# pcie-host.net
KiCad netlist of a schematic drawn in EAGLE
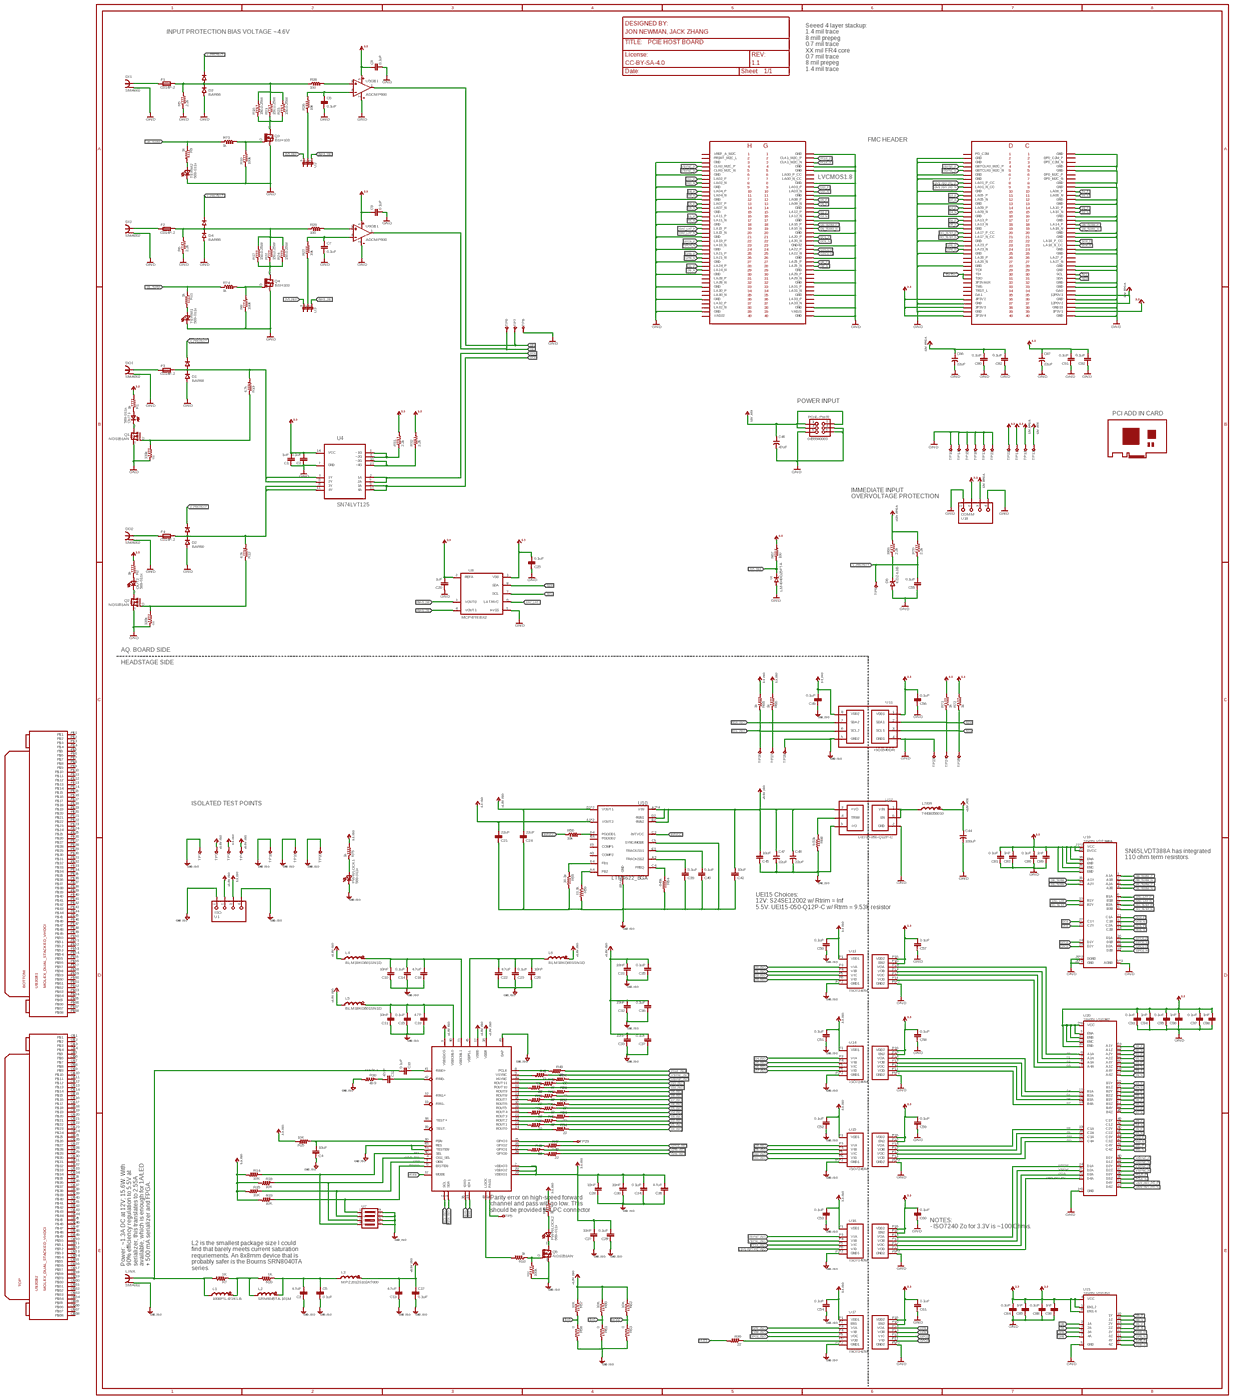
[diagram p0: schematic, sheet 1, overview]
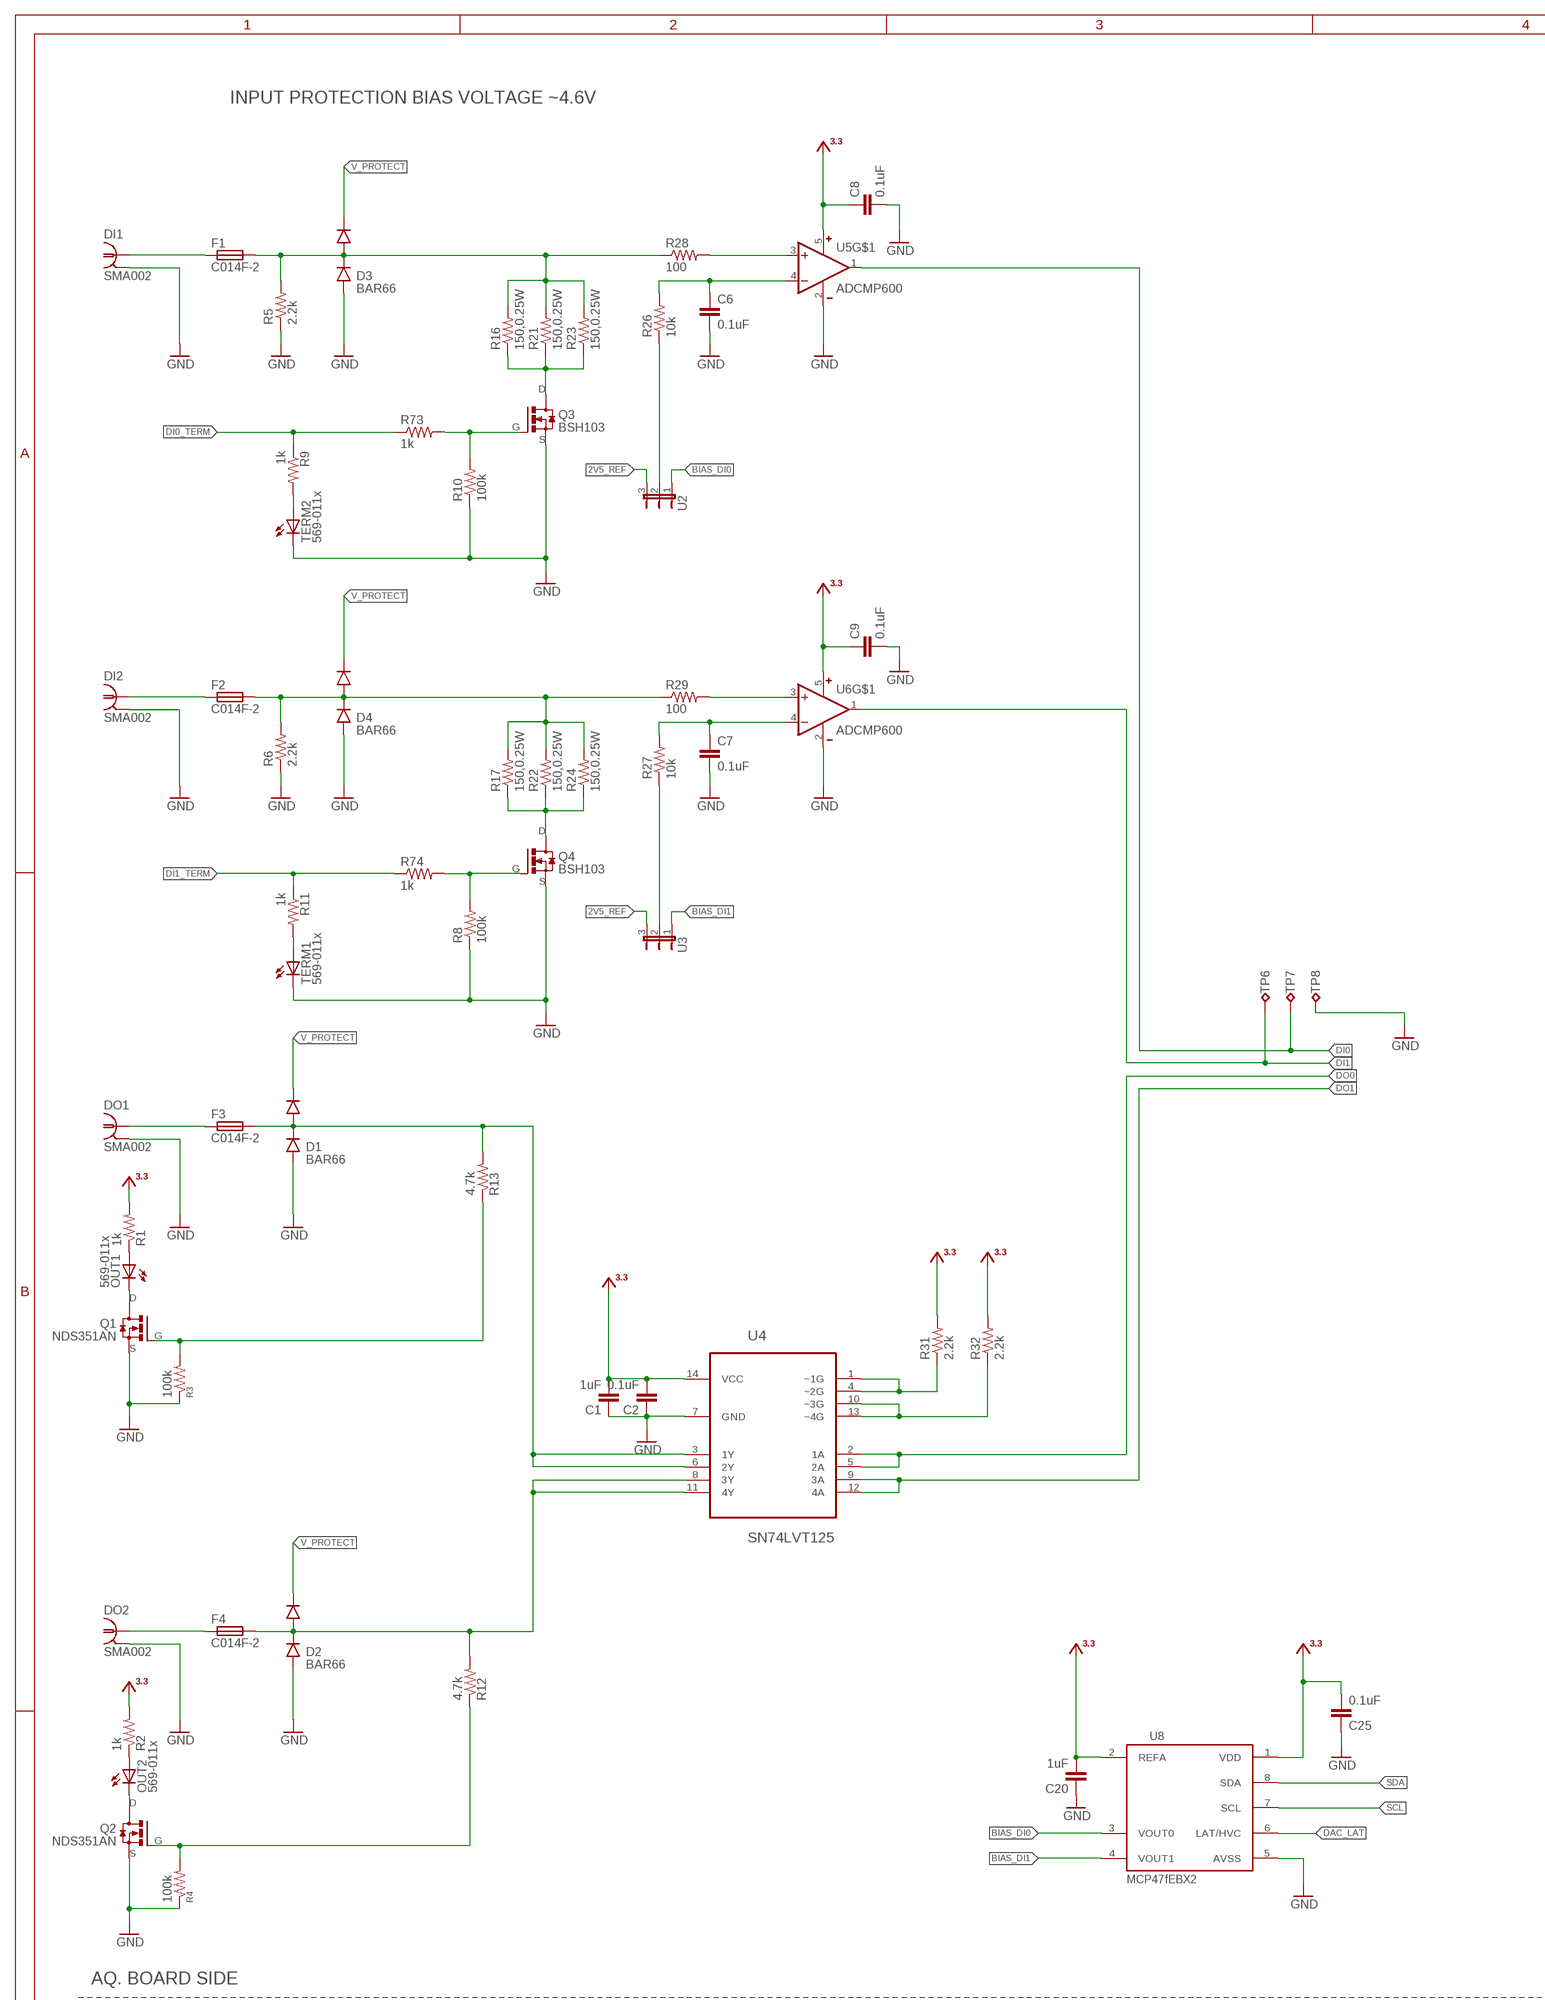
[diagram p1: schematic, sheet 1, part 1 of 4]
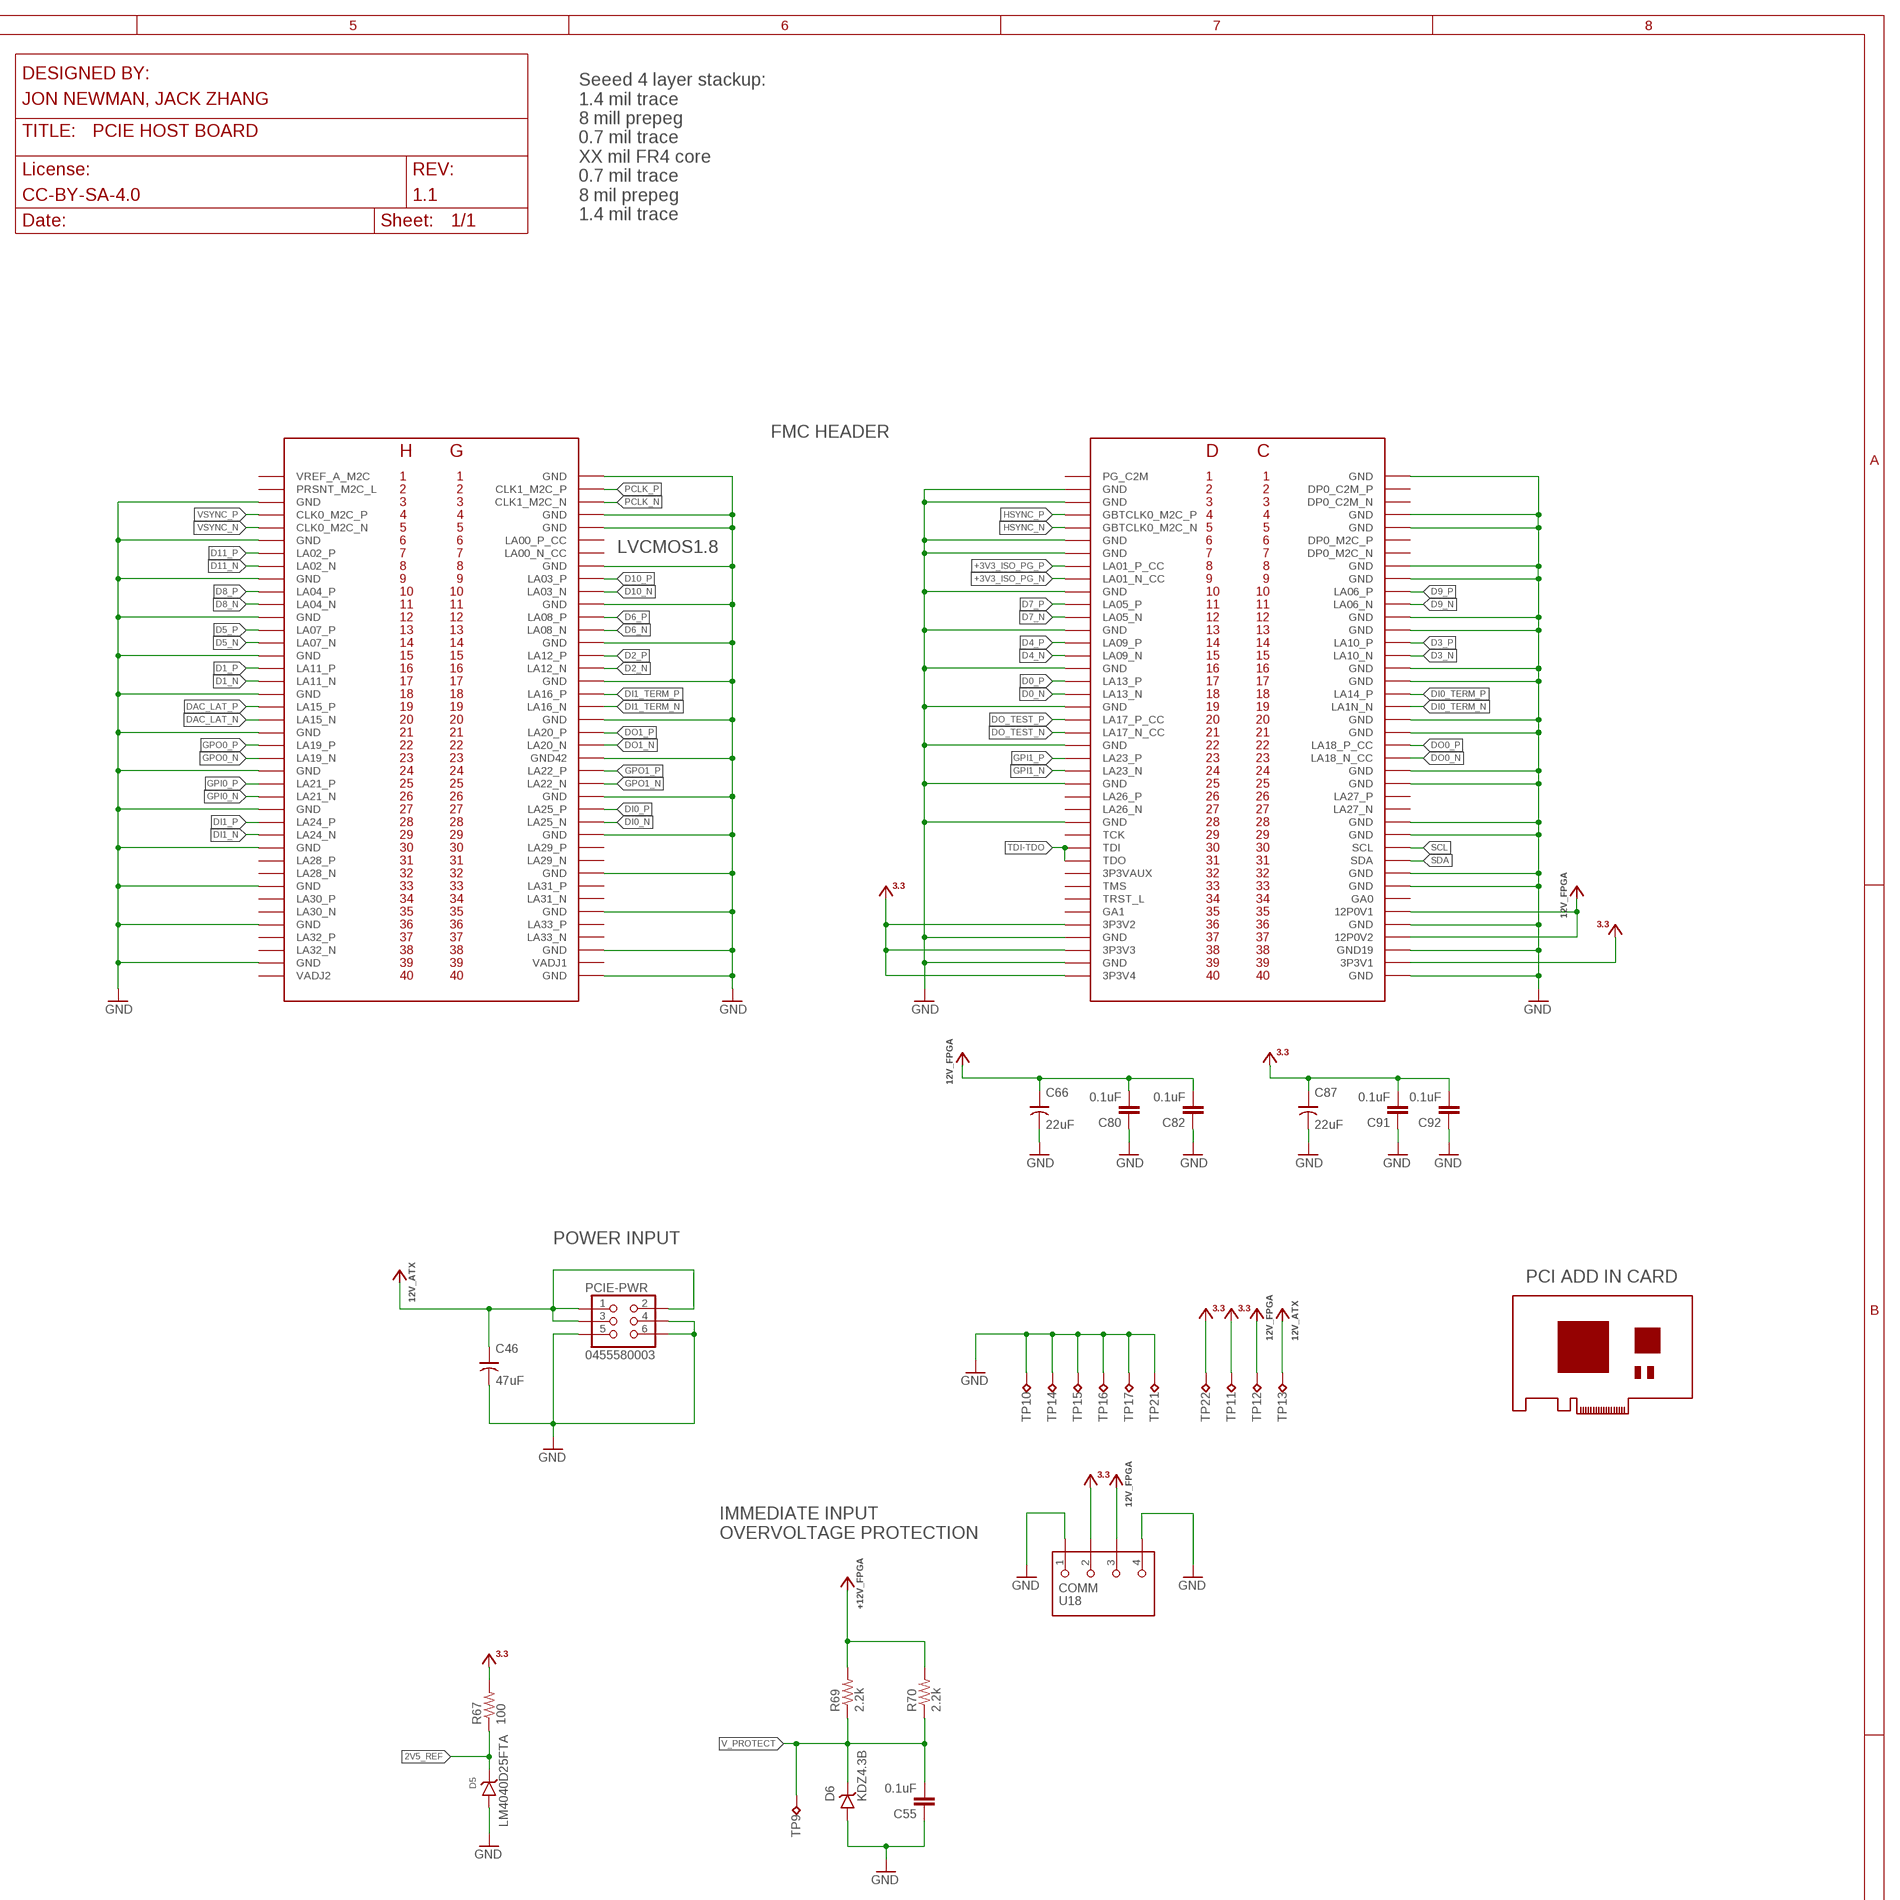
[diagram p2: schematic, sheet 1, part 2 of 4]
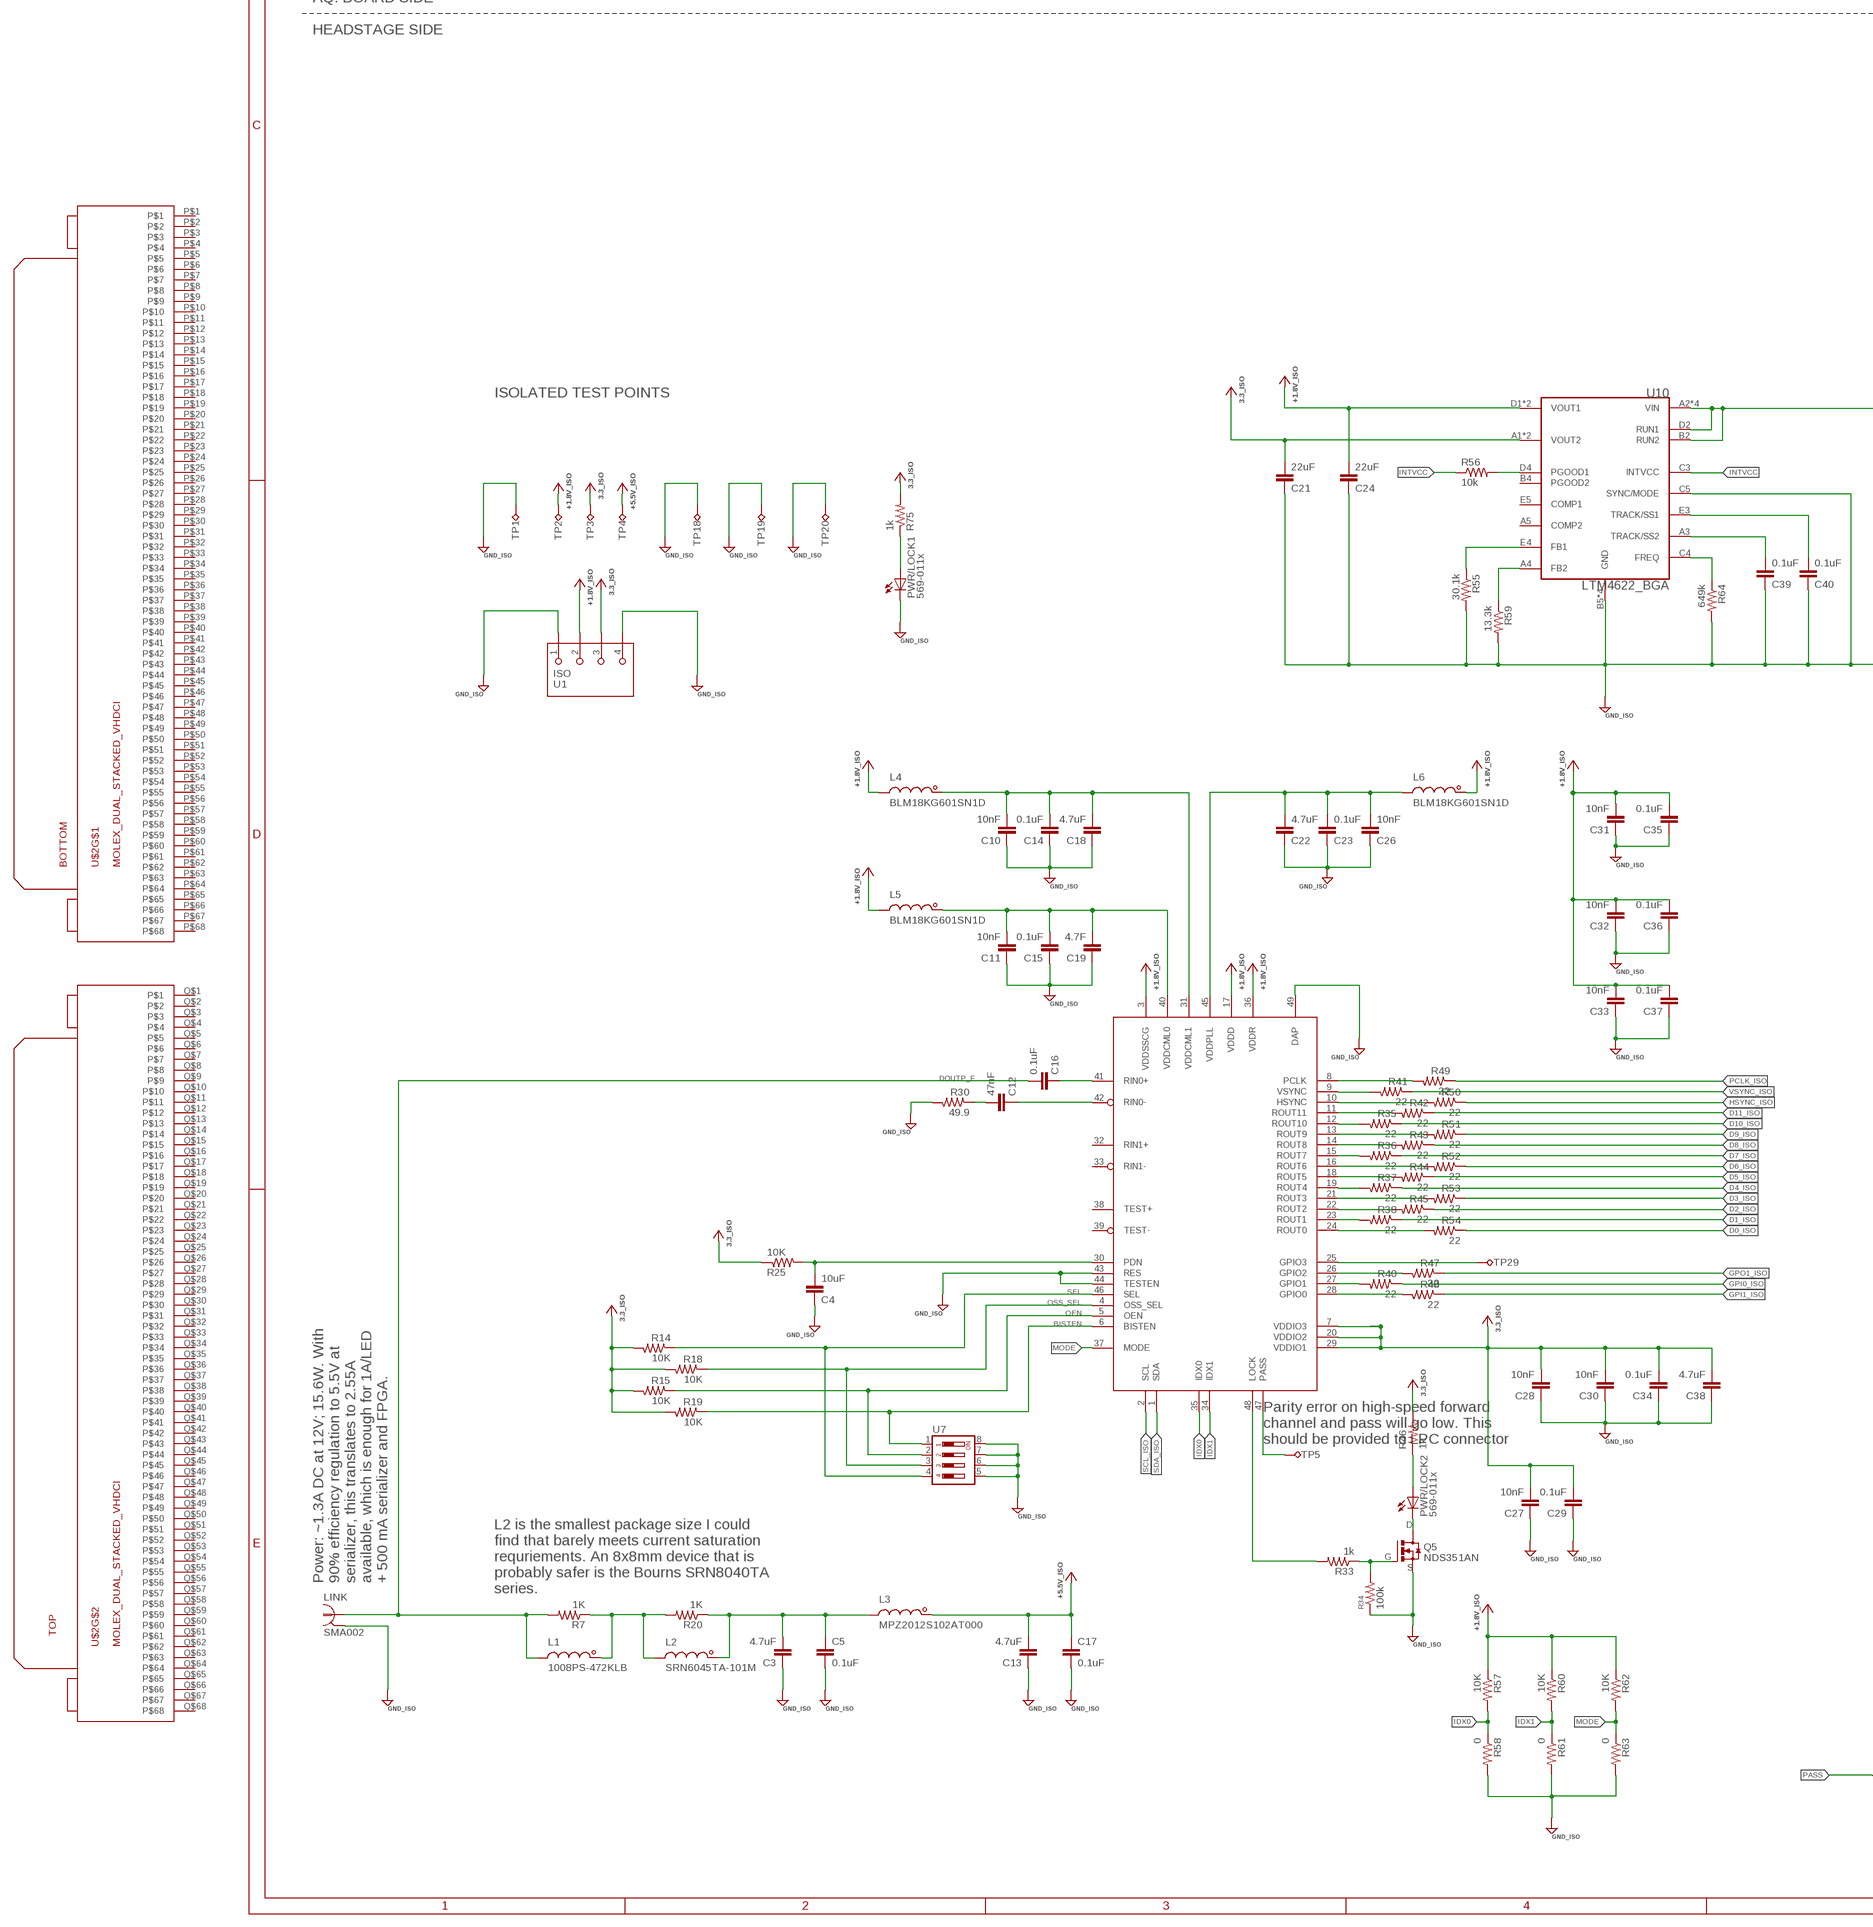
[diagram p3: schematic, sheet 1, part 3 of 4]
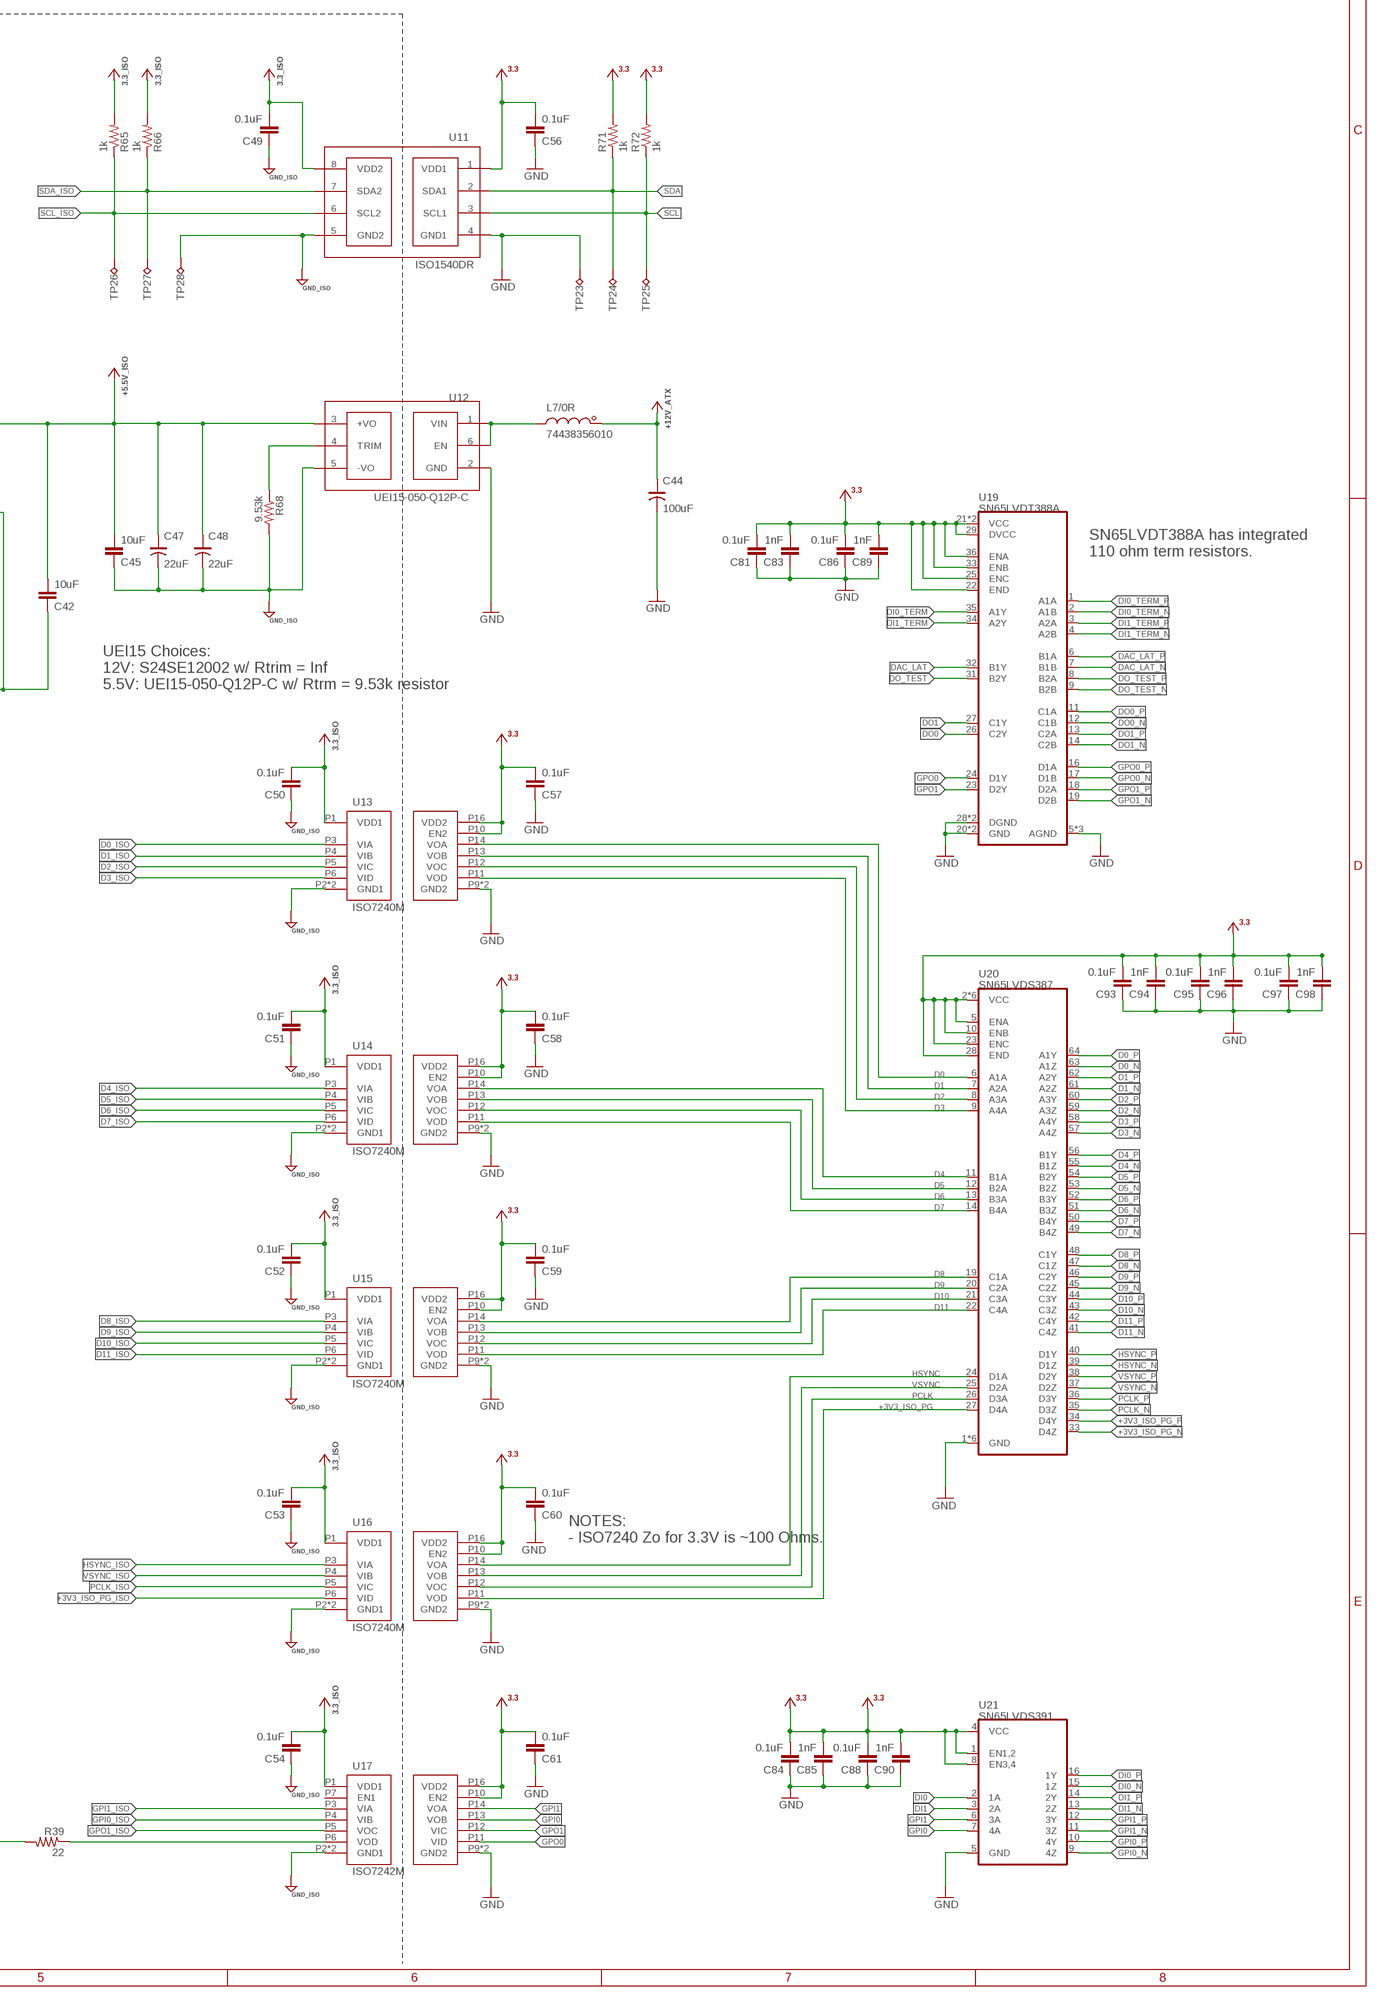
[diagram p4: schematic, sheet 1, part 4 of 4]

(export (version "E")
  (design (tool "Eeschema 10.0.6"))
  (components
    (comp (ref "C1")
      (value "1uF")
      (footprint "eagle-import:0603")
      (libsource (lib "eagle-import") (part "C_0603"))
    )
    (comp (ref "C2")
      (value "0.1uF")
      (footprint "eagle-import:0603")
      (libsource (lib "eagle-import") (part "C_0603"))
    )
    (comp (ref "C3")
      (value "4.7uF")
      (footprint "eagle-import:0805")
      (fields (field (name "PARTNO") "C2012X5R1Cxxxxxxx"))
      (libsource (lib "eagle-import") (part "jonnew_C_0805"))
    )
    (comp (ref "C4")
      (value "10uF")
      (footprint "eagle-import:0603")
      (libsource (lib "eagle-import") (part "jonnew_C_0603"))
    )
    (comp (ref "C5")
      (value "0.1uF")
      (footprint "eagle-import:0603")
      (libsource (lib "eagle-import") (part "jonnew_C_0603"))
    )
    (comp (ref "C6")
      (value "0.1uF")
      (footprint "eagle-import:0603")
      (libsource (lib "eagle-import") (part "jonnew_C_0603"))
    )
    (comp (ref "C7")
      (value "0.1uF")
      (footprint "eagle-import:0603")
      (libsource (lib "eagle-import") (part "jonnew_C_0603"))
    )
    (comp (ref "C8")
      (value "0.1uF")
      (footprint "eagle-import:0603")
      (libsource (lib "eagle-import") (part "jonnew_C_0603"))
    )
    (comp (ref "C9")
      (value "0.1uF")
      (footprint "eagle-import:0603")
      (libsource (lib "eagle-import") (part "jonnew_C_0603"))
    )
    (comp (ref "C10")
      (value "10nF")
      (footprint "eagle-import:0402")
      (libsource (lib "eagle-import") (part "jonnew_C_0402"))
    )
    (comp (ref "C11")
      (value "10nF")
      (footprint "eagle-import:0402")
      (libsource (lib "eagle-import") (part "jonnew_C_0402"))
    )
    (comp (ref "C12")
      (value "47nF")
      (footprint "eagle-import:0402")
      (libsource (lib "eagle-import") (part "jonnew_C_0402"))
    )
    (comp (ref "C13")
      (value "4.7uF")
      (footprint "eagle-import:0805")
      (fields (field (name "PARTNO") "C2012X5R1Cxxxxxxx"))
      (libsource (lib "eagle-import") (part "jonnew_C_0805"))
    )
    (comp (ref "C14")
      (value "0.1uF")
      (footprint "eagle-import:0402")
      (libsource (lib "eagle-import") (part "jonnew_C_0402"))
    )
    (comp (ref "C15")
      (value "0.1uF")
      (footprint "eagle-import:0402")
      (libsource (lib "eagle-import") (part "jonnew_C_0402"))
    )
    (comp (ref "C16")
      (value "0.1uF")
      (footprint "eagle-import:0402")
      (libsource (lib "eagle-import") (part "jonnew_C_0402"))
    )
    (comp (ref "C17")
      (value "0.1uF")
      (footprint "eagle-import:0603")
      (libsource (lib "eagle-import") (part "jonnew_C_0603"))
    )
    (comp (ref "C18")
      (value "4.7uF")
      (footprint "eagle-import:1206")
      (libsource (lib "eagle-import") (part "jonnew_C_1206"))
    )
    (comp (ref "C19")
      (value "4.7F")
      (footprint "eagle-import:1206")
      (libsource (lib "eagle-import") (part "jonnew_C_1206"))
    )
    (comp (ref "C20")
      (value "1uF")
      (footprint "eagle-import:0805")
      (fields (field (name "PARTNO") "C2012X5R1Cxxxxxxx"))
      (libsource (lib "eagle-import") (part "jonnew_C_0805"))
    )
    (comp (ref "C21")
      (value "22uF")
      (footprint "eagle-import:1206")
      (libsource (lib "eagle-import") (part "jonnew_C_1206"))
    )
    (comp (ref "C22")
      (value "4.7uF")
      (footprint "eagle-import:1206")
      (libsource (lib "eagle-import") (part "jonnew_C_1206"))
    )
    (comp (ref "C23")
      (value "0.1uF")
      (footprint "eagle-import:0402")
      (libsource (lib "eagle-import") (part "jonnew_C_0402"))
    )
    (comp (ref "C24")
      (value "22uF")
      (footprint "eagle-import:1206")
      (libsource (lib "eagle-import") (part "jonnew_C_1206"))
    )
    (comp (ref "C25")
      (value "0.1uF")
      (footprint "eagle-import:0603")
      (libsource (lib "eagle-import") (part "C_0603"))
    )
    (comp (ref "C26")
      (value "10nF")
      (footprint "eagle-import:0402")
      (libsource (lib "eagle-import") (part "jonnew_C_0402"))
    )
    (comp (ref "C27")
      (value "10nF")
      (footprint "eagle-import:0402")
      (libsource (lib "eagle-import") (part "jonnew_C_0402"))
    )
    (comp (ref "C28")
      (value "10nF")
      (footprint "eagle-import:0402")
      (libsource (lib "eagle-import") (part "jonnew_C_0402"))
    )
    (comp (ref "C29")
      (value "0.1uF")
      (footprint "eagle-import:0402")
      (libsource (lib "eagle-import") (part "jonnew_C_0402"))
    )
    (comp (ref "C30")
      (value "10nF")
      (footprint "eagle-import:0402")
      (libsource (lib "eagle-import") (part "jonnew_C_0402"))
    )
    (comp (ref "C31")
      (value "10nF")
      (footprint "eagle-import:0402")
      (libsource (lib "eagle-import") (part "jonnew_C_0402"))
    )
    (comp (ref "C32")
      (value "10nF")
      (footprint "eagle-import:0402")
      (libsource (lib "eagle-import") (part "jonnew_C_0402"))
    )
    (comp (ref "C33")
      (value "10nF")
      (footprint "eagle-import:0402")
      (libsource (lib "eagle-import") (part "jonnew_C_0402"))
    )
    (comp (ref "C34")
      (value "0.1uF")
      (footprint "eagle-import:0402")
      (libsource (lib "eagle-import") (part "jonnew_C_0402"))
    )
    (comp (ref "C35")
      (value "0.1uF")
      (footprint "eagle-import:0402")
      (libsource (lib "eagle-import") (part "jonnew_C_0402"))
    )
    (comp (ref "C36")
      (value "0.1uF")
      (footprint "eagle-import:0402")
      (libsource (lib "eagle-import") (part "jonnew_C_0402"))
    )
    (comp (ref "C37")
      (value "0.1uF")
      (footprint "eagle-import:0402")
      (libsource (lib "eagle-import") (part "jonnew_C_0402"))
    )
    (comp (ref "C38")
      (value "4.7uF")
      (footprint "eagle-import:1206")
      (libsource (lib "eagle-import") (part "jonnew_C_1206"))
    )
    (comp (ref "C39")
      (value "0.1uF")
      (footprint "eagle-import:0603")
      (libsource (lib "eagle-import") (part "jonnew_C_0603"))
    )
    (comp (ref "C40")
      (value "0.1uF")
      (footprint "eagle-import:0603")
      (libsource (lib "eagle-import") (part "jonnew_C_0603"))
    )
    (comp (ref "C42")
      (value "10uF")
      (footprint "eagle-import:1206")
      (libsource (lib "eagle-import") (part "jonnew_C_1206"))
    )
    (comp (ref "C44")
      (value "100uF")
      (footprint "eagle-import:153CLV-0807")
      (libsource (lib "eagle-import") (part "C-POL_0807"))
    )
    (comp (ref "C45")
      (value "10uF")
      (footprint "eagle-import:1206")
      (libsource (lib "eagle-import") (part "jonnew_C_1206"))
    )
    (comp (ref "C46")
      (value "47uF")
      (footprint "eagle-import:153CLV-0807")
      (libsource (lib "eagle-import") (part "C-POL_0807"))
    )
    (comp (ref "C47")
      (value "22uF")
      (footprint "eagle-import:1210-POL")
      (libsource (lib "eagle-import") (part "C-POL_1210"))
    )
    (comp (ref "C48")
      (value "22uF")
      (footprint "eagle-import:1210-POL")
      (libsource (lib "eagle-import") (part "C-POL_1210"))
    )
    (comp (ref "C49")
      (value "0.1uF")
      (footprint "eagle-import:0603")
      (libsource (lib "eagle-import") (part "jonnew_C_0603"))
    )
    (comp (ref "C50")
      (value "0.1uF")
      (footprint "eagle-import:0603")
      (libsource (lib "eagle-import") (part "jonnew_C_0603"))
    )
    (comp (ref "C51")
      (value "0.1uF")
      (footprint "eagle-import:0603")
      (libsource (lib "eagle-import") (part "jonnew_C_0603"))
    )
    (comp (ref "C52")
      (value "0.1uF")
      (footprint "eagle-import:0603")
      (libsource (lib "eagle-import") (part "jonnew_C_0603"))
    )
    (comp (ref "C53")
      (value "0.1uF")
      (footprint "eagle-import:0603")
      (libsource (lib "eagle-import") (part "jonnew_C_0603"))
    )
    (comp (ref "C54")
      (value "0.1uF")
      (footprint "eagle-import:0603")
      (libsource (lib "eagle-import") (part "jonnew_C_0603"))
    )
    (comp (ref "C55")
      (value "0.1uF")
      (footprint "eagle-import:0603")
      (libsource (lib "eagle-import") (part "jonnew_C_0603"))
    )
    (comp (ref "C56")
      (value "0.1uF")
      (footprint "eagle-import:0603")
      (libsource (lib "eagle-import") (part "jonnew_C_0603"))
    )
    (comp (ref "C57")
      (value "0.1uF")
      (footprint "eagle-import:0603")
      (libsource (lib "eagle-import") (part "jonnew_C_0603"))
    )
    (comp (ref "C58")
      (value "0.1uF")
      (footprint "eagle-import:0603")
      (libsource (lib "eagle-import") (part "jonnew_C_0603"))
    )
    (comp (ref "C59")
      (value "0.1uF")
      (footprint "eagle-import:0603")
      (libsource (lib "eagle-import") (part "jonnew_C_0603"))
    )
    (comp (ref "C60")
      (value "0.1uF")
      (footprint "eagle-import:0603")
      (libsource (lib "eagle-import") (part "jonnew_C_0603"))
    )
    (comp (ref "C61")
      (value "0.1uF")
      (footprint "eagle-import:0603")
      (libsource (lib "eagle-import") (part "jonnew_C_0603"))
    )
    (comp (ref "C66")
      (value "22uF")
      (footprint "eagle-import:1210-POL")
      (libsource (lib "eagle-import") (part "C-POL_1210"))
    )
    (comp (ref "C80")
      (value "0.1uF")
      (footprint "eagle-import:0603")
      (libsource (lib "eagle-import") (part "jonnew_C_0603"))
    )
    (comp (ref "C81")
      (value "0.1uF")
      (footprint "eagle-import:0603")
      (libsource (lib "eagle-import") (part "jonnew_C_0603"))
    )
    (comp (ref "C82")
      (value "0.1uF")
      (footprint "eagle-import:0603")
      (libsource (lib "eagle-import") (part "jonnew_C_0603"))
    )
    (comp (ref "C83")
      (value "1nF")
      (footprint "eagle-import:0402")
      (libsource (lib "eagle-import") (part "jonnew_C_0402"))
    )
    (comp (ref "C84")
      (value "0.1uF")
      (footprint "eagle-import:0603")
      (libsource (lib "eagle-import") (part "jonnew_C_0603"))
    )
    (comp (ref "C85")
      (value "1nF")
      (footprint "eagle-import:0402")
      (libsource (lib "eagle-import") (part "jonnew_C_0402"))
    )
    (comp (ref "C86")
      (value "0.1uF")
      (footprint "eagle-import:0603")
      (libsource (lib "eagle-import") (part "jonnew_C_0603"))
    )
    (comp (ref "C87")
      (value "22uF")
      (footprint "eagle-import:1210-POL")
      (libsource (lib "eagle-import") (part "C-POL_1210"))
    )
    (comp (ref "C88")
      (value "0.1uF")
      (footprint "eagle-import:0603")
      (libsource (lib "eagle-import") (part "jonnew_C_0603"))
    )
    (comp (ref "C89")
      (value "1nF")
      (footprint "eagle-import:0402")
      (libsource (lib "eagle-import") (part "jonnew_C_0402"))
    )
    (comp (ref "C90")
      (value "1nF")
      (footprint "eagle-import:0402")
      (libsource (lib "eagle-import") (part "jonnew_C_0402"))
    )
    (comp (ref "C91")
      (value "0.1uF")
      (footprint "eagle-import:0603")
      (libsource (lib "eagle-import") (part "jonnew_C_0603"))
    )
    (comp (ref "C92")
      (value "0.1uF")
      (footprint "eagle-import:0603")
      (libsource (lib "eagle-import") (part "jonnew_C_0603"))
    )
    (comp (ref "C93")
      (value "0.1uF")
      (footprint "eagle-import:0603")
      (libsource (lib "eagle-import") (part "jonnew_C_0603"))
    )
    (comp (ref "C94")
      (value "1nF")
      (footprint "eagle-import:0402")
      (libsource (lib "eagle-import") (part "jonnew_C_0402"))
    )
    (comp (ref "C95")
      (value "0.1uF")
      (footprint "eagle-import:0603")
      (libsource (lib "eagle-import") (part "jonnew_C_0603"))
    )
    (comp (ref "C96")
      (value "1nF")
      (footprint "eagle-import:0402")
      (libsource (lib "eagle-import") (part "jonnew_C_0402"))
    )
    (comp (ref "C97")
      (value "0.1uF")
      (footprint "eagle-import:0603")
      (libsource (lib "eagle-import") (part "jonnew_C_0603"))
    )
    (comp (ref "C98")
      (value "1nF")
      (footprint "eagle-import:0402")
      (libsource (lib "eagle-import") (part "jonnew_C_0402"))
    )
    (comp (ref "D1")
      (value "BAR66")
      (footprint "eagle-import:SOT23")
      (libsource (lib "eagle-import") (part "DIODE2_SOT23"))
    )
    (comp (ref "D2")
      (value "BAR66")
      (footprint "eagle-import:SOT23")
      (libsource (lib "eagle-import") (part "DIODE2_SOT23"))
    )
    (comp (ref "D3")
      (value "BAR66")
      (footprint "eagle-import:SOT23")
      (libsource (lib "eagle-import") (part "DIODE2_SOT23"))
    )
    (comp (ref "D4")
      (value "BAR66")
      (footprint "eagle-import:SOT23")
      (libsource (lib "eagle-import") (part "DIODE2_SOT23"))
    )
    (comp (ref "D5")
      (value "LM4040D25FTA")
      (footprint "eagle-import:SOT23")
      (libsource (lib "eagle-import") (part "Z-DIODE_SOT23"))
    )
    (comp (ref "D6")
      (value "KDZ4.3B")
      (footprint "eagle-import:SOD123")
      (libsource (lib "eagle-import") (part "Z-DIODE_SOD123"))
    )
    (comp (ref "DI1")
      (value "SMA002")
      (footprint "eagle-import:SMA_JACK_CONREVSMA002-G")
      (libsource (lib "eagle-import") (part "COAX_CONREVSMA002-G"))
    )
    (comp (ref "DI2")
      (value "SMA002")
      (footprint "eagle-import:SMA_JACK_CONREVSMA002-G")
      (libsource (lib "eagle-import") (part "COAX_CONREVSMA002-G"))
    )
    (comp (ref "DO1")
      (value "SMA002")
      (footprint "eagle-import:SMA_JACK_CONREVSMA002-G")
      (libsource (lib "eagle-import") (part "COAX_CONREVSMA002-G"))
    )
    (comp (ref "DO2")
      (value "SMA002")
      (footprint "eagle-import:SMA_JACK_CONREVSMA002-G")
      (libsource (lib "eagle-import") (part "COAX_CONREVSMA002-G"))
    )
    (comp (ref "F1")
      (value "C014F-2")
      (footprint "eagle-import:1812")
      (libsource (lib "eagle-import") (part "FUSE_1812"))
    )
    (comp (ref "F2")
      (value "C014F-2")
      (footprint "eagle-import:1812")
      (libsource (lib "eagle-import") (part "FUSE_1812"))
    )
    (comp (ref "F3")
      (value "C014F-2")
      (footprint "eagle-import:1812")
      (libsource (lib "eagle-import") (part "FUSE_1812"))
    )
    (comp (ref "F4")
      (value "C014F-2")
      (footprint "eagle-import:1812")
      (libsource (lib "eagle-import") (part "FUSE_1812"))
    )
    (comp (ref "FMC_LPC")
      (value "FMC_LPC_160_PIN")
      (footprint "eagle-import:FMC_LPC_MALE_WITH_SP601_BSILK")
      (libsource (lib "eagle-import") (part "FMC_LPC_160_PIN"))
    )
    (comp (ref "L1")
      (value "1008PS-472KLB")
      (footprint "eagle-import:1008PS")
      (libsource (lib "eagle-import") (part "L_1008PS"))
    )
    (comp (ref "L2")
      (value "SRN6045TA-101M")
      (footprint "eagle-import:SRN6045TA")
      (libsource (lib "eagle-import") (part "L_SRN6045TA"))
    )
    (comp (ref "L3")
      (value "MPZ2012S102AT000")
      (footprint "eagle-import:0805")
      (libsource (lib "eagle-import") (part "L_0805"))
    )
    (comp (ref "L4")
      (value "BLM18KG601SN1D")
      (footprint "eagle-import:0603")
      (libsource (lib "eagle-import") (part "L_0603"))
    )
    (comp (ref "L5")
      (value "BLM18KG601SN1D")
      (footprint "eagle-import:0603")
      (libsource (lib "eagle-import") (part "L_0603"))
    )
    (comp (ref "L6")
      (value "BLM18KG601SN1D")
      (footprint "eagle-import:0603")
      (libsource (lib "eagle-import") (part "L_0603"))
    )
    (comp (ref "L7/0R")
      (value "74438356010")
      (footprint "eagle-import:4020")
      (libsource (lib "eagle-import") (part "L_4020"))
    )
    (comp (ref "LINK")
      (value "SMA002")
      (footprint "eagle-import:SMA_JACK_CONREVSMA002-G")
      (libsource (lib "eagle-import") (part "COAX_CONREVSMA002-G"))
    )
    (comp (ref "OUT")
      (value "569-011x")
      (footprint "eagle-import:569-011X-X00_LED_ARRAY")
      (libsource (lib "eagle-import") (part "LED_2X_VERTICAL"))
    )
    (comp (ref "PCIE-PWR")
      (value "0455580003")
      (footprint "eagle-import:PCIE-POWER-6PIN")
      (libsource (lib "eagle-import") (part "PINHD-2X3_PCIE-PWR"))
    )
    (comp (ref "PWR/LOCK")
      (value "569-011x")
      (footprint "eagle-import:569-011X-X00_LED_ARRAY")
      (libsource (lib "eagle-import") (part "LED_2X_VERTICAL"))
    )
    (comp (ref "Q1")
      (value "NDS351AN")
      (footprint "eagle-import:SOT23-GSD")
      (libsource (lib "eagle-import") (part "N-MOSFET_SOT23-GSD"))
    )
    (comp (ref "Q2")
      (value "NDS351AN")
      (footprint "eagle-import:SOT23-GSD")
      (libsource (lib "eagle-import") (part "N-MOSFET_SOT23-GSD"))
    )
    (comp (ref "Q3")
      (value "BSH103")
      (footprint "eagle-import:SOT23-GSD")
      (libsource (lib "eagle-import") (part "N-MOSFET_SOT23-GSD"))
    )
    (comp (ref "Q4")
      (value "BSH103")
      (footprint "eagle-import:SOT23-GSD")
      (libsource (lib "eagle-import") (part "N-MOSFET_SOT23-GSD"))
    )
    (comp (ref "Q5")
      (value "NDS351AN")
      (footprint "eagle-import:SOT23-GSD")
      (libsource (lib "eagle-import") (part "N-MOSFET_SOT23-GSD"))
    )
    (comp (ref "R1")
      (value "1k")
      (footprint "eagle-import:0603")
      (fields (field (name "MPN") "ERJ-3EKFxxxxV"))
      (libsource (lib "eagle-import") (part "cyclops_R_0603"))
    )
    (comp (ref "R2")
      (value "1k")
      (footprint "eagle-import:0603")
      (fields (field (name "MPN") "ERJ-3EKFxxxxV"))
      (libsource (lib "eagle-import") (part "cyclops_R_0603"))
    )
    (comp (ref "R3")
      (value "100k")
      (footprint "eagle-import:0603")
      (fields (field (name "MPN") "ERJ-3EKFxxxxV"))
      (libsource (lib "eagle-import") (part "cyclops_R_0603"))
    )
    (comp (ref "R4")
      (value "100k")
      (footprint "eagle-import:0603")
      (fields (field (name "MPN") "ERJ-3EKFxxxxV"))
      (libsource (lib "eagle-import") (part "cyclops_R_0603"))
    )
    (comp (ref "R5")
      (value "2.2k")
      (footprint "eagle-import:0603")
      (fields (field (name "MPN") "ERJ-3EKFxxxxV"))
      (libsource (lib "eagle-import") (part "jonnew_R_0603"))
    )
    (comp (ref "R6")
      (value "2.2k")
      (footprint "eagle-import:0603")
      (fields (field (name "MPN") "ERJ-3EKFxxxxV"))
      (libsource (lib "eagle-import") (part "jonnew_R_0603"))
    )
    (comp (ref "R7")
      (value "1K")
      (footprint "eagle-import:0603")
      (fields (field (name "MPN") "ERJ-3EKFxxxxV"))
      (libsource (lib "eagle-import") (part "jonnew_R_0603"))
    )
    (comp (ref "R8")
      (value "100k")
      (footprint "eagle-import:0603")
      (fields (field (name "MPN") "ERJ-3EKFxxxxV"))
      (libsource (lib "eagle-import") (part "jonnew_R_0603"))
    )
    (comp (ref "R9")
      (value "1k")
      (footprint "eagle-import:0603")
      (fields (field (name "MPN") "ERJ-3EKFxxxxV"))
      (libsource (lib "eagle-import") (part "jonnew_R_0603"))
    )
    (comp (ref "R10")
      (value "100k")
      (footprint "eagle-import:0603")
      (fields (field (name "MPN") "ERJ-3EKFxxxxV"))
      (libsource (lib "eagle-import") (part "jonnew_R_0603"))
    )
    (comp (ref "R11")
      (value "1k")
      (footprint "eagle-import:0603")
      (libsource (lib "eagle-import") (part "R_0603"))
    )
    (comp (ref "R12")
      (value "4.7k")
      (footprint "eagle-import:0603")
      (fields (field (name "MPN") "ERJ-3EKFxxxxV"))
      (libsource (lib "eagle-import") (part "cyclops_R_0603"))
    )
    (comp (ref "R13")
      (value "4.7k")
      (footprint "eagle-import:0603")
      (fields (field (name "MPN") "ERJ-3EKFxxxxV"))
      (libsource (lib "eagle-import") (part "cyclops_R_0603"))
    )
    (comp (ref "R14")
      (value "10K")
      (footprint "eagle-import:0402")
      (libsource (lib "eagle-import") (part "jonnew_R_0402"))
    )
    (comp (ref "R15")
      (value "10K")
      (footprint "eagle-import:0402")
      (libsource (lib "eagle-import") (part "jonnew_R_0402"))
    )
    (comp (ref "R16")
      (value "150,0.25W")
      (footprint "eagle-import:1206")
      (libsource (lib "eagle-import") (part "jonnew_R_1206"))
    )
    (comp (ref "R17")
      (value "150,0.25W")
      (footprint "eagle-import:1206")
      (libsource (lib "eagle-import") (part "jonnew_R_1206"))
    )
    (comp (ref "R18")
      (value "10K")
      (footprint "eagle-import:0402")
      (libsource (lib "eagle-import") (part "jonnew_R_0402"))
    )
    (comp (ref "R19")
      (value "10K")
      (footprint "eagle-import:0402")
      (libsource (lib "eagle-import") (part "jonnew_R_0402"))
    )
    (comp (ref "R20")
      (value "1K")
      (footprint "eagle-import:0603")
      (fields (field (name "MPN") "ERJ-3EKFxxxxV"))
      (libsource (lib "eagle-import") (part "jonnew_R_0603"))
    )
    (comp (ref "R21")
      (value "150,0.25W")
      (footprint "eagle-import:1206")
      (libsource (lib "eagle-import") (part "jonnew_R_1206"))
    )
    (comp (ref "R22")
      (value "150,0.25W")
      (footprint "eagle-import:1206")
      (libsource (lib "eagle-import") (part "jonnew_R_1206"))
    )
    (comp (ref "R23")
      (value "150,0.25W")
      (footprint "eagle-import:1206")
      (libsource (lib "eagle-import") (part "jonnew_R_1206"))
    )
    (comp (ref "R24")
      (value "150,0.25W")
      (footprint "eagle-import:1206")
      (libsource (lib "eagle-import") (part "jonnew_R_1206"))
    )
    (comp (ref "R25")
      (value "10K")
      (footprint "eagle-import:0402")
      (libsource (lib "eagle-import") (part "jonnew_R_0402"))
    )
    (comp (ref "R26")
      (value "10k")
      (footprint "eagle-import:0603")
      (fields (field (name "MPN") "ERJ-3EKFxxxxV"))
      (libsource (lib "eagle-import") (part "jonnew_R_0603"))
    )
    (comp (ref "R27")
      (value "10k")
      (footprint "eagle-import:0603")
      (fields (field (name "MPN") "ERJ-3EKFxxxxV"))
      (libsource (lib "eagle-import") (part "jonnew_R_0603"))
    )
    (comp (ref "R28")
      (value "100")
      (footprint "eagle-import:0603")
      (fields (field (name "MPN") "ERJ-3EKFxxxxV"))
      (libsource (lib "eagle-import") (part "jonnew_R_0603"))
    )
    (comp (ref "R29")
      (value "100")
      (footprint "eagle-import:0603")
      (fields (field (name "MPN") "ERJ-3EKFxxxxV"))
      (libsource (lib "eagle-import") (part "jonnew_R_0603"))
    )
    (comp (ref "R30")
      (value "49.9")
      (footprint "eagle-import:0402")
      (libsource (lib "eagle-import") (part "jonnew_R_0402"))
    )
    (comp (ref "R31")
      (value "2.2k")
      (footprint "eagle-import:0603")
      (fields (field (name "MPN") "ERJ-3EKFxxxxV"))
      (libsource (lib "eagle-import") (part "jonnew_R_0603"))
    )
    (comp (ref "R32")
      (value "2.2k")
      (footprint "eagle-import:0603")
      (fields (field (name "MPN") "ERJ-3EKFxxxxV"))
      (libsource (lib "eagle-import") (part "jonnew_R_0603"))
    )
    (comp (ref "R33")
      (value "1k")
      (footprint "eagle-import:0603")
      (fields (field (name "MPN") "ERJ-3EKFxxxxV"))
      (libsource (lib "eagle-import") (part "cyclops_R_0603"))
    )
    (comp (ref "R34")
      (value "100k")
      (footprint "eagle-import:0603")
      (fields (field (name "MPN") "ERJ-3EKFxxxxV"))
      (libsource (lib "eagle-import") (part "cyclops_R_0603"))
    )
    (comp (ref "R35")
      (value "22")
      (footprint "eagle-import:0402")
      (libsource (lib "eagle-import") (part "jonnew_R_0402"))
    )
    (comp (ref "R36")
      (value "22")
      (footprint "eagle-import:0402")
      (libsource (lib "eagle-import") (part "jonnew_R_0402"))
    )
    (comp (ref "R37")
      (value "22")
      (footprint "eagle-import:0402")
      (libsource (lib "eagle-import") (part "jonnew_R_0402"))
    )
    (comp (ref "R38")
      (value "22")
      (footprint "eagle-import:0402")
      (libsource (lib "eagle-import") (part "jonnew_R_0402"))
    )
    (comp (ref "R39")
      (value "22")
      (footprint "eagle-import:0402")
      (libsource (lib "eagle-import") (part "jonnew_R_0402"))
    )
    (comp (ref "R40")
      (value "22")
      (footprint "eagle-import:0402")
      (libsource (lib "eagle-import") (part "jonnew_R_0402"))
    )
    (comp (ref "R41")
      (value "22")
      (footprint "eagle-import:0402")
      (libsource (lib "eagle-import") (part "jonnew_R_0402"))
    )
    (comp (ref "R42")
      (value "22")
      (footprint "eagle-import:0402")
      (libsource (lib "eagle-import") (part "jonnew_R_0402"))
    )
    (comp (ref "R43")
      (value "22")
      (footprint "eagle-import:0402")
      (libsource (lib "eagle-import") (part "jonnew_R_0402"))
    )
    (comp (ref "R44")
      (value "22")
      (footprint "eagle-import:0402")
      (libsource (lib "eagle-import") (part "jonnew_R_0402"))
    )
    (comp (ref "R45")
      (value "22")
      (footprint "eagle-import:0402")
      (libsource (lib "eagle-import") (part "jonnew_R_0402"))
    )
    (comp (ref "R46")
      (value "1k")
      (footprint "eagle-import:0603")
      (fields (field (name "MPN") "ERJ-3EKFxxxxV"))
      (libsource (lib "eagle-import") (part "cyclops_R_0603"))
    )
    (comp (ref "R47")
      (value "22")
      (footprint "eagle-import:0402")
      (libsource (lib "eagle-import") (part "jonnew_R_0402"))
    )
    (comp (ref "R48")
      (value "22")
      (footprint "eagle-import:0402")
      (libsource (lib "eagle-import") (part "jonnew_R_0402"))
    )
    (comp (ref "R49")
      (value "22")
      (footprint "eagle-import:0402")
      (libsource (lib "eagle-import") (part "jonnew_R_0402"))
    )
    (comp (ref "R50")
      (value "22")
      (footprint "eagle-import:0402")
      (libsource (lib "eagle-import") (part "jonnew_R_0402"))
    )
    (comp (ref "R51")
      (value "22")
      (footprint "eagle-import:0402")
      (libsource (lib "eagle-import") (part "jonnew_R_0402"))
    )
    (comp (ref "R52")
      (value "22")
      (footprint "eagle-import:0402")
      (libsource (lib "eagle-import") (part "jonnew_R_0402"))
    )
    (comp (ref "R53")
      (value "22")
      (footprint "eagle-import:0402")
      (libsource (lib "eagle-import") (part "jonnew_R_0402"))
    )
    (comp (ref "R54")
      (value "22")
      (footprint "eagle-import:0402")
      (libsource (lib "eagle-import") (part "jonnew_R_0402"))
    )
    (comp (ref "R55")
      (value "30.1k")
      (footprint "eagle-import:0603")
      (fields (field (name "MPN") "ERJ-3EKFxxxxV"))
      (libsource (lib "eagle-import") (part "jonnew_R_0603"))
    )
    (comp (ref "R56")
      (value "10k")
      (footprint "eagle-import:0603")
      (fields (field (name "MPN") "ERJ-3EKFxxxxV"))
      (libsource (lib "eagle-import") (part "jonnew_R_0603"))
    )
    (comp (ref "R57")
      (value "10K")
      (footprint "eagle-import:0402")
      (libsource (lib "eagle-import") (part "jonnew_R_0402"))
    )
    (comp (ref "R58")
      (value "0")
      (footprint "eagle-import:0402")
      (libsource (lib "eagle-import") (part "jonnew_R_0402"))
    )
    (comp (ref "R59")
      (value "13.3k")
      (footprint "eagle-import:0603")
      (fields (field (name "MPN") "ERJ-3EKFxxxxV"))
      (libsource (lib "eagle-import") (part "jonnew_R_0603"))
    )
    (comp (ref "R60")
      (value "10K")
      (footprint "eagle-import:0402")
      (libsource (lib "eagle-import") (part "jonnew_R_0402"))
    )
    (comp (ref "R61")
      (value "0")
      (footprint "eagle-import:0402")
      (libsource (lib "eagle-import") (part "jonnew_R_0402"))
    )
    (comp (ref "R62")
      (value "10K")
      (footprint "eagle-import:0402")
      (libsource (lib "eagle-import") (part "jonnew_R_0402"))
    )
    (comp (ref "R63")
      (value "0")
      (footprint "eagle-import:0402")
      (libsource (lib "eagle-import") (part "jonnew_R_0402"))
    )
    (comp (ref "R64")
      (value "649k")
      (footprint "eagle-import:0603")
      (fields (field (name "MPN") "ERJ-3EKFxxxxV"))
      (libsource (lib "eagle-import") (part "jonnew_R_0603"))
    )
    (comp (ref "R65")
      (value "1k")
      (footprint "eagle-import:0603")
      (fields (field (name "MPN") "ERJ-3EKFxxxxV"))
      (libsource (lib "eagle-import") (part "jonnew_R_0603"))
    )
    (comp (ref "R66")
      (value "1k")
      (footprint "eagle-import:0603")
      (fields (field (name "MPN") "ERJ-3EKFxxxxV"))
      (libsource (lib "eagle-import") (part "jonnew_R_0603"))
    )
    (comp (ref "R67")
      (value "100")
      (footprint "eagle-import:0603")
      (fields (field (name "MPN") "ERJ-3EKFxxxxV"))
      (libsource (lib "eagle-import") (part "jonnew_R_0603"))
    )
    (comp (ref "R68")
      (value "9.53k")
      (footprint "eagle-import:0603")
      (fields (field (name "MPN") "ERJ-3EKFxxxxV"))
      (libsource (lib "eagle-import") (part "jonnew_R_0603"))
    )
    (comp (ref "R69")
      (value "2.2k")
      (footprint "eagle-import:0603")
      (fields (field (name "MPN") "ERJ-3EKFxxxxV"))
      (libsource (lib "eagle-import") (part "jonnew_R_0603"))
    )
    (comp (ref "R70")
      (value "2.2k")
      (footprint "eagle-import:0603")
      (fields (field (name "MPN") "ERJ-3EKFxxxxV"))
      (libsource (lib "eagle-import") (part "jonnew_R_0603"))
    )
    (comp (ref "R71")
      (value "1k")
      (footprint "eagle-import:0603")
      (fields (field (name "MPN") "ERJ-3EKFxxxxV"))
      (libsource (lib "eagle-import") (part "jonnew_R_0603"))
    )
    (comp (ref "R72")
      (value "1k")
      (footprint "eagle-import:0603")
      (fields (field (name "MPN") "ERJ-3EKFxxxxV"))
      (libsource (lib "eagle-import") (part "jonnew_R_0603"))
    )
    (comp (ref "R73")
      (value "1k")
      (footprint "eagle-import:0603")
      (fields (field (name "MPN") "ERJ-3EKFxxxxV"))
      (libsource (lib "eagle-import") (part "jonnew_R_0603"))
    )
    (comp (ref "R74")
      (value "1k")
      (footprint "eagle-import:0603")
      (fields (field (name "MPN") "ERJ-3EKFxxxxV"))
      (libsource (lib "eagle-import") (part "jonnew_R_0603"))
    )
    (comp (ref "R75")
      (value "1k")
      (footprint "eagle-import:0603")
      (fields (field (name "MPN") "ERJ-3EKFxxxxV"))
      (libsource (lib "eagle-import") (part "cyclops_R_0603"))
    )
    (comp (ref "TERM")
      (value "569-011x")
      (footprint "eagle-import:569-011X-X00_LED_ARRAY")
      (libsource (lib "eagle-import") (part "LED_2X_VERTICAL"))
    )
    (comp (ref "TP1")
      (value "GND(ISO)")
      (footprint "eagle-import:TESTPOINT_1MM")
      (libsource (lib "eagle-import") (part "TP_1MM"))
    )
    (comp (ref "TP2")
      (value "+1.8V(ISO)")
      (footprint "eagle-import:TESTPOINT_1MM")
      (libsource (lib "eagle-import") (part "TP_1MM"))
    )
    (comp (ref "TP3")
      (value "+3.3V(ISO)")
      (footprint "eagle-import:TESTPOINT_2MM")
      (libsource (lib "eagle-import") (part "TP_2MM"))
    )
    (comp (ref "TP4")
      (value "+5.5V(ISO)")
      (footprint "eagle-import:TESTPOINT_2MM")
      (libsource (lib "eagle-import") (part "TP_2MM"))
    )
    (comp (ref "TP5")
      (value "PASS")
      (footprint "eagle-import:TP06R")
      (libsource (lib "eagle-import") (part "TPTP06R"))
    )
    (comp (ref "TP6")
      (value "DI1")
      (footprint "eagle-import:TP09SQ")
      (libsource (lib "eagle-import") (part "TPTP09SQ"))
    )
    (comp (ref "TP7")
      (value "DI0")
      (footprint "eagle-import:TP09SQ")
      (libsource (lib "eagle-import") (part "TPTP09SQ"))
    )
    (comp (ref "TP8")
      (value "GND")
      (footprint "eagle-import:TESTPOINT_0.035IN")
      (libsource (lib "eagle-import") (part "TP_0.035IN"))
    )
    (comp (ref "TP9")
      (value "VPROTECT(+4.3V)")
      (footprint "eagle-import:TESTPOINT_0.035IN")
      (libsource (lib "eagle-import") (part "TP_0.035IN"))
    )
    (comp (ref "TP10")
      (value "GND")
      (footprint "eagle-import:TESTPOINT_2MM")
      (libsource (lib "eagle-import") (part "TP_2MM"))
    )
    (comp (ref "TP11")
      (value "+3.3V")
      (footprint "eagle-import:TESTPOINT_2MM")
      (libsource (lib "eagle-import") (part "TP_2MM"))
    )
    (comp (ref "TP12")
      (value "+12V(FPGA)")
      (footprint "eagle-import:TESTPOINT_2MM")
      (libsource (lib "eagle-import") (part "TP_2MM"))
    )
    (comp (ref "TP13")
      (value "+12V(ATX)")
      (footprint "eagle-import:TESTPOINT_2MM")
      (libsource (lib "eagle-import") (part "TP_2MM"))
    )
    (comp (ref "TP14")
      (value "GND")
      (footprint "eagle-import:TESTPOINT_2MM")
      (libsource (lib "eagle-import") (part "TP_2MM"))
    )
    (comp (ref "TP15")
      (value "GND")
      (footprint "eagle-import:TESTPOINT_2MM")
      (libsource (lib "eagle-import") (part "TP_2MM"))
    )
    (comp (ref "TP16")
      (value "GND")
      (footprint "eagle-import:TESTPOINT_2MM")
      (libsource (lib "eagle-import") (part "TP_2MM"))
    )
    (comp (ref "TP17")
      (value "GND")
      (footprint "eagle-import:TESTPOINT_2MM")
      (libsource (lib "eagle-import") (part "TP_2MM"))
    )
    (comp (ref "TP18")
      (value "GND(ISO)")
      (footprint "eagle-import:TESTPOINT_1MM")
      (libsource (lib "eagle-import") (part "TP_1MM"))
    )
    (comp (ref "TP19")
      (value "GND(ISO)")
      (footprint "eagle-import:TESTPOINT_1MM")
      (libsource (lib "eagle-import") (part "TP_1MM"))
    )
    (comp (ref "TP20")
      (value "GND(ISO)")
      (footprint "eagle-import:TESTPOINT_1MM")
      (libsource (lib "eagle-import") (part "TP_1MM"))
    )
    (comp (ref "TP21")
      (value "GND")
      (footprint "eagle-import:TESTPOINT_2MM")
      (libsource (lib "eagle-import") (part "TP_2MM"))
    )
    (comp (ref "TP22")
      (value "+3.3V")
      (footprint "eagle-import:TESTPOINT_2MM")
      (libsource (lib "eagle-import") (part "TP_2MM"))
    )
    (comp (ref "TP23")
      (value "GND")
      (footprint "eagle-import:TESTPOINT_1MM")
      (libsource (lib "eagle-import") (part "TP_1MM"))
    )
    (comp (ref "TP24")
      (value "SDA")
      (footprint "eagle-import:TESTPOINT_1MM")
      (libsource (lib "eagle-import") (part "TP_1MM"))
    )
    (comp (ref "TP25")
      (value "SCL")
      (footprint "eagle-import:TESTPOINT_1MM")
      (libsource (lib "eagle-import") (part "TP_1MM"))
    )
    (comp (ref "TP26")
      (value "SCL(ISO)")
      (footprint "eagle-import:TESTPOINT_1MM")
      (libsource (lib "eagle-import") (part "TP_1MM"))
    )
    (comp (ref "TP27")
      (value "SDA(ISO)")
      (footprint "eagle-import:TESTPOINT_1MM")
      (libsource (lib "eagle-import") (part "TP_1MM"))
    )
    (comp (ref "TP28")
      (value "GND(ISO)")
      (footprint "eagle-import:TESTPOINT_1MM")
      (libsource (lib "eagle-import") (part "TP_1MM"))
    )
    (comp (ref "TP29")
      (value "GPIO3")
      (footprint "eagle-import:TP06R")
      (libsource (lib "eagle-import") (part "TPTP06R"))
    )
    (comp (ref "U$2")
      (value "MOLEX_DUAL_STACKED_VHDCI")
      (footprint "eagle-import:MOLEX_743370911_SD_DUAL_STACKED_VHDCI")
      (libsource (lib "eagle-import") (part "MOLEX_DUAL_STACKED_VHDCI"))
    )
    (comp (ref "U1")
      (value "ISO")
      (footprint "eagle-import:SCREW4")
      (libsource (lib "eagle-import") (part "SCREW4"))
    )
    (comp (ref "U2")
      (value "JP3E")
      (footprint "eagle-import:JP3")
      (libsource (lib "eagle-import") (part "JP3E"))
    )
    (comp (ref "U3")
      (value "JP3E")
      (footprint "eagle-import:JP3")
      (libsource (lib "eagle-import") (part "JP3E"))
    )
    (comp (ref "U4")
      (value "SN74LVT125")
      (footprint "eagle-import:SO14")
      (libsource (lib "eagle-import") (part "QUAD-LINE-DRIVER_SOIC"))
    )
    (comp (ref "U5")
      (value "ADCMP600")
      (footprint "eagle-import:SOT-23-5")
      (libsource (lib "eagle-import") (part "COMPARITOR_ADCMP600"))
    )
    (comp (ref "U6")
      (value "ADCMP600")
      (footprint "eagle-import:SOT-23-5")
      (libsource (lib "eagle-import") (part "COMPARITOR_ADCMP600"))
    )
    (comp (ref "U7")
      (value "DIPSW-004_SMD-0.05IN")
      (footprint "eagle-import:DIP04-SMD")
      (libsource (lib "eagle-import") (part "DIPSW-004_SMD-0.05IN"))
    )
    (comp (ref "U8")
      (value "MCP47FEBX2")
      (footprint "eagle-import:TSSOP-8")
      (libsource (lib "eagle-import") (part "MCP47FEBX2"))
    )
    (comp (ref "U9")
      (value "DS90UB914A-Q1")
      (footprint "eagle-import:WQFN48")
      (libsource (lib "eagle-import") (part "DS90UB914A-Q1"))
    )
    (comp (ref "U10")
      (value "LTM4622_BGA")
      (footprint "eagle-import:BGA_5X5_625X625")
      (libsource (lib "eagle-import") (part "LTM4622_BGA"))
    )
    (comp (ref "U11")
      (value "ISO1540DR")
      (footprint "eagle-import:SOIC127P500X400-8N")
      (libsource (lib "eagle-import") (part "DIGISO-I2C_SOIC"))
    )
    (comp (ref "U12")
      (value "UEI15-050-Q12P-C")
      (footprint "eagle-import:UEI15")
      (libsource (lib "eagle-import") (part "DC-DC-CONVERTER-ADJ_UEI15"))
    )
    (comp (ref "U13")
      (value "ISO7240M")
      (footprint "eagle-import:SOIC_WIDE_16")
      (libsource (lib "eagle-import") (part "DIGISO-4-0"))
    )
    (comp (ref "U14")
      (value "ISO7240M")
      (footprint "eagle-import:SOIC_WIDE_16")
      (libsource (lib "eagle-import") (part "DIGISO-4-0"))
    )
    (comp (ref "U15")
      (value "ISO7240M")
      (footprint "eagle-import:SOIC_WIDE_16")
      (libsource (lib "eagle-import") (part "DIGISO-4-0"))
    )
    (comp (ref "U16")
      (value "ISO7240M")
      (footprint "eagle-import:SOIC_WIDE_16")
      (libsource (lib "eagle-import") (part "DIGISO-4-0"))
    )
    (comp (ref "U17")
      (value "ISO7242M")
      (footprint "eagle-import:SOIC_WIDE_16")
      (libsource (lib "eagle-import") (part "DIGISO-2-2"))
    )
    (comp (ref "U18")
      (value "COMM")
      (footprint "eagle-import:SCREW4")
      (libsource (lib "eagle-import") (part "SCREW4"))
    )
    (comp (ref "U19")
      (value "SN65LVDT388A")
      (footprint "eagle-import:TSSOP-38")
      (libsource (lib "eagle-import") (part "SN65LVDS388A"))
    )
    (comp (ref "U20")
      (value "SN65LVDS387")
      (footprint "eagle-import:TSSOP-64")
      (libsource (lib "eagle-import") (part "SN65LVDS387_TSSOP"))
    )
    (comp (ref "U21")
      (value "SN65LVDS391")
      (footprint "eagle-import:TSSOP-16")
      (libsource (lib "eagle-import") (part "SN65LVDS391"))
    )
    (comp (ref "X1")
      (value "PCI-MECH_STD-H_HALF-W_FMC-STRAIN")
      (footprint "eagle-import:PCI-ADDIN_STD-H_HALF-L_FMC-STRAIN")
      (libsource (lib "eagle-import") (part "PCI-MECH_STD-H_HALF-W_FMC-STRAIN"))
    )
  )
  (nets
    (net (code "1") (name "+3V3") (class "Default")
      (node (ref "C1") (pin "2") (pinfunction "2_2") (pintype "passive"))
      (node (ref "C2") (pin "2") (pinfunction "2_2") (pintype "passive"))
      (node (ref "C20") (pin "2") (pinfunction "2_2") (pintype "passive"))
      (node (ref "C25") (pin "2") (pinfunction "2_2") (pintype "passive"))
      (node (ref "C56") (pin "2") (pinfunction "2_2") (pintype "passive"))
      (node (ref "C57") (pin "2") (pinfunction "2_2") (pintype "passive"))
      (node (ref "C58") (pin "2") (pinfunction "2_2") (pintype "passive"))
      (node (ref "C59") (pin "2") (pinfunction "2_2") (pintype "passive"))
      (node (ref "C60") (pin "2") (pinfunction "2_2") (pintype "passive"))
      (node (ref "C61") (pin "2") (pinfunction "2_2") (pintype "passive"))
      (node (ref "C8") (pin "1") (pinfunction "1_1") (pintype "passive"))
      (node (ref "C81") (pin "2") (pinfunction "2_2") (pintype "passive"))
      (node (ref "C83") (pin "2") (pinfunction "2_2") (pintype "passive"))
      (node (ref "C84") (pin "2") (pinfunction "2_2") (pintype "passive"))
      (node (ref "C85") (pin "2") (pinfunction "2_2") (pintype "passive"))
      (node (ref "C86") (pin "2") (pinfunction "2_2") (pintype "passive"))
      (node (ref "C87") (pin "+") (pinfunction "+_+") (pintype "passive"))
      (node (ref "C88") (pin "2") (pinfunction "2_2") (pintype "passive"))
      (node (ref "C89") (pin "2") (pinfunction "2_2") (pintype "passive"))
      (node (ref "C9") (pin "1") (pinfunction "1_1") (pintype "passive"))
      (node (ref "C90") (pin "2") (pinfunction "2_2") (pintype "passive"))
      (node (ref "C91") (pin "2") (pinfunction "2_2") (pintype "passive"))
      (node (ref "C92") (pin "2") (pinfunction "2_2") (pintype "passive"))
      (node (ref "C93") (pin "2") (pinfunction "2_2") (pintype "passive"))
      (node (ref "C94") (pin "2") (pinfunction "2_2") (pintype "passive"))
      (node (ref "C95") (pin "2") (pinfunction "2_2") (pintype "passive"))
      (node (ref "C96") (pin "2") (pinfunction "2_2") (pintype "passive"))
      (node (ref "C97") (pin "2") (pinfunction "2_2") (pintype "passive"))
      (node (ref "C98") (pin "2") (pinfunction "2_2") (pintype "passive"))
      (node (ref "FMC_LPC") (pin "P$116") (pinfunction "3P3V2_P$116") (pintype "bidirectional"))
      (node (ref "FMC_LPC") (pin "P$118") (pinfunction "3P3V3_P$118") (pintype "bidirectional"))
      (node (ref "FMC_LPC") (pin "P$120") (pinfunction "3P3V4_P$120") (pintype "bidirectional"))
      (node (ref "FMC_LPC") (pin "P$159") (pinfunction "3P3V1_P$159") (pintype "bidirectional"))
      (node (ref "R1") (pin "2") (pinfunction "2_2") (pintype "passive"))
      (node (ref "R2") (pin "2") (pinfunction "2_2") (pintype "passive"))
      (node (ref "R31") (pin "2") (pinfunction "2_2") (pintype "passive"))
      (node (ref "R32") (pin "2") (pinfunction "2_2") (pintype "passive"))
      (node (ref "R67") (pin "2") (pinfunction "2_2") (pintype "passive"))
      (node (ref "R71") (pin "2") (pinfunction "2_2") (pintype "passive"))
      (node (ref "R72") (pin "2") (pinfunction "2_2") (pintype "passive"))
      (node (ref "TP11") (pin "1") (pinfunction "TP_1") (pintype "bidirectional"))
      (node (ref "TP22") (pin "1") (pinfunction "TP_1") (pintype "bidirectional"))
      (node (ref "U11") (pin "1") (pinfunction "VDD1_1") (pintype "power_in"))
      (node (ref "U13") (pin "P10") (pinfunction "EN2_P10") (pintype "bidirectional"))
      (node (ref "U13") (pin "P16") (pinfunction "VDD2_P16") (pintype "power_in"))
      (node (ref "U14") (pin "P10") (pinfunction "EN2_P10") (pintype "bidirectional"))
      (node (ref "U14") (pin "P16") (pinfunction "VDD2_P16") (pintype "power_in"))
      (node (ref "U15") (pin "P10") (pinfunction "EN2_P10") (pintype "bidirectional"))
      (node (ref "U15") (pin "P16") (pinfunction "VDD2_P16") (pintype "power_in"))
      (node (ref "U16") (pin "P10") (pinfunction "EN2_P10") (pintype "bidirectional"))
      (node (ref "U16") (pin "P16") (pinfunction "VDD2_P16") (pintype "power_in"))
      (node (ref "U17") (pin "P10") (pinfunction "EN2_P10") (pintype "bidirectional"))
      (node (ref "U17") (pin "P16") (pinfunction "VDD2_P16") (pintype "power_in"))
      (node (ref "U18") (pin "2") (pinfunction "2_2") (pintype "bidirectional"))
      (node (ref "U19") (pin "21") (pinfunction "VCC_21") (pintype "power_in"))
      (node (ref "U19") (pin "22") (pinfunction "END_22") (pintype "input"))
      (node (ref "U19") (pin "25") (pinfunction "ENC_25") (pintype "input"))
      (node (ref "U19") (pin "29") (pinfunction "DVCC_29") (pintype "power_in"))
      (node (ref "U19") (pin "33") (pinfunction "ENB_33") (pintype "input"))
      (node (ref "U19") (pin "36") (pinfunction "ENA_36") (pintype "input"))
      (node (ref "U19") (pin "37") (pinfunction "VCC_37") (pintype "power_in"))
      (node (ref "U20") (pin "10") (pinfunction "ENB_10") (pintype "input"))
      (node (ref "U20") (pin "16") (pinfunction "VCC_16") (pintype "power_in"))
      (node (ref "U20") (pin "17") (pinfunction "VCC_17") (pintype "power_in"))
      (node (ref "U20") (pin "2") (pinfunction "VCC_2") (pintype "power_in"))
      (node (ref "U20") (pin "23") (pinfunction "ENC_23") (pintype "input"))
      (node (ref "U20") (pin "28") (pinfunction "END_28") (pintype "input"))
      (node (ref "U20") (pin "3") (pinfunction "VCC_3") (pintype "power_in"))
      (node (ref "U20") (pin "30") (pinfunction "VCC_30") (pintype "power_in"))
      (node (ref "U20") (pin "31") (pinfunction "VCC_31") (pintype "power_in"))
      (node (ref "U20") (pin "5") (pinfunction "ENA_5") (pintype "input"))
      (node (ref "U21") (pin "1") (pinfunction "EN1,2_1") (pintype "input"))
      (node (ref "U21") (pin "4") (pinfunction "VCC_4") (pintype "power_in"))
      (node (ref "U21") (pin "8") (pinfunction "EN3,4_8") (pintype "input"))
      (node (ref "U4") (pin "14") (pinfunction "VCC_14") (pintype "passive"))
      (node (ref "U5") (pin "5") (pinfunction "V+_5") (pintype "power_in"))
      (node (ref "U6") (pin "5") (pinfunction "V+_5") (pintype "power_in"))
      (node (ref "U8") (pin "1") (pinfunction "VDD_1") (pintype "power_in"))
      (node (ref "U8") (pin "2") (pinfunction "REFA_2") (pintype "input"))
    )
    (net (code "2") (name "+3V3_ISO") (class "Default")
      (node (ref "C21") (pin "2") (pinfunction "2_2") (pintype "passive"))
      (node (ref "C27") (pin "2") (pinfunction "2_2") (pintype "passive"))
      (node (ref "C28") (pin "2") (pinfunction "2_2") (pintype "passive"))
      (node (ref "C29") (pin "2") (pinfunction "2_2") (pintype "passive"))
      (node (ref "C30") (pin "2") (pinfunction "2_2") (pintype "passive"))
      (node (ref "C34") (pin "2") (pinfunction "2_2") (pintype "passive"))
      (node (ref "C38") (pin "2") (pinfunction "2_2") (pintype "passive"))
      (node (ref "C49") (pin "2") (pinfunction "2_2") (pintype "passive"))
      (node (ref "C50") (pin "2") (pinfunction "2_2") (pintype "passive"))
      (node (ref "C51") (pin "2") (pinfunction "2_2") (pintype "passive"))
      (node (ref "C52") (pin "2") (pinfunction "2_2") (pintype "passive"))
      (node (ref "C53") (pin "2") (pinfunction "2_2") (pintype "passive"))
      (node (ref "C54") (pin "2") (pinfunction "2_2") (pintype "passive"))
      (node (ref "R14") (pin "2") (pinfunction "2_2") (pintype "passive"))
      (node (ref "R15") (pin "2") (pinfunction "2_2") (pintype "passive"))
      (node (ref "R18") (pin "2") (pinfunction "2_2") (pintype "passive"))
      (node (ref "R19") (pin "2") (pinfunction "2_2") (pintype "passive"))
      (node (ref "R25") (pin "1") (pinfunction "1_1") (pintype "passive"))
      (node (ref "R46") (pin "2") (pinfunction "2_2") (pintype "passive"))
      (node (ref "R65") (pin "2") (pinfunction "2_2") (pintype "passive"))
      (node (ref "R66") (pin "2") (pinfunction "2_2") (pintype "passive"))
      (node (ref "R75") (pin "2") (pinfunction "2_2") (pintype "passive"))
      (node (ref "TP3") (pin "1") (pinfunction "TP_1") (pintype "bidirectional"))
      (node (ref "U1") (pin "3") (pinfunction "3_3") (pintype "bidirectional"))
      (node (ref "U10") (pin "A1") (pinfunction "VOUT2_A1") (pintype "power_in"))
      (node (ref "U10") (pin "B1") (pinfunction "VOUT2_B1") (pintype "power_in"))
      (node (ref "U11") (pin "8") (pinfunction "VDD2_8") (pintype "power_in"))
      (node (ref "U13") (pin "P1") (pinfunction "VDD1_P1") (pintype "power_in"))
      (node (ref "U14") (pin "P1") (pinfunction "VDD1_P1") (pintype "power_in"))
      (node (ref "U15") (pin "P1") (pinfunction "VDD1_P1") (pintype "power_in"))
      (node (ref "U16") (pin "P1") (pinfunction "VDD1_P1") (pintype "power_in"))
      (node (ref "U17") (pin "P1") (pinfunction "VDD1_P1") (pintype "power_in"))
      (node (ref "U9") (pin "20") (pinfunction "VDDIO2_20") (pintype "bidirectional"))
      (node (ref "U9") (pin "29") (pinfunction "VDDIO1_29") (pintype "bidirectional"))
      (node (ref "U9") (pin "7") (pinfunction "VDDIO3_7") (pintype "bidirectional"))
    )
    (net (code "3") (name "+3V3_ISO_PG_ISO") (class "Default")
      (node (ref "R56") (pin "2") (pinfunction "2_2") (pintype "passive"))
      (node (ref "U10") (pin "D4") (pinfunction "PGOOD1_D4") (pintype "open_collector"))
      (node (ref "U16") (pin "P6") (pinfunction "VID_P6") (pintype "input"))
    )
    (net (code "4") (name "+3V3_ISO_PG_N") (class "Default")
      (node (ref "FMC_LPC") (pin "P$89") (pinfunction "LA01_N_CC_P$89") (pintype "bidirectional"))
      (node (ref "U20") (pin "33") (pinfunction "D4Z_33") (pintype "output"))
    )
    (net (code "5") (name "+3V3_ISO_PG_P") (class "Default")
      (node (ref "FMC_LPC") (pin "P$88") (pinfunction "LA01_P_CC_P$88") (pintype "bidirectional"))
      (node (ref "U20") (pin "34") (pinfunction "D4Y_34") (pintype "output"))
    )
    (net (code "6") (name "/+1V8_ISO") (class "Default")
      (node (ref "C24") (pin "2") (pinfunction "2_2") (pintype "passive"))
      (node (ref "C31") (pin "2") (pinfunction "2_2") (pintype "passive"))
      (node (ref "C32") (pin "2") (pinfunction "2_2") (pintype "passive"))
      (node (ref "C33") (pin "2") (pinfunction "2_2") (pintype "passive"))
      (node (ref "C35") (pin "2") (pinfunction "2_2") (pintype "passive"))
      (node (ref "C36") (pin "2") (pinfunction "2_2") (pintype "passive"))
      (node (ref "C37") (pin "2") (pinfunction "2_2") (pintype "passive"))
      (node (ref "L4") (pin "2") (pinfunction "2_2") (pintype "passive"))
      (node (ref "L5") (pin "2") (pinfunction "2_2") (pintype "passive"))
      (node (ref "L6") (pin "1") (pinfunction "1_1") (pintype "passive"))
      (node (ref "R57") (pin "1") (pinfunction "1_1") (pintype "passive"))
      (node (ref "R60") (pin "1") (pinfunction "1_1") (pintype "passive"))
      (node (ref "R62") (pin "1") (pinfunction "1_1") (pintype "passive"))
      (node (ref "TP2") (pin "1") (pinfunction "TP_1") (pintype "bidirectional"))
      (node (ref "U1") (pin "2") (pinfunction "2_2") (pintype "bidirectional"))
      (node (ref "U10") (pin "D1") (pinfunction "VOUT1_D1") (pintype "power_in"))
      (node (ref "U10") (pin "E1") (pinfunction "VOUT1_E1") (pintype "power_in"))
      (node (ref "U9") (pin "17") (pinfunction "VDDD_17") (pintype "power_in"))
      (node (ref "U9") (pin "3") (pinfunction "VDDSSCG_3") (pintype "power_in"))
      (node (ref "U9") (pin "36") (pinfunction "VDDR_36") (pintype "power_in"))
    )
    (net (code "7") (name "/+3V3_ISO_PG") (class "Default")
      (node (ref "U16") (pin "P11") (pinfunction "VOD_P11") (pintype "output"))
      (node (ref "U20") (pin "27") (pinfunction "D4A_27") (pintype "input"))
    )
    (net (code "8") (name "/+5.5V_ISO") (class "Default")
      (node (ref "C13") (pin "2") (pinfunction "2_2") (pintype "passive"))
      (node (ref "C17") (pin "1") (pinfunction "1_1") (pintype "passive"))
      (node (ref "C42") (pin "2") (pinfunction "2_2") (pintype "passive"))
      (node (ref "C45") (pin "2") (pinfunction "2_2") (pintype "passive"))
      (node (ref "C47") (pin "+") (pinfunction "+_+") (pintype "passive"))
      (node (ref "C48") (pin "+") (pinfunction "+_+") (pintype "passive"))
      (node (ref "L3") (pin "1") (pinfunction "1_1") (pintype "passive"))
      (node (ref "TP4") (pin "1") (pinfunction "TP_1") (pintype "bidirectional"))
      (node (ref "U10") (pin "A2") (pinfunction "VIN_A2") (pintype "power_in"))
      (node (ref "U10") (pin "B2") (pinfunction "RUN2_B2") (pintype "input"))
      (node (ref "U10") (pin "B3") (pinfunction "VIN_B3") (pintype "power_in"))
      (node (ref "U10") (pin "D2") (pinfunction "RUN1_D2") (pintype "input"))
      (node (ref "U10") (pin "D3") (pinfunction "VIN_D3") (pintype "power_in"))
      (node (ref "U10") (pin "E2") (pinfunction "VIN_E2") (pintype "power_in"))
      (node (ref "U12") (pin "3") (pinfunction "+VO_3") (pintype "power_in"))
    )
    (net (code "9") (name "/+12V_ATX") (class "Default")
      (node (ref "C44") (pin "+") (pinfunction "+_+") (pintype "passive"))
      (node (ref "C46") (pin "+") (pinfunction "+_+") (pintype "passive"))
      (node (ref "L7/0R") (pin "1") (pinfunction "1_1") (pintype "passive"))
      (node (ref "PCIE-PWR") (pin "1") (pinfunction "1_1") (pintype "passive"))
      (node (ref "PCIE-PWR") (pin "2") (pinfunction "2_2") (pintype "passive"))
      (node (ref "PCIE-PWR") (pin "3") (pinfunction "3_3") (pintype "passive"))
      (node (ref "TP13") (pin "1") (pinfunction "TP_1") (pintype "bidirectional"))
    )
    (net (code "10") (name "/+12V_FPGA") (class "Default")
      (node (ref "C66") (pin "+") (pinfunction "+_+") (pintype "passive"))
      (node (ref "C80") (pin "2") (pinfunction "2_2") (pintype "passive"))
      (node (ref "C82") (pin "2") (pinfunction "2_2") (pintype "passive"))
      (node (ref "FMC_LPC") (pin "P$155") (pinfunction "12P0V1_P$155") (pintype "bidirectional"))
      (node (ref "FMC_LPC") (pin "P$157") (pinfunction "12P0V2_P$157") (pintype "bidirectional"))
      (node (ref "R69") (pin "2") (pinfunction "2_2") (pintype "passive"))
      (node (ref "R70") (pin "2") (pinfunction "2_2") (pintype "passive"))
      (node (ref "TP12") (pin "1") (pinfunction "TP_1") (pintype "bidirectional"))
      (node (ref "U18") (pin "3") (pinfunction "3_3") (pintype "bidirectional"))
    )
    (net (code "11") (name "/BISTEN") (class "Default")
      (node (ref "R19") (pin "1") (pinfunction "1_1") (pintype "passive"))
      (node (ref "U7") (pin "1") (pinfunction "1_1") (pintype "passive"))
      (node (ref "U9") (pin "6") (pinfunction "BISTEN_6") (pintype "input"))
    )
    (net (code "12") (name "/D0") (class "Default")
      (node (ref "U13") (pin "P14") (pinfunction "VOA_P14") (pintype "output"))
      (node (ref "U20") (pin "6") (pinfunction "A1A_6") (pintype "input"))
    )
    (net (code "13") (name "/D1") (class "Default")
      (node (ref "U13") (pin "P13") (pinfunction "VOB_P13") (pintype "output"))
      (node (ref "U20") (pin "7") (pinfunction "A2A_7") (pintype "input"))
    )
    (net (code "14") (name "/D2") (class "Default")
      (node (ref "U13") (pin "P12") (pinfunction "VOC_P12") (pintype "output"))
      (node (ref "U20") (pin "8") (pinfunction "A3A_8") (pintype "input"))
    )
    (net (code "15") (name "/D3") (class "Default")
      (node (ref "U13") (pin "P11") (pinfunction "VOD_P11") (pintype "output"))
      (node (ref "U20") (pin "9") (pinfunction "A4A_9") (pintype "input"))
    )
    (net (code "16") (name "/D4") (class "Default")
      (node (ref "U14") (pin "P14") (pinfunction "VOA_P14") (pintype "output"))
      (node (ref "U20") (pin "11") (pinfunction "B1A_11") (pintype "input"))
    )
    (net (code "17") (name "/D5") (class "Default")
      (node (ref "U14") (pin "P13") (pinfunction "VOB_P13") (pintype "output"))
      (node (ref "U20") (pin "12") (pinfunction "B2A_12") (pintype "input"))
    )
    (net (code "18") (name "/D6") (class "Default")
      (node (ref "U14") (pin "P12") (pinfunction "VOC_P12") (pintype "output"))
      (node (ref "U20") (pin "13") (pinfunction "B3A_13") (pintype "input"))
    )
    (net (code "19") (name "/D7") (class "Default")
      (node (ref "U14") (pin "P11") (pinfunction "VOD_P11") (pintype "output"))
      (node (ref "U20") (pin "14") (pinfunction "B4A_14") (pintype "input"))
    )
    (net (code "20") (name "/D8") (class "Default")
      (node (ref "U15") (pin "P14") (pinfunction "VOA_P14") (pintype "output"))
      (node (ref "U20") (pin "19") (pinfunction "C1A_19") (pintype "input"))
    )
    (net (code "21") (name "/D9") (class "Default")
      (node (ref "U15") (pin "P13") (pinfunction "VOB_P13") (pintype "output"))
      (node (ref "U20") (pin "20") (pinfunction "C2A_20") (pintype "input"))
    )
    (net (code "22") (name "/D10") (class "Default")
      (node (ref "U15") (pin "P12") (pinfunction "VOC_P12") (pintype "output"))
      (node (ref "U20") (pin "21") (pinfunction "C3A_21") (pintype "input"))
    )
    (net (code "23") (name "/D11") (class "Default")
      (node (ref "U15") (pin "P11") (pinfunction "VOD_P11") (pintype "output"))
      (node (ref "U20") (pin "22") (pinfunction "C4A_22") (pintype "input"))
    )
    (net (code "24") (name "/DOUTP_F") (class "Default")
      (node (ref "C16") (pin "2") (pinfunction "2_2") (pintype "passive"))
      (node (ref "L1") (pin "2") (pinfunction "2_2") (pintype "passive"))
      (node (ref "LINK") (pin "CLK") (pinfunction "1_CLK") (pintype "passive"))
      (node (ref "R7") (pin "2") (pinfunction "2_2") (pintype "passive"))
    )
    (net (code "25") (name "/HSYNC") (class "Default")
      (node (ref "U16") (pin "P14") (pinfunction "VOA_P14") (pintype "output"))
      (node (ref "U20") (pin "24") (pinfunction "D1A_24") (pintype "input"))
    )
    (net (code "26") (name "/OEN") (class "Default")
      (node (ref "R15") (pin "1") (pinfunction "1_1") (pintype "passive"))
      (node (ref "U7") (pin "2") (pinfunction "2_2") (pintype "passive"))
      (node (ref "U9") (pin "5") (pinfunction "OEN_5") (pintype "input"))
    )
    (net (code "27") (name "/OSS_SEL") (class "Default")
      (node (ref "R18") (pin "1") (pinfunction "1_1") (pintype "passive"))
      (node (ref "U7") (pin "3") (pinfunction "3_3") (pintype "passive"))
      (node (ref "U9") (pin "4") (pinfunction "OSS_SEL_4") (pintype "input"))
    )
    (net (code "28") (name "/PCLK") (class "Default")
      (node (ref "U16") (pin "P12") (pinfunction "VOC_P12") (pintype "output"))
      (node (ref "U20") (pin "26") (pinfunction "D3A_26") (pintype "input"))
    )
    (net (code "29") (name "/SEL") (class "Default")
      (node (ref "R14") (pin "1") (pinfunction "1_1") (pintype "passive"))
      (node (ref "U7") (pin "4") (pinfunction "4_4") (pintype "passive"))
      (node (ref "U9") (pin "46") (pinfunction "SEL_46") (pintype "input"))
    )
    (net (code "30") (name "/VSYNC") (class "Default")
      (node (ref "U16") (pin "P13") (pinfunction "VOB_P13") (pintype "output"))
      (node (ref "U20") (pin "25") (pinfunction "D2A_25") (pintype "input"))
    )
    (net (code "31") (name "2V5_REF") (class "Default")
      (node (ref "D5") (pin "1") (pinfunction "C_1") (pintype "passive"))
      (node (ref "R67") (pin "1") (pinfunction "1_1") (pintype "passive"))
      (node (ref "U2") (pin "3") (pinfunction "3_3") (pintype "passive"))
      (node (ref "U3") (pin "3") (pinfunction "3_3") (pintype "passive"))
    )
    (net (code "32") (name "BIAS_DI0") (class "Default")
      (node (ref "U2") (pin "1") (pinfunction "1_1") (pintype "passive"))
      (node (ref "U8") (pin "3") (pinfunction "VOUT0_3") (pintype "output"))
    )
    (net (code "33") (name "BIAS_DI1") (class "Default")
      (node (ref "U3") (pin "1") (pinfunction "1_1") (pintype "passive"))
      (node (ref "U8") (pin "4") (pinfunction "VOUT1_4") (pintype "output"))
    )
    (net (code "34") (name "D0_ISO") (class "Default")
      (node (ref "R54") (pin "1") (pinfunction "1_1") (pintype "passive"))
      (node (ref "U13") (pin "P3") (pinfunction "VIA_P3") (pintype "input"))
    )
    (net (code "35") (name "D0_N") (class "Default")
      (node (ref "FMC_LPC") (pin "P$98") (pinfunction "LA13_N_P$98") (pintype "bidirectional"))
      (node (ref "U20") (pin "63") (pinfunction "A1Z_63") (pintype "output"))
    )
    (net (code "36") (name "D0_P") (class "Default")
      (node (ref "FMC_LPC") (pin "P$97") (pinfunction "LA13_P_P$97") (pintype "bidirectional"))
      (node (ref "U20") (pin "64") (pinfunction "A1Y_64") (pintype "output"))
    )
    (net (code "37") (name "D1_ISO") (class "Default")
      (node (ref "R38") (pin "1") (pinfunction "1_1") (pintype "passive"))
      (node (ref "U13") (pin "P4") (pinfunction "VIB_P4") (pintype "input"))
    )
    (net (code "38") (name "D1_N") (class "Default")
      (node (ref "FMC_LPC") (pin "P$17") (pinfunction "LA11_N_P$17") (pintype "bidirectional"))
      (node (ref "U20") (pin "61") (pinfunction "A2Z_61") (pintype "output"))
    )
    (net (code "39") (name "D1_P") (class "Default")
      (node (ref "FMC_LPC") (pin "P$16") (pinfunction "LA11_P_P$16") (pintype "bidirectional"))
      (node (ref "U20") (pin "62") (pinfunction "A2Y_62") (pintype "output"))
    )
    (net (code "40") (name "D2_ISO") (class "Default")
      (node (ref "R45") (pin "1") (pinfunction "1_1") (pintype "passive"))
      (node (ref "U13") (pin "P5") (pinfunction "VIC_P5") (pintype "input"))
    )
    (net (code "41") (name "D2_N") (class "Default")
      (node (ref "FMC_LPC") (pin "P$56") (pinfunction "LA12_N_P$56") (pintype "bidirectional"))
      (node (ref "U20") (pin "59") (pinfunction "A3Z_59") (pintype "output"))
    )
    (net (code "42") (name "D2_P") (class "Default")
      (node (ref "FMC_LPC") (pin "P$55") (pinfunction "LA12_P_P$55") (pintype "bidirectional"))
      (node (ref "U20") (pin "60") (pinfunction "A3Y_60") (pintype "output"))
    )
    (net (code "43") (name "D3_ISO") (class "Default")
      (node (ref "R53") (pin "1") (pinfunction "1_1") (pintype "passive"))
      (node (ref "U13") (pin "P6") (pinfunction "VID_P6") (pintype "input"))
    )
    (net (code "44") (name "D3_N") (class "Default")
      (node (ref "FMC_LPC") (pin "P$135") (pinfunction "LA10_N_P$135") (pintype "bidirectional"))
      (node (ref "U20") (pin "57") (pinfunction "A4Z_57") (pintype "output"))
    )
    (net (code "45") (name "D3_P") (class "Default")
      (node (ref "FMC_LPC") (pin "P$134") (pinfunction "LA10_P_P$134") (pintype "bidirectional"))
      (node (ref "U20") (pin "58") (pinfunction "A4Y_58") (pintype "output"))
    )
    (net (code "46") (name "D4_ISO") (class "Default")
      (node (ref "R37") (pin "1") (pinfunction "1_1") (pintype "passive"))
      (node (ref "U14") (pin "P3") (pinfunction "VIA_P3") (pintype "input"))
    )
    (net (code "47") (name "D4_N") (class "Default")
      (node (ref "FMC_LPC") (pin "P$95") (pinfunction "LA09_N_P$95") (pintype "bidirectional"))
      (node (ref "U20") (pin "55") (pinfunction "B1Z_55") (pintype "output"))
    )
    (net (code "48") (name "D4_P") (class "Default")
      (node (ref "FMC_LPC") (pin "P$94") (pinfunction "LA09_P_P$94") (pintype "bidirectional"))
      (node (ref "U20") (pin "56") (pinfunction "B1Y_56") (pintype "output"))
    )
    (net (code "49") (name "D5_ISO") (class "Default")
      (node (ref "R44") (pin "1") (pinfunction "1_1") (pintype "passive"))
      (node (ref "U14") (pin "P4") (pinfunction "VIB_P4") (pintype "input"))
    )
    (net (code "50") (name "D5_N") (class "Default")
      (node (ref "FMC_LPC") (pin "P$14") (pinfunction "LA07_N_P$14") (pintype "bidirectional"))
      (node (ref "U20") (pin "53") (pinfunction "B2Z_53") (pintype "output"))
    )
    (net (code "51") (name "D5_P") (class "Default")
      (node (ref "FMC_LPC") (pin "P$13") (pinfunction "LA07_P_P$13") (pintype "bidirectional"))
      (node (ref "U20") (pin "54") (pinfunction "B2Y_54") (pintype "output"))
    )
    (net (code "52") (name "D6_ISO") (class "Default")
      (node (ref "R52") (pin "1") (pinfunction "1_1") (pintype "passive"))
      (node (ref "U14") (pin "P5") (pinfunction "VIC_P5") (pintype "input"))
    )
    (net (code "53") (name "D6_N") (class "Default")
      (node (ref "FMC_LPC") (pin "P$53") (pinfunction "LA08_N_P$53") (pintype "bidirectional"))
      (node (ref "U20") (pin "51") (pinfunction "B3Z_51") (pintype "output"))
    )
    (net (code "54") (name "D6_P") (class "Default")
      (node (ref "FMC_LPC") (pin "P$52") (pinfunction "LA08_P_P$52") (pintype "bidirectional"))
      (node (ref "U20") (pin "52") (pinfunction "B3Y_52") (pintype "output"))
    )
    (net (code "55") (name "D7_ISO") (class "Default")
      (node (ref "R36") (pin "1") (pinfunction "1_1") (pintype "passive"))
      (node (ref "U14") (pin "P6") (pinfunction "VID_P6") (pintype "input"))
    )
    (net (code "56") (name "D7_N") (class "Default")
      (node (ref "FMC_LPC") (pin "P$92") (pinfunction "LA05_N_P$92") (pintype "bidirectional"))
      (node (ref "U20") (pin "49") (pinfunction "B4Z_49") (pintype "output"))
    )
    (net (code "57") (name "D7_P") (class "Default")
      (node (ref "FMC_LPC") (pin "P$91") (pinfunction "LA05_P_P$91") (pintype "bidirectional"))
      (node (ref "U20") (pin "50") (pinfunction "B4Y_50") (pintype "output"))
    )
    (net (code "58") (name "D8_ISO") (class "Default")
      (node (ref "R43") (pin "1") (pinfunction "1_1") (pintype "passive"))
      (node (ref "U15") (pin "P3") (pinfunction "VIA_P3") (pintype "input"))
    )
    (net (code "59") (name "D8_N") (class "Default")
      (node (ref "FMC_LPC") (pin "P$11") (pinfunction "LA04_N_P$11") (pintype "bidirectional"))
      (node (ref "U20") (pin "47") (pinfunction "C1Z_47") (pintype "output"))
    )
    (net (code "60") (name "D8_P") (class "Default")
      (node (ref "FMC_LPC") (pin "P$10") (pinfunction "LA04_P_P$10") (pintype "bidirectional"))
      (node (ref "U20") (pin "48") (pinfunction "C1Y_48") (pintype "output"))
    )
    (net (code "61") (name "D9_ISO") (class "Default")
      (node (ref "R51") (pin "1") (pinfunction "1_1") (pintype "passive"))
      (node (ref "U15") (pin "P4") (pinfunction "VIB_P4") (pintype "input"))
    )
    (net (code "62") (name "D9_N") (class "Default")
      (node (ref "FMC_LPC") (pin "P$131") (pinfunction "LA06_N_P$131") (pintype "bidirectional"))
      (node (ref "U20") (pin "45") (pinfunction "C2Z_45") (pintype "output"))
    )
    (net (code "63") (name "D9_P") (class "Default")
      (node (ref "FMC_LPC") (pin "P$130") (pinfunction "LA06_P_P$130") (pintype "bidirectional"))
      (node (ref "U20") (pin "46") (pinfunction "C2Y_46") (pintype "output"))
    )
    (net (code "64") (name "D10_ISO") (class "Default")
      (node (ref "R35") (pin "1") (pinfunction "1_1") (pintype "passive"))
      (node (ref "U15") (pin "P5") (pinfunction "VIC_P5") (pintype "input"))
    )
    (net (code "65") (name "D10_N") (class "Default")
      (node (ref "FMC_LPC") (pin "P$50") (pinfunction "LA03_N_P$50") (pintype "bidirectional"))
      (node (ref "U20") (pin "43") (pinfunction "C3Z_43") (pintype "output"))
    )
    (net (code "66") (name "D10_P") (class "Default")
      (node (ref "FMC_LPC") (pin "P$49") (pinfunction "LA03_P_P$49") (pintype "bidirectional"))
      (node (ref "U20") (pin "44") (pinfunction "C3Y_44") (pintype "output"))
    )
    (net (code "67") (name "D11_ISO") (class "Default")
      (node (ref "R42") (pin "1") (pinfunction "1_1") (pintype "passive"))
      (node (ref "U15") (pin "P6") (pinfunction "VID_P6") (pintype "input"))
    )
    (net (code "68") (name "D11_N") (class "Default")
      (node (ref "FMC_LPC") (pin "P$8") (pinfunction "LA02_N_P$8") (pintype "bidirectional"))
      (node (ref "U20") (pin "41") (pinfunction "C4Z_41") (pintype "output"))
    )
    (net (code "69") (name "D11_P") (class "Default")
      (node (ref "FMC_LPC") (pin "P$7") (pinfunction "LA02_P_P$7") (pintype "bidirectional"))
      (node (ref "U20") (pin "42") (pinfunction "C4Y_42") (pintype "output"))
    )
    (net (code "70") (name "DAC_LAT") (class "Default")
      (node (ref "U19") (pin "32") (pinfunction "B1Y_32") (pintype "output"))
      (node (ref "U8") (pin "6") (pinfunction "LAT/HVC_6") (pintype "input"))
    )
    (net (code "71") (name "DAC_LAT_N") (class "Default")
      (node (ref "FMC_LPC") (pin "P$20") (pinfunction "LA15_N_P$20") (pintype "bidirectional"))
      (node (ref "U19") (pin "7") (pinfunction "B1B_7") (pintype "input"))
    )
    (net (code "72") (name "DAC_LAT_P") (class "Default")
      (node (ref "FMC_LPC") (pin "P$19") (pinfunction "LA15_P_P$19") (pintype "bidirectional"))
      (node (ref "U19") (pin "6") (pinfunction "B1A_6") (pintype "input"))
    )
    (net (code "73") (name "DI0") (class "Default")
      (node (ref "TP7") (pin "TP") (pinfunction "TP_TP") (pintype "bidirectional"))
      (node (ref "U21") (pin "2") (pinfunction "1A_2") (pintype "input"))
      (node (ref "U5") (pin "1") (pinfunction "OUT_1") (pintype "output"))
    )
    (net (code "74") (name "DI0_N") (class "Default")
      (node (ref "FMC_LPC") (pin "P$68") (pinfunction "LA25_N_P$68") (pintype "bidirectional"))
      (node (ref "U21") (pin "15") (pinfunction "1Z_15") (pintype "output"))
    )
    (net (code "75") (name "DI0_P") (class "Default")
      (node (ref "FMC_LPC") (pin "P$67") (pinfunction "LA25_P_P$67") (pintype "bidirectional"))
      (node (ref "U21") (pin "16") (pinfunction "1Y_16") (pintype "output"))
    )
    (net (code "76") (name "DI0_TERM") (class "Default")
      (node (ref "R73") (pin "1") (pinfunction "1_1") (pintype "passive"))
      (node (ref "R9") (pin "1") (pinfunction "1_1") (pintype "passive"))
      (node (ref "U19") (pin "35") (pinfunction "A1Y_35") (pintype "output"))
    )
    (net (code "77") (name "DI0_TERM_N") (class "Default")
      (node (ref "FMC_LPC") (pin "P$139") (pinfunction "LA1N_N_P$139") (pintype "bidirectional"))
      (node (ref "U19") (pin "2") (pinfunction "A1B_2") (pintype "input"))
    )
    (net (code "78") (name "DI0_TERM_P") (class "Default")
      (node (ref "FMC_LPC") (pin "P$138") (pinfunction "LA14_P_P$138") (pintype "bidirectional"))
      (node (ref "U19") (pin "1") (pinfunction "A1A_1") (pintype "input"))
    )
    (net (code "79") (name "DI1") (class "Default")
      (node (ref "TP6") (pin "TP") (pinfunction "TP_TP") (pintype "bidirectional"))
      (node (ref "U21") (pin "3") (pinfunction "2A_3") (pintype "input"))
      (node (ref "U6") (pin "1") (pinfunction "OUT_1") (pintype "output"))
    )
    (net (code "80") (name "DI1_N") (class "Default")
      (node (ref "FMC_LPC") (pin "P$29") (pinfunction "LA24_N_P$29") (pintype "bidirectional"))
      (node (ref "U21") (pin "13") (pinfunction "2Z_13") (pintype "output"))
    )
    (net (code "81") (name "DI1_P") (class "Default")
      (node (ref "FMC_LPC") (pin "P$28") (pinfunction "LA24_P_P$28") (pintype "bidirectional"))
      (node (ref "U21") (pin "14") (pinfunction "2Y_14") (pintype "output"))
    )
    (net (code "82") (name "DI1_TERM") (class "Default")
      (node (ref "R11") (pin "1") (pinfunction "1_1") (pintype "passive"))
      (node (ref "R74") (pin "1") (pinfunction "1_1") (pintype "passive"))
      (node (ref "U19") (pin "34") (pinfunction "A2Y_34") (pintype "output"))
    )
    (net (code "83") (name "DI1_TERM_N") (class "Default")
      (node (ref "FMC_LPC") (pin "P$59") (pinfunction "LA16_N_P$59") (pintype "bidirectional"))
      (node (ref "U19") (pin "4") (pinfunction "A2B_4") (pintype "input"))
    )
    (net (code "84") (name "DI1_TERM_P") (class "Default")
      (node (ref "FMC_LPC") (pin "P$58") (pinfunction "LA16_P_P$58") (pintype "bidirectional"))
      (node (ref "U19") (pin "3") (pinfunction "A2A_3") (pintype "input"))
    )
    (net (code "85") (name "DO0") (class "Default")
      (node (ref "U19") (pin "26") (pinfunction "C2Y_26") (pintype "output"))
      (node (ref "U4") (pin "2") (pinfunction "1A_2") (pintype "input"))
      (node (ref "U4") (pin "5") (pinfunction "2A_5") (pintype "input"))
    )
    (net (code "86") (name "DO0_N") (class "Default")
      (node (ref "FMC_LPC") (pin "P$143") (pinfunction "LA18_N_CC_P$143") (pintype "bidirectional"))
      (node (ref "U19") (pin "12") (pinfunction "C1B_12") (pintype "input"))
    )
    (net (code "87") (name "DO0_P") (class "Default")
      (node (ref "FMC_LPC") (pin "P$142") (pinfunction "LA18_P_CC_P$142") (pintype "bidirectional"))
      (node (ref "U19") (pin "11") (pinfunction "C1A_11") (pintype "input"))
    )
    (net (code "88") (name "DO1") (class "Default")
      (node (ref "U19") (pin "27") (pinfunction "C1Y_27") (pintype "output"))
      (node (ref "U4") (pin "12") (pinfunction "4A_12") (pintype "input"))
      (node (ref "U4") (pin "9") (pinfunction "3A_9") (pintype "input"))
    )
    (net (code "89") (name "DO1_N") (class "Default")
      (node (ref "FMC_LPC") (pin "P$62") (pinfunction "LA20_N_P$62") (pintype "bidirectional"))
      (node (ref "U19") (pin "14") (pinfunction "C2B_14") (pintype "input"))
    )
    (net (code "90") (name "DO1_P") (class "Default")
      (node (ref "FMC_LPC") (pin "P$61") (pinfunction "LA20_P_P$61") (pintype "bidirectional"))
      (node (ref "U19") (pin "13") (pinfunction "C2A_13") (pintype "input"))
    )
    (net (code "91") (name "DO_TEST") (class "Default")
      (node (ref "U19") (pin "31") (pinfunction "B2Y_31") (pintype "output"))
    )
    (net (code "92") (name "DO_TEST_N") (class "Default")
      (node (ref "FMC_LPC") (pin "P$101") (pinfunction "LA17_N_CC_P$101") (pintype "bidirectional"))
      (node (ref "U19") (pin "9") (pinfunction "B2B_9") (pintype "input"))
    )
    (net (code "93") (name "DO_TEST_P") (class "Default")
      (node (ref "FMC_LPC") (pin "P$100") (pinfunction "LA17_P_CC_P$100") (pintype "bidirectional"))
      (node (ref "U19") (pin "8") (pinfunction "B2A_8") (pintype "input"))
    )
    (net (code "94") (name "GND") (class "Default")
      (node (ref "C1") (pin "1") (pinfunction "1_1") (pintype "passive"))
      (node (ref "C2") (pin "1") (pinfunction "1_1") (pintype "passive"))
      (node (ref "C20") (pin "1") (pinfunction "1_1") (pintype "passive"))
      (node (ref "C25") (pin "1") (pinfunction "1_1") (pintype "passive"))
      (node (ref "C44") (pin "-") (pinfunction "-_-") (pintype "passive"))
      (node (ref "C46") (pin "-") (pinfunction "-_-") (pintype "passive"))
      (node (ref "C55") (pin "1") (pinfunction "1_1") (pintype "passive"))
      (node (ref "C56") (pin "1") (pinfunction "1_1") (pintype "passive"))
      (node (ref "C57") (pin "1") (pinfunction "1_1") (pintype "passive"))
      (node (ref "C58") (pin "1") (pinfunction "1_1") (pintype "passive"))
      (node (ref "C59") (pin "1") (pinfunction "1_1") (pintype "passive"))
      (node (ref "C6") (pin "2") (pinfunction "2_2") (pintype "passive"))
      (node (ref "C60") (pin "1") (pinfunction "1_1") (pintype "passive"))
      (node (ref "C61") (pin "1") (pinfunction "1_1") (pintype "passive"))
      (node (ref "C66") (pin "-") (pinfunction "-_-") (pintype "passive"))
      (node (ref "C7") (pin "2") (pinfunction "2_2") (pintype "passive"))
      (node (ref "C8") (pin "2") (pinfunction "2_2") (pintype "passive"))
      (node (ref "C80") (pin "1") (pinfunction "1_1") (pintype "passive"))
      (node (ref "C81") (pin "1") (pinfunction "1_1") (pintype "passive"))
      (node (ref "C82") (pin "1") (pinfunction "1_1") (pintype "passive"))
      (node (ref "C83") (pin "1") (pinfunction "1_1") (pintype "passive"))
      (node (ref "C84") (pin "1") (pinfunction "1_1") (pintype "passive"))
      (node (ref "C85") (pin "1") (pinfunction "1_1") (pintype "passive"))
      (node (ref "C86") (pin "1") (pinfunction "1_1") (pintype "passive"))
      (node (ref "C87") (pin "-") (pinfunction "-_-") (pintype "passive"))
      (node (ref "C88") (pin "1") (pinfunction "1_1") (pintype "passive"))
      (node (ref "C89") (pin "1") (pinfunction "1_1") (pintype "passive"))
      (node (ref "C9") (pin "2") (pinfunction "2_2") (pintype "passive"))
      (node (ref "C90") (pin "1") (pinfunction "1_1") (pintype "passive"))
      (node (ref "C91") (pin "1") (pinfunction "1_1") (pintype "passive"))
      (node (ref "C92") (pin "1") (pinfunction "1_1") (pintype "passive"))
      (node (ref "C93") (pin "1") (pinfunction "1_1") (pintype "passive"))
      (node (ref "C94") (pin "1") (pinfunction "1_1") (pintype "passive"))
      (node (ref "C95") (pin "1") (pinfunction "1_1") (pintype "passive"))
      (node (ref "C96") (pin "1") (pinfunction "1_1") (pintype "passive"))
      (node (ref "C97") (pin "1") (pinfunction "1_1") (pintype "passive"))
      (node (ref "C98") (pin "1") (pinfunction "1_1") (pintype "passive"))
      (node (ref "D1") (pin "1") (pinfunction "A_1") (pintype "passive"))
      (node (ref "D2") (pin "1") (pinfunction "A_1") (pintype "passive"))
      (node (ref "D3") (pin "1") (pinfunction "A_1") (pintype "passive"))
      (node (ref "D4") (pin "1") (pinfunction "A_1") (pintype "passive"))
      (node (ref "D5") (pin "2") (pinfunction "A_2") (pintype "passive"))
      (node (ref "D6") (pin "A") (pinfunction "A_A") (pintype "passive"))
      (node (ref "DI1") (pin "GND$1") (pinfunction "2_GND$1") (pintype "passive"))
      (node (ref "DI1") (pin "GND$2") (pinfunction "2_GND$2") (pintype "passive"))
      (node (ref "DI1") (pin "GND$3") (pinfunction "2_GND$3") (pintype "passive"))
      (node (ref "DI1") (pin "GND$4") (pinfunction "2_GND$4") (pintype "passive"))
      (node (ref "DI2") (pin "GND$1") (pinfunction "2_GND$1") (pintype "passive"))
      (node (ref "DI2") (pin "GND$2") (pinfunction "2_GND$2") (pintype "passive"))
      (node (ref "DI2") (pin "GND$3") (pinfunction "2_GND$3") (pintype "passive"))
      (node (ref "DI2") (pin "GND$4") (pinfunction "2_GND$4") (pintype "passive"))
      (node (ref "DO1") (pin "GND$1") (pinfunction "2_GND$1") (pintype "passive"))
      (node (ref "DO1") (pin "GND$2") (pinfunction "2_GND$2") (pintype "passive"))
      (node (ref "DO1") (pin "GND$3") (pinfunction "2_GND$3") (pintype "passive"))
      (node (ref "DO1") (pin "GND$4") (pinfunction "2_GND$4") (pintype "passive"))
      (node (ref "DO2") (pin "GND$1") (pinfunction "2_GND$1") (pintype "passive"))
      (node (ref "DO2") (pin "GND$2") (pinfunction "2_GND$2") (pintype "passive"))
      (node (ref "DO2") (pin "GND$3") (pinfunction "2_GND$3") (pintype "passive"))
      (node (ref "DO2") (pin "GND$4") (pinfunction "2_GND$4") (pintype "passive"))
      (node (ref "FMC_LPC") (pin "P$102") (pinfunction "GND_P$102") (pintype "power_in"))
      (node (ref "FMC_LPC") (pin "P$105") (pinfunction "GND_P$105") (pintype "power_in"))
      (node (ref "FMC_LPC") (pin "P$108") (pinfunction "GND_P$108") (pintype "power_in"))
      (node (ref "FMC_LPC") (pin "P$117") (pinfunction "GND_P$117") (pintype "power_in"))
      (node (ref "FMC_LPC") (pin "P$119") (pinfunction "GND_P$119") (pintype "power_in"))
      (node (ref "FMC_LPC") (pin "P$12") (pinfunction "GND_P$12") (pintype "power_in"))
      (node (ref "FMC_LPC") (pin "P$121") (pinfunction "GND_P$121") (pintype "power_in"))
      (node (ref "FMC_LPC") (pin "P$124") (pinfunction "GND_P$124") (pintype "power_in"))
      (node (ref "FMC_LPC") (pin "P$125") (pinfunction "GND_P$125") (pintype "power_in"))
      (node (ref "FMC_LPC") (pin "P$128") (pinfunction "GND_P$128") (pintype "power_in"))
      (node (ref "FMC_LPC") (pin "P$129") (pinfunction "GND_P$129") (pintype "power_in"))
      (node (ref "FMC_LPC") (pin "P$132") (pinfunction "GND_P$132") (pintype "power_in"))
      (node (ref "FMC_LPC") (pin "P$133") (pinfunction "GND_P$133") (pintype "power_in"))
      (node (ref "FMC_LPC") (pin "P$136") (pinfunction "GND_P$136") (pintype "power_in"))
      (node (ref "FMC_LPC") (pin "P$137") (pinfunction "GND_P$137") (pintype "power_in"))
      (node (ref "FMC_LPC") (pin "P$140") (pinfunction "GND_P$140") (pintype "power_in"))
      (node (ref "FMC_LPC") (pin "P$141") (pinfunction "GND_P$141") (pintype "power_in"))
      (node (ref "FMC_LPC") (pin "P$144") (pinfunction "GND_P$144") (pintype "power_in"))
      (node (ref "FMC_LPC") (pin "P$145") (pinfunction "GND_P$145") (pintype "power_in"))
      (node (ref "FMC_LPC") (pin "P$148") (pinfunction "GND_P$148") (pintype "power_in"))
      (node (ref "FMC_LPC") (pin "P$149") (pinfunction "GND_P$149") (pintype "power_in"))
      (node (ref "FMC_LPC") (pin "P$15") (pinfunction "GND_P$15") (pintype "power_in"))
      (node (ref "FMC_LPC") (pin "P$152") (pinfunction "GND_P$152") (pintype "power_in"))
      (node (ref "FMC_LPC") (pin "P$153") (pinfunction "GND_P$153") (pintype "power_in"))
      (node (ref "FMC_LPC") (pin "P$156") (pinfunction "GND_P$156") (pintype "power_in"))
      (node (ref "FMC_LPC") (pin "P$158") (pinfunction "GND19_P$158") (pintype "bidirectional"))
      (node (ref "FMC_LPC") (pin "P$160") (pinfunction "GND_P$160") (pintype "power_in"))
      (node (ref "FMC_LPC") (pin "P$18") (pinfunction "GND_P$18") (pintype "power_in"))
      (node (ref "FMC_LPC") (pin "P$21") (pinfunction "GND_P$21") (pintype "power_in"))
      (node (ref "FMC_LPC") (pin "P$24") (pinfunction "GND_P$24") (pintype "power_in"))
      (node (ref "FMC_LPC") (pin "P$27") (pinfunction "GND_P$27") (pintype "power_in"))
      (node (ref "FMC_LPC") (pin "P$3") (pinfunction "GND_P$3") (pintype "power_in"))
      (node (ref "FMC_LPC") (pin "P$30") (pinfunction "GND_P$30") (pintype "power_in"))
      (node (ref "FMC_LPC") (pin "P$33") (pinfunction "GND_P$33") (pintype "power_in"))
      (node (ref "FMC_LPC") (pin "P$36") (pinfunction "GND_P$36") (pintype "power_in"))
      (node (ref "FMC_LPC") (pin "P$39") (pinfunction "GND_P$39") (pintype "power_in"))
      (node (ref "FMC_LPC") (pin "P$41") (pinfunction "GND_P$41") (pintype "power_in"))
      (node (ref "FMC_LPC") (pin "P$44") (pinfunction "GND_P$44") (pintype "power_in"))
      (node (ref "FMC_LPC") (pin "P$45") (pinfunction "GND_P$45") (pintype "power_in"))
      (node (ref "FMC_LPC") (pin "P$48") (pinfunction "GND_P$48") (pintype "power_in"))
      (node (ref "FMC_LPC") (pin "P$51") (pinfunction "GND_P$51") (pintype "power_in"))
      (node (ref "FMC_LPC") (pin "P$54") (pinfunction "GND_P$54") (pintype "power_in"))
      (node (ref "FMC_LPC") (pin "P$57") (pinfunction "GND_P$57") (pintype "power_in"))
      (node (ref "FMC_LPC") (pin "P$6") (pinfunction "GND_P$6") (pintype "power_in"))
      (node (ref "FMC_LPC") (pin "P$60") (pinfunction "GND_P$60") (pintype "power_in"))
      (node (ref "FMC_LPC") (pin "P$63") (pinfunction "GND42_P$63") (pintype "bidirectional"))
      (node (ref "FMC_LPC") (pin "P$66") (pinfunction "GND_P$66") (pintype "power_in"))
      (node (ref "FMC_LPC") (pin "P$69") (pinfunction "GND_P$69") (pintype "power_in"))
      (node (ref "FMC_LPC") (pin "P$72") (pinfunction "GND_P$72") (pintype "power_in"))
      (node (ref "FMC_LPC") (pin "P$75") (pinfunction "GND_P$75") (pintype "power_in"))
      (node (ref "FMC_LPC") (pin "P$78") (pinfunction "GND_P$78") (pintype "power_in"))
      (node (ref "FMC_LPC") (pin "P$80") (pinfunction "GND_P$80") (pintype "power_in"))
      (node (ref "FMC_LPC") (pin "P$82") (pinfunction "GND_P$82") (pintype "power_in"))
      (node (ref "FMC_LPC") (pin "P$83") (pinfunction "GND_P$83") (pintype "power_in"))
      (node (ref "FMC_LPC") (pin "P$86") (pinfunction "GND_P$86") (pintype "power_in"))
      (node (ref "FMC_LPC") (pin "P$87") (pinfunction "GND_P$87") (pintype "power_in"))
      (node (ref "FMC_LPC") (pin "P$9") (pinfunction "GND_P$9") (pintype "power_in"))
      (node (ref "FMC_LPC") (pin "P$90") (pinfunction "GND_P$90") (pintype "power_in"))
      (node (ref "FMC_LPC") (pin "P$93") (pinfunction "GND_P$93") (pintype "power_in"))
      (node (ref "FMC_LPC") (pin "P$96") (pinfunction "GND_P$96") (pintype "power_in"))
      (node (ref "FMC_LPC") (pin "P$99") (pinfunction "GND_P$99") (pintype "power_in"))
      (node (ref "PCIE-PWR") (pin "4") (pinfunction "4_4") (pintype "passive"))
      (node (ref "PCIE-PWR") (pin "5") (pinfunction "5_5") (pintype "passive"))
      (node (ref "PCIE-PWR") (pin "6") (pinfunction "6_6") (pintype "passive"))
      (node (ref "Q1") (pin "S") (pinfunction "S_S") (pintype "bidirectional"))
      (node (ref "Q2") (pin "S") (pinfunction "S_S") (pintype "bidirectional"))
      (node (ref "Q3") (pin "S") (pinfunction "S_S") (pintype "bidirectional"))
      (node (ref "Q4") (pin "S") (pinfunction "S_S") (pintype "bidirectional"))
      (node (ref "R10") (pin "1") (pinfunction "1_1") (pintype "passive"))
      (node (ref "R3") (pin "1") (pinfunction "1_1") (pintype "passive"))
      (node (ref "R4") (pin "1") (pinfunction "1_1") (pintype "passive"))
      (node (ref "R5") (pin "1") (pinfunction "1_1") (pintype "passive"))
      (node (ref "R6") (pin "1") (pinfunction "1_1") (pintype "passive"))
      (node (ref "R8") (pin "1") (pinfunction "1_1") (pintype "passive"))
      (node (ref "TERM") (pin "C1") (pinfunction "C_C1") (pintype "passive"))
      (node (ref "TERM") (pin "C2") (pinfunction "C_C2") (pintype "passive"))
      (node (ref "TP10") (pin "1") (pinfunction "TP_1") (pintype "bidirectional"))
      (node (ref "TP14") (pin "1") (pinfunction "TP_1") (pintype "bidirectional"))
      (node (ref "TP15") (pin "1") (pinfunction "TP_1") (pintype "bidirectional"))
      (node (ref "TP16") (pin "1") (pinfunction "TP_1") (pintype "bidirectional"))
      (node (ref "TP17") (pin "1") (pinfunction "TP_1") (pintype "bidirectional"))
      (node (ref "TP21") (pin "1") (pinfunction "TP_1") (pintype "bidirectional"))
      (node (ref "TP23") (pin "1") (pinfunction "TP_1") (pintype "bidirectional"))
      (node (ref "TP8") (pin "1") (pinfunction "TP_1") (pintype "bidirectional"))
      (node (ref "U11") (pin "4") (pinfunction "GND1_4") (pintype "power_in"))
      (node (ref "U12") (pin "2") (pinfunction "GND_2") (pintype "power_in"))
      (node (ref "U13") (pin "P15") (pinfunction "GND2_P15") (pintype "power_in"))
      (node (ref "U13") (pin "P9") (pinfunction "GND2_P9") (pintype "power_in"))
      (node (ref "U14") (pin "P15") (pinfunction "GND2_P15") (pintype "power_in"))
      (node (ref "U14") (pin "P9") (pinfunction "GND2_P9") (pintype "power_in"))
      (node (ref "U15") (pin "P15") (pinfunction "GND2_P15") (pintype "power_in"))
      (node (ref "U15") (pin "P9") (pinfunction "GND2_P9") (pintype "power_in"))
      (node (ref "U16") (pin "P15") (pinfunction "GND2_P15") (pintype "power_in"))
      (node (ref "U16") (pin "P9") (pinfunction "GND2_P9") (pintype "power_in"))
      (node (ref "U17") (pin "P15") (pinfunction "GND2_P15") (pintype "power_in"))
      (node (ref "U17") (pin "P9") (pinfunction "GND2_P9") (pintype "power_in"))
      (node (ref "U18") (pin "1") (pinfunction "1_1") (pintype "bidirectional"))
      (node (ref "U18") (pin "4") (pinfunction "4_4") (pintype "bidirectional"))
      (node (ref "U19") (pin "10") (pinfunction "AGND_10") (pintype "power_in"))
      (node (ref "U19") (pin "15") (pinfunction "AGND_15") (pintype "power_in"))
      (node (ref "U19") (pin "20") (pinfunction "GND_20") (pintype "power_in"))
      (node (ref "U19") (pin "28") (pinfunction "DGND_28") (pintype "power_in"))
      (node (ref "U19") (pin "30") (pinfunction "DGND_30") (pintype "power_in"))
      (node (ref "U19") (pin "38") (pinfunction "GND_38") (pintype "power_in"))
      (node (ref "U19") (pin "5") (pinfunction "AGND_5") (pintype "power_in"))
      (node (ref "U20") (pin "1") (pinfunction "GND_1") (pintype "power_in"))
      (node (ref "U20") (pin "15") (pinfunction "GND_15") (pintype "power_in"))
      (node (ref "U20") (pin "18") (pinfunction "GND_18") (pintype "power_in"))
      (node (ref "U20") (pin "29") (pinfunction "GND_29") (pintype "power_in"))
      (node (ref "U20") (pin "32") (pinfunction "GND_32") (pintype "power_in"))
      (node (ref "U20") (pin "4") (pinfunction "GND_4") (pintype "power_in"))
      (node (ref "U21") (pin "5") (pinfunction "GND_5") (pintype "power_in"))
      (node (ref "U4") (pin "7") (pinfunction "GND_7") (pintype "passive"))
      (node (ref "U5") (pin "2") (pinfunction "V-_2") (pintype "power_in"))
      (node (ref "U6") (pin "2") (pinfunction "V-_2") (pintype "power_in"))
      (node (ref "U8") (pin "5") (pinfunction "AVSS_5") (pintype "power_in"))
    )
    (net (code "95") (name "GND_ISO") (class "Default")
      (node (ref "C10") (pin "1") (pinfunction "1_1") (pintype "passive"))
      (node (ref "C11") (pin "1") (pinfunction "1_1") (pintype "passive"))
      (node (ref "C13") (pin "1") (pinfunction "1_1") (pintype "passive"))
      (node (ref "C14") (pin "1") (pinfunction "1_1") (pintype "passive"))
      (node (ref "C15") (pin "1") (pinfunction "1_1") (pintype "passive"))
      (node (ref "C17") (pin "2") (pinfunction "2_2") (pintype "passive"))
      (node (ref "C18") (pin "1") (pinfunction "1_1") (pintype "passive"))
      (node (ref "C19") (pin "1") (pinfunction "1_1") (pintype "passive"))
      (node (ref "C21") (pin "1") (pinfunction "1_1") (pintype "passive"))
      (node (ref "C22") (pin "1") (pinfunction "1_1") (pintype "passive"))
      (node (ref "C23") (pin "1") (pinfunction "1_1") (pintype "passive"))
      (node (ref "C24") (pin "1") (pinfunction "1_1") (pintype "passive"))
      (node (ref "C26") (pin "1") (pinfunction "1_1") (pintype "passive"))
      (node (ref "C27") (pin "1") (pinfunction "1_1") (pintype "passive"))
      (node (ref "C28") (pin "1") (pinfunction "1_1") (pintype "passive"))
      (node (ref "C29") (pin "1") (pinfunction "1_1") (pintype "passive"))
      (node (ref "C3") (pin "1") (pinfunction "1_1") (pintype "passive"))
      (node (ref "C30") (pin "1") (pinfunction "1_1") (pintype "passive"))
      (node (ref "C31") (pin "1") (pinfunction "1_1") (pintype "passive"))
      (node (ref "C32") (pin "1") (pinfunction "1_1") (pintype "passive"))
      (node (ref "C33") (pin "1") (pinfunction "1_1") (pintype "passive"))
      (node (ref "C34") (pin "1") (pinfunction "1_1") (pintype "passive"))
      (node (ref "C35") (pin "1") (pinfunction "1_1") (pintype "passive"))
      (node (ref "C36") (pin "1") (pinfunction "1_1") (pintype "passive"))
      (node (ref "C37") (pin "1") (pinfunction "1_1") (pintype "passive"))
      (node (ref "C38") (pin "1") (pinfunction "1_1") (pintype "passive"))
      (node (ref "C39") (pin "1") (pinfunction "1_1") (pintype "passive"))
      (node (ref "C4") (pin "1") (pinfunction "1_1") (pintype "passive"))
      (node (ref "C40") (pin "1") (pinfunction "1_1") (pintype "passive"))
      (node (ref "C42") (pin "1") (pinfunction "1_1") (pintype "passive"))
      (node (ref "C45") (pin "1") (pinfunction "1_1") (pintype "passive"))
      (node (ref "C47") (pin "-") (pinfunction "-_-") (pintype "passive"))
      (node (ref "C48") (pin "-") (pinfunction "-_-") (pintype "passive"))
      (node (ref "C49") (pin "1") (pinfunction "1_1") (pintype "passive"))
      (node (ref "C5") (pin "2") (pinfunction "2_2") (pintype "passive"))
      (node (ref "C50") (pin "1") (pinfunction "1_1") (pintype "passive"))
      (node (ref "C51") (pin "1") (pinfunction "1_1") (pintype "passive"))
      (node (ref "C52") (pin "1") (pinfunction "1_1") (pintype "passive"))
      (node (ref "C53") (pin "1") (pinfunction "1_1") (pintype "passive"))
      (node (ref "C54") (pin "1") (pinfunction "1_1") (pintype "passive"))
      (node (ref "LINK") (pin "GND$1") (pinfunction "2_GND$1") (pintype "passive"))
      (node (ref "LINK") (pin "GND$2") (pinfunction "2_GND$2") (pintype "passive"))
      (node (ref "LINK") (pin "GND$3") (pinfunction "2_GND$3") (pintype "passive"))
      (node (ref "LINK") (pin "GND$4") (pinfunction "2_GND$4") (pintype "passive"))
      (node (ref "PWR/LOCK") (pin "C1") (pinfunction "C_C1") (pintype "passive"))
      (node (ref "Q5") (pin "S") (pinfunction "S_S") (pintype "bidirectional"))
      (node (ref "R30") (pin "2") (pinfunction "2_2") (pintype "passive"))
      (node (ref "R34") (pin "1") (pinfunction "1_1") (pintype "passive"))
      (node (ref "R55") (pin "2") (pinfunction "2_2") (pintype "passive"))
      (node (ref "R58") (pin "2") (pinfunction "2_2") (pintype "passive"))
      (node (ref "R59") (pin "2") (pinfunction "2_2") (pintype "passive"))
      (node (ref "R61") (pin "2") (pinfunction "2_2") (pintype "passive"))
      (node (ref "R63") (pin "2") (pinfunction "2_2") (pintype "passive"))
      (node (ref "R64") (pin "2") (pinfunction "2_2") (pintype "passive"))
      (node (ref "R68") (pin "2") (pinfunction "2_2") (pintype "passive"))
      (node (ref "TP1") (pin "1") (pinfunction "TP_1") (pintype "bidirectional"))
      (node (ref "TP18") (pin "1") (pinfunction "TP_1") (pintype "bidirectional"))
      (node (ref "TP19") (pin "1") (pinfunction "TP_1") (pintype "bidirectional"))
      (node (ref "TP20") (pin "1") (pinfunction "TP_1") (pintype "bidirectional"))
      (node (ref "TP28") (pin "1") (pinfunction "TP_1") (pintype "bidirectional"))
      (node (ref "U1") (pin "1") (pinfunction "1_1") (pintype "bidirectional"))
      (node (ref "U1") (pin "4") (pinfunction "4_4") (pintype "bidirectional"))
      (node (ref "U10") (pin "B5") (pinfunction "GND_B5") (pintype "power_in"))
      (node (ref "U10") (pin "C1") (pinfunction "GND_C1") (pintype "power_in"))
      (node (ref "U10") (pin "C2") (pinfunction "GND_C2") (pintype "power_in"))
      (node (ref "U10") (pin "C5") (pinfunction "SYNC/MODE_C5") (pintype "input"))
      (node (ref "U10") (pin "D5") (pinfunction "GND_D5") (pintype "power_in"))
      (node (ref "U11") (pin "5") (pinfunction "GND2_5") (pintype "power_in"))
      (node (ref "U12") (pin "5") (pinfunction "-VO_5") (pintype "power_in"))
      (node (ref "U13") (pin "P2") (pinfunction "GND1_P2") (pintype "power_in"))
      (node (ref "U13") (pin "P8") (pinfunction "GND1_P8") (pintype "power_in"))
      (node (ref "U14") (pin "P2") (pinfunction "GND1_P2") (pintype "power_in"))
      (node (ref "U14") (pin "P8") (pinfunction "GND1_P8") (pintype "power_in"))
      (node (ref "U15") (pin "P2") (pinfunction "GND1_P2") (pintype "power_in"))
      (node (ref "U15") (pin "P8") (pinfunction "GND1_P8") (pintype "power_in"))
      (node (ref "U16") (pin "P2") (pinfunction "GND1_P2") (pintype "power_in"))
      (node (ref "U16") (pin "P8") (pinfunction "GND1_P8") (pintype "power_in"))
      (node (ref "U17") (pin "P2") (pinfunction "GND1_P2") (pintype "power_in"))
      (node (ref "U17") (pin "P8") (pinfunction "GND1_P8") (pintype "power_in"))
      (node (ref "U7") (pin "5") (pinfunction "5_5") (pintype "passive"))
      (node (ref "U7") (pin "6") (pinfunction "6_6") (pintype "passive"))
      (node (ref "U7") (pin "7") (pinfunction "7_7") (pintype "passive"))
      (node (ref "U7") (pin "8") (pinfunction "8_8") (pintype "passive"))
      (node (ref "U9") (pin "43") (pinfunction "RES_43") (pintype "input"))
      (node (ref "U9") (pin "44") (pinfunction "TESTEN_44") (pintype "input"))
      (node (ref "U9") (pin "49") (pinfunction "DAP_49") (pintype "input"))
    )
    (net (code "96") (name "GPI0") (class "Default")
      (node (ref "U17") (pin "P13") (pinfunction "VOB_P13") (pintype "output"))
      (node (ref "U21") (pin "7") (pinfunction "4A_7") (pintype "input"))
    )
    (net (code "97") (name "GPI0_ISO") (class "Default")
      (node (ref "R40") (pin "1") (pinfunction "1_1") (pintype "passive"))
      (node (ref "U17") (pin "P4") (pinfunction "VIB_P4") (pintype "input"))
    )
    (net (code "98") (name "GPI0_N") (class "Default")
      (node (ref "FMC_LPC") (pin "P$26") (pinfunction "LA21_N_P$26") (pintype "bidirectional"))
      (node (ref "U21") (pin "9") (pinfunction "4Z_9") (pintype "output"))
    )
    (net (code "99") (name "GPI0_P") (class "Default")
      (node (ref "FMC_LPC") (pin "P$25") (pinfunction "LA21_P_P$25") (pintype "bidirectional"))
      (node (ref "U21") (pin "10") (pinfunction "4Y_10") (pintype "output"))
    )
    (net (code "100") (name "GPI1") (class "Default")
      (node (ref "U17") (pin "P14") (pinfunction "VOA_P14") (pintype "output"))
      (node (ref "U21") (pin "6") (pinfunction "3A_6") (pintype "input"))
    )
    (net (code "101") (name "GPI1_ISO") (class "Default")
      (node (ref "R48") (pin "1") (pinfunction "1_1") (pintype "passive"))
      (node (ref "U17") (pin "P3") (pinfunction "VIA_P3") (pintype "input"))
    )
    (net (code "102") (name "GPI1_N") (class "Default")
      (node (ref "FMC_LPC") (pin "P$104") (pinfunction "LA23_N_P$104") (pintype "bidirectional"))
      (node (ref "U21") (pin "11") (pinfunction "3Z_11") (pintype "output"))
    )
    (net (code "103") (name "GPI1_P") (class "Default")
      (node (ref "FMC_LPC") (pin "P$103") (pinfunction "LA23_P_P$103") (pintype "bidirectional"))
      (node (ref "U21") (pin "12") (pinfunction "3Y_12") (pintype "output"))
    )
    (net (code "104") (name "GPO0") (class "Default")
      (node (ref "U17") (pin "P11") (pinfunction "VID_P11") (pintype "input"))
      (node (ref "U19") (pin "24") (pinfunction "D1Y_24") (pintype "output"))
    )
    (net (code "105") (name "GPO0_N") (class "Default")
      (node (ref "FMC_LPC") (pin "P$23") (pinfunction "LA19_N_P$23") (pintype "bidirectional"))
      (node (ref "U19") (pin "17") (pinfunction "D1B_17") (pintype "input"))
    )
    (net (code "106") (name "GPO0_P") (class "Default")
      (node (ref "FMC_LPC") (pin "P$22") (pinfunction "LA19_P_P$22") (pintype "bidirectional"))
      (node (ref "U19") (pin "16") (pinfunction "D1A_16") (pintype "input"))
    )
    (net (code "107") (name "GPO1") (class "Default")
      (node (ref "U17") (pin "P12") (pinfunction "VIC_P12") (pintype "input"))
      (node (ref "U19") (pin "23") (pinfunction "D2Y_23") (pintype "output"))
    )
    (net (code "108") (name "GPO1_ISO") (class "Default")
      (node (ref "R47") (pin "1") (pinfunction "1_1") (pintype "passive"))
      (node (ref "U17") (pin "P5") (pinfunction "VOC_P5") (pintype "output"))
    )
    (net (code "109") (name "GPO1_N") (class "Default")
      (node (ref "FMC_LPC") (pin "P$65") (pinfunction "LA22_N_P$65") (pintype "bidirectional"))
      (node (ref "U19") (pin "19") (pinfunction "D2B_19") (pintype "input"))
    )
    (net (code "110") (name "GPO1_P") (class "Default")
      (node (ref "FMC_LPC") (pin "P$64") (pinfunction "LA22_P_P$64") (pintype "bidirectional"))
      (node (ref "U19") (pin "18") (pinfunction "D2A_18") (pintype "input"))
    )
    (net (code "111") (name "HSYNC_ISO") (class "Default")
      (node (ref "R50") (pin "1") (pinfunction "1_1") (pintype "passive"))
      (node (ref "U16") (pin "P3") (pinfunction "VIA_P3") (pintype "input"))
    )
    (net (code "112") (name "HSYNC_N") (class "Default")
      (node (ref "FMC_LPC") (pin "P$85") (pinfunction "GBTCLK0_M2C_N_P$85") (pintype "bidirectional"))
      (node (ref "U20") (pin "39") (pinfunction "D1Z_39") (pintype "output"))
    )
    (net (code "113") (name "HSYNC_P") (class "Default")
      (node (ref "FMC_LPC") (pin "P$84") (pinfunction "GBTCLK0_M2C_P_P$84") (pintype "bidirectional"))
      (node (ref "U20") (pin "40") (pinfunction "D1Y_40") (pintype "output"))
    )
    (net (code "114") (name "IDX0") (class "Default")
      (node (ref "R57") (pin "2") (pinfunction "2_2") (pintype "passive"))
      (node (ref "R58") (pin "1") (pinfunction "1_1") (pintype "passive"))
      (node (ref "U9") (pin "35") (pinfunction "IDX0_35") (pintype "input"))
    )
    (net (code "115") (name "IDX1") (class "Default")
      (node (ref "R60") (pin "2") (pinfunction "2_2") (pintype "passive"))
      (node (ref "R61") (pin "1") (pinfunction "1_1") (pintype "passive"))
      (node (ref "U9") (pin "34") (pinfunction "IDX1_34") (pintype "input"))
    )
    (net (code "116") (name "INTVCC") (class "Default")
      (node (ref "R56") (pin "1") (pinfunction "1_1") (pintype "passive"))
      (node (ref "U10") (pin "C3") (pinfunction "INTVCC_C3") (pintype "power_in"))
    )
    (net (code "117") (name "MODE") (class "Default")
      (node (ref "R62") (pin "2") (pinfunction "2_2") (pintype "passive"))
      (node (ref "R63") (pin "1") (pinfunction "1_1") (pintype "passive"))
      (node (ref "U9") (pin "37") (pinfunction "MODE_37") (pintype "input"))
    )
    (net (code "118") (name "Net-(C3-Pad2)") (class "Default")
      (node (ref "C3") (pin "2") (pinfunction "2_2") (pintype "passive"))
      (node (ref "C5") (pin "1") (pinfunction "1_1") (pintype "passive"))
      (node (ref "L2") (pin "1") (pinfunction "1_1") (pintype "passive"))
      (node (ref "L3") (pin "2") (pinfunction "2_2") (pintype "passive"))
      (node (ref "R20") (pin "1") (pinfunction "1_1") (pintype "passive"))
    )
    (net (code "119") (name "Net-(C12-Pad2)") (class "Default")
      (node (ref "C12") (pin "2") (pinfunction "2_2") (pintype "passive"))
      (node (ref "R30") (pin "1") (pinfunction "1_1") (pintype "passive"))
    )
    (net (code "120") (name "Net-(D1-COMM)") (class "Default")
      (node (ref "D1") (pin "3") (pinfunction "COMM_3") (pintype "passive"))
      (node (ref "F3") (pin "2") (pinfunction "2_2") (pintype "passive"))
      (node (ref "R13") (pin "2") (pinfunction "2_2") (pintype "passive"))
      (node (ref "U4") (pin "3") (pinfunction "1Y_3") (pintype "input"))
      (node (ref "U4") (pin "6") (pinfunction "2Y_6") (pintype "input"))
    )
    (net (code "121") (name "Net-(D2-COMM)") (class "Default")
      (node (ref "D2") (pin "3") (pinfunction "COMM_3") (pintype "passive"))
      (node (ref "F4") (pin "2") (pinfunction "2_2") (pintype "passive"))
      (node (ref "R12") (pin "2") (pinfunction "2_2") (pintype "passive"))
      (node (ref "U4") (pin "11") (pinfunction "4Y_11") (pintype "passive"))
      (node (ref "U4") (pin "8") (pinfunction "3Y_8") (pintype "input"))
    )
    (net (code "122") (name "Net-(D3-COMM)") (class "Default")
      (node (ref "D3") (pin "3") (pinfunction "COMM_3") (pintype "passive"))
      (node (ref "F1") (pin "2") (pinfunction "2_2") (pintype "passive"))
      (node (ref "R16") (pin "2") (pinfunction "2_2") (pintype "passive"))
      (node (ref "R21") (pin "2") (pinfunction "2_2") (pintype "passive"))
      (node (ref "R23") (pin "2") (pinfunction "2_2") (pintype "passive"))
      (node (ref "R28") (pin "1") (pinfunction "1_1") (pintype "passive"))
      (node (ref "R5") (pin "2") (pinfunction "2_2") (pintype "passive"))
    )
    (net (code "123") (name "Net-(D4-COMM)") (class "Default")
      (node (ref "D4") (pin "3") (pinfunction "COMM_3") (pintype "passive"))
      (node (ref "F2") (pin "2") (pinfunction "2_2") (pintype "passive"))
      (node (ref "R17") (pin "2") (pinfunction "2_2") (pintype "passive"))
      (node (ref "R22") (pin "2") (pinfunction "2_2") (pintype "passive"))
      (node (ref "R24") (pin "2") (pinfunction "2_2") (pintype "passive"))
      (node (ref "R29") (pin "1") (pinfunction "1_1") (pintype "passive"))
      (node (ref "R6") (pin "2") (pinfunction "2_2") (pintype "passive"))
    )
    (net (code "124") (name "Net-(DI1-1)") (class "Default")
      (node (ref "DI1") (pin "CLK") (pinfunction "1_CLK") (pintype "passive"))
      (node (ref "F1") (pin "1") (pinfunction "1_1") (pintype "passive"))
    )
    (net (code "125") (name "Net-(DI2-1)") (class "Default")
      (node (ref "DI2") (pin "CLK") (pinfunction "1_CLK") (pintype "passive"))
      (node (ref "F2") (pin "1") (pinfunction "1_1") (pintype "passive"))
    )
    (net (code "126") (name "Net-(DO1-1)") (class "Default")
      (node (ref "DO1") (pin "CLK") (pinfunction "1_CLK") (pintype "passive"))
      (node (ref "F3") (pin "1") (pinfunction "1_1") (pintype "passive"))
    )
    (net (code "127") (name "Net-(DO2-1)") (class "Default")
      (node (ref "DO2") (pin "CLK") (pinfunction "1_CLK") (pintype "passive"))
      (node (ref "F4") (pin "1") (pinfunction "1_1") (pintype "passive"))
    )
    (net (code "128") (name "Net-(L1-Pad1)") (class "Default")
      (node (ref "L1") (pin "1") (pinfunction "1_1") (pintype "passive"))
      (node (ref "L2") (pin "2") (pinfunction "2_2") (pintype "passive"))
      (node (ref "R20") (pin "2") (pinfunction "2_2") (pintype "passive"))
      (node (ref "R7") (pin "1") (pinfunction "1_1") (pintype "passive"))
    )
    (net (code "129") (name "Net-(OUTA-A)") (class "Default")
      (node (ref "OUT") (pin "A1") (pinfunction "A_A1") (pintype "passive"))
      (node (ref "R1") (pin "1") (pinfunction "1_1") (pintype "passive"))
    )
    (net (code "130") (name "Net-(OUTA-C)") (class "Default")
      (node (ref "OUT") (pin "C1") (pinfunction "C_C1") (pintype "passive"))
      (node (ref "Q1") (pin "D") (pinfunction "D_D") (pintype "bidirectional"))
    )
    (net (code "131") (name "Net-(OUTB-A)") (class "Default")
      (node (ref "OUT") (pin "A2") (pinfunction "A_A2") (pintype "passive"))
      (node (ref "R2") (pin "1") (pinfunction "1_1") (pintype "passive"))
    )
    (net (code "132") (name "Net-(OUTB-C)") (class "Default")
      (node (ref "OUT") (pin "C2") (pinfunction "C_C2") (pintype "passive"))
      (node (ref "Q2") (pin "D") (pinfunction "D_D") (pintype "bidirectional"))
    )
    (net (code "133") (name "Net-(PWR/LOCKA-A)") (class "Default")
      (node (ref "PWR/LOCK") (pin "A1") (pinfunction "A_A1") (pintype "passive"))
      (node (ref "R75") (pin "1") (pinfunction "1_1") (pintype "passive"))
    )
    (net (code "134") (name "Net-(PWR/LOCKB-A)") (class "Default")
      (node (ref "PWR/LOCK") (pin "A2") (pinfunction "A_A2") (pintype "passive"))
      (node (ref "R46") (pin "1") (pinfunction "1_1") (pintype "passive"))
    )
    (net (code "135") (name "Net-(PWR/LOCKB-C)") (class "Default")
      (node (ref "PWR/LOCK") (pin "C2") (pinfunction "C_C2") (pintype "passive"))
      (node (ref "Q5") (pin "D") (pinfunction "D_D") (pintype "bidirectional"))
    )
    (net (code "136") (name "Net-(Q1-PadG)") (class "Default")
      (node (ref "Q1") (pin "G") (pinfunction "G_G") (pintype "bidirectional"))
      (node (ref "R13") (pin "1") (pinfunction "1_1") (pintype "passive"))
      (node (ref "R3") (pin "2") (pinfunction "2_2") (pintype "passive"))
    )
    (net (code "137") (name "Net-(Q2-PadG)") (class "Default")
      (node (ref "Q2") (pin "G") (pinfunction "G_G") (pintype "bidirectional"))
      (node (ref "R12") (pin "1") (pinfunction "1_1") (pintype "passive"))
      (node (ref "R4") (pin "2") (pinfunction "2_2") (pintype "passive"))
    )
    (net (code "138") (name "Net-(Q3-PadD)") (class "Default")
      (node (ref "Q3") (pin "D") (pinfunction "D_D") (pintype "bidirectional"))
      (node (ref "R16") (pin "1") (pinfunction "1_1") (pintype "passive"))
      (node (ref "R21") (pin "1") (pinfunction "1_1") (pintype "passive"))
      (node (ref "R23") (pin "1") (pinfunction "1_1") (pintype "passive"))
    )
    (net (code "139") (name "Net-(Q3-PadG)") (class "Default")
      (node (ref "Q3") (pin "G") (pinfunction "G_G") (pintype "bidirectional"))
      (node (ref "R10") (pin "2") (pinfunction "2_2") (pintype "passive"))
      (node (ref "R73") (pin "2") (pinfunction "2_2") (pintype "passive"))
    )
    (net (code "140") (name "Net-(Q4-PadD)") (class "Default")
      (node (ref "Q4") (pin "D") (pinfunction "D_D") (pintype "bidirectional"))
      (node (ref "R17") (pin "1") (pinfunction "1_1") (pintype "passive"))
      (node (ref "R22") (pin "1") (pinfunction "1_1") (pintype "passive"))
      (node (ref "R24") (pin "1") (pinfunction "1_1") (pintype "passive"))
    )
    (net (code "141") (name "Net-(Q4-PadG)") (class "Default")
      (node (ref "Q4") (pin "G") (pinfunction "G_G") (pintype "bidirectional"))
      (node (ref "R74") (pin "2") (pinfunction "2_2") (pintype "passive"))
      (node (ref "R8") (pin "2") (pinfunction "2_2") (pintype "passive"))
    )
    (net (code "142") (name "Net-(Q5-PadG)") (class "Default")
      (node (ref "Q5") (pin "G") (pinfunction "G_G") (pintype "bidirectional"))
      (node (ref "R33") (pin "1") (pinfunction "1_1") (pintype "passive"))
      (node (ref "R34") (pin "2") (pinfunction "2_2") (pintype "passive"))
    )
    (net (code "143") (name "Net-(R26-Pad1)") (class "Default")
      (node (ref "R26") (pin "1") (pinfunction "1_1") (pintype "passive"))
      (node (ref "U2") (pin "2") (pinfunction "2_2") (pintype "passive"))
    )
    (net (code "144") (name "Net-(R27-Pad1)") (class "Default")
      (node (ref "R27") (pin "1") (pinfunction "1_1") (pintype "passive"))
      (node (ref "U3") (pin "2") (pinfunction "2_2") (pintype "passive"))
    )
    (net (code "145") (name "Net-(TERMA-A)") (class "Default")
      (node (ref "R11") (pin "2") (pinfunction "2_2") (pintype "passive"))
      (node (ref "TERM") (pin "A1") (pinfunction "A_A1") (pintype "passive"))
    )
    (net (code "146") (name "Net-(TERMB-A)") (class "Default")
      (node (ref "R9") (pin "2") (pinfunction "2_2") (pintype "passive"))
      (node (ref "TERM") (pin "A2") (pinfunction "A_A2") (pintype "passive"))
    )
    (net (code "147") (name "Net-(U4-~{1G})") (class "Default")
      (node (ref "R31") (pin "1") (pinfunction "1_1") (pintype "passive"))
      (node (ref "U4") (pin "1") (pinfunction "~{1G}_1") (pintype "input"))
      (node (ref "U4") (pin "4") (pinfunction "~{2G}_4") (pintype "input"))
    )
    (net (code "148") (name "Net-(U4-~{3G})") (class "Default")
      (node (ref "R32") (pin "1") (pinfunction "1_1") (pintype "passive"))
      (node (ref "U4") (pin "10") (pinfunction "~{3G}_10") (pintype "input"))
      (node (ref "U4") (pin "13") (pinfunction "~{4G}_13") (pintype "input"))
    )
    (net (code "149") (name "Net-(U5A-+IN)") (class "Default")
      (node (ref "R28") (pin "2") (pinfunction "2_2") (pintype "passive"))
      (node (ref "U5") (pin "3") (pinfunction "+IN_3") (pintype "input"))
    )
    (net (code "150") (name "Net-(U5A--IN)") (class "Default")
      (node (ref "C6") (pin "1") (pinfunction "1_1") (pintype "passive"))
      (node (ref "R26") (pin "2") (pinfunction "2_2") (pintype "passive"))
      (node (ref "U5") (pin "4") (pinfunction "-IN_4") (pintype "input"))
    )
    (net (code "151") (name "Net-(U6A-+IN)") (class "Default")
      (node (ref "R29") (pin "2") (pinfunction "2_2") (pintype "passive"))
      (node (ref "U6") (pin "3") (pinfunction "+IN_3") (pintype "input"))
    )
    (net (code "152") (name "Net-(U6A--IN)") (class "Default")
      (node (ref "C7") (pin "1") (pinfunction "1_1") (pintype "passive"))
      (node (ref "R27") (pin "2") (pinfunction "2_2") (pintype "passive"))
      (node (ref "U6") (pin "4") (pinfunction "-IN_4") (pintype "input"))
    )
    (net (code "153") (name "Net-(U9-GPIO0)") (class "Default")
      (node (ref "R48") (pin "2") (pinfunction "2_2") (pintype "passive"))
      (node (ref "U9") (pin "28") (pinfunction "GPIO0_28") (pintype "bidirectional"))
    )
    (net (code "154") (name "Net-(U9-GPIO1)") (class "Default")
      (node (ref "R40") (pin "2") (pinfunction "2_2") (pintype "passive"))
      (node (ref "U9") (pin "27") (pinfunction "GPIO1_27") (pintype "bidirectional"))
    )
    (net (code "155") (name "Net-(U9-GPIO2)") (class "Default")
      (node (ref "R47") (pin "2") (pinfunction "2_2") (pintype "passive"))
      (node (ref "U9") (pin "26") (pinfunction "GPIO2_26") (pintype "bidirectional"))
    )
    (net (code "156") (name "Net-(U9-GPIO3)") (class "Default")
      (node (ref "TP29") (pin "TP") (pinfunction "TP_TP") (pintype "bidirectional"))
      (node (ref "U9") (pin "25") (pinfunction "GPIO3_25") (pintype "bidirectional"))
    )
    (net (code "157") (name "Net-(U9-HSYNC)") (class "Default")
      (node (ref "R50") (pin "2") (pinfunction "2_2") (pintype "passive"))
      (node (ref "U9") (pin "10") (pinfunction "HSYNC_10") (pintype "output"))
    )
    (net (code "158") (name "Net-(U9-LOCK)") (class "Default")
      (node (ref "R33") (pin "2") (pinfunction "2_2") (pintype "passive"))
      (node (ref "U9") (pin "48") (pinfunction "LOCK_48") (pintype "input"))
    )
    (net (code "159") (name "Net-(U9-PCLK)") (class "Default")
      (node (ref "R49") (pin "2") (pinfunction "2_2") (pintype "passive"))
      (node (ref "U9") (pin "8") (pinfunction "PCLK_8") (pintype "output"))
    )
    (net (code "160") (name "Net-(U9-PDN)") (class "Default")
      (node (ref "C4") (pin "2") (pinfunction "2_2") (pintype "passive"))
      (node (ref "R25") (pin "2") (pinfunction "2_2") (pintype "passive"))
      (node (ref "U9") (pin "30") (pinfunction "PDN_30") (pintype "input"))
    )
    (net (code "161") (name "Net-(U9-RIN0+)") (class "Default")
      (node (ref "C16") (pin "1") (pinfunction "1_1") (pintype "passive"))
      (node (ref "U9") (pin "41") (pinfunction "RIN0+_41") (pintype "input"))
    )
    (net (code "162") (name "Net-(U9-RIN0-)") (class "Default")
      (node (ref "C12") (pin "1") (pinfunction "1_1") (pintype "passive"))
      (node (ref "U9") (pin "42") (pinfunction "RIN0-_42") (pintype "input"))
    )
    (net (code "163") (name "Net-(U9-ROUT0)") (class "Default")
      (node (ref "R54") (pin "2") (pinfunction "2_2") (pintype "passive"))
      (node (ref "U9") (pin "24") (pinfunction "ROUT0_24") (pintype "output"))
    )
    (net (code "164") (name "Net-(U9-ROUT1)") (class "Default")
      (node (ref "R38") (pin "2") (pinfunction "2_2") (pintype "passive"))
      (node (ref "U9") (pin "23") (pinfunction "ROUT1_23") (pintype "output"))
    )
    (net (code "165") (name "Net-(U9-ROUT2)") (class "Default")
      (node (ref "R45") (pin "2") (pinfunction "2_2") (pintype "passive"))
      (node (ref "U9") (pin "22") (pinfunction "ROUT2_22") (pintype "output"))
    )
    (net (code "166") (name "Net-(U9-ROUT3)") (class "Default")
      (node (ref "R53") (pin "2") (pinfunction "2_2") (pintype "passive"))
      (node (ref "U9") (pin "21") (pinfunction "ROUT3_21") (pintype "output"))
    )
    (net (code "167") (name "Net-(U9-ROUT4)") (class "Default")
      (node (ref "R37") (pin "2") (pinfunction "2_2") (pintype "passive"))
      (node (ref "U9") (pin "19") (pinfunction "ROUT4_19") (pintype "output"))
    )
    (net (code "168") (name "Net-(U9-ROUT5)") (class "Default")
      (node (ref "R44") (pin "2") (pinfunction "2_2") (pintype "passive"))
      (node (ref "U9") (pin "18") (pinfunction "ROUT5_18") (pintype "output"))
    )
    (net (code "169") (name "Net-(U9-ROUT6)") (class "Default")
      (node (ref "R52") (pin "2") (pinfunction "2_2") (pintype "passive"))
      (node (ref "U9") (pin "16") (pinfunction "ROUT6_16") (pintype "output"))
    )
    (net (code "170") (name "Net-(U9-ROUT7)") (class "Default")
      (node (ref "R36") (pin "2") (pinfunction "2_2") (pintype "passive"))
      (node (ref "U9") (pin "15") (pinfunction "ROUT7_15") (pintype "output"))
    )
    (net (code "171") (name "Net-(U9-ROUT8)") (class "Default")
      (node (ref "R43") (pin "2") (pinfunction "2_2") (pintype "passive"))
      (node (ref "U9") (pin "14") (pinfunction "ROUT8_14") (pintype "output"))
    )
    (net (code "172") (name "Net-(U9-ROUT9)") (class "Default")
      (node (ref "R51") (pin "2") (pinfunction "2_2") (pintype "passive"))
      (node (ref "U9") (pin "13") (pinfunction "ROUT9_13") (pintype "output"))
    )
    (net (code "173") (name "Net-(U9-ROUT10)") (class "Default")
      (node (ref "R35") (pin "2") (pinfunction "2_2") (pintype "passive"))
      (node (ref "U9") (pin "12") (pinfunction "ROUT10_12") (pintype "output"))
    )
    (net (code "174") (name "Net-(U9-ROUT11)") (class "Default")
      (node (ref "R42") (pin "2") (pinfunction "2_2") (pintype "passive"))
      (node (ref "U9") (pin "11") (pinfunction "ROUT11_11") (pintype "output"))
    )
    (net (code "175") (name "Net-(U9-VDDCML0)") (class "Default")
      (node (ref "C11") (pin "2") (pinfunction "2_2") (pintype "passive"))
      (node (ref "C15") (pin "2") (pinfunction "2_2") (pintype "passive"))
      (node (ref "C19") (pin "2") (pinfunction "2_2") (pintype "passive"))
      (node (ref "L5") (pin "1") (pinfunction "1_1") (pintype "passive"))
      (node (ref "U9") (pin "40") (pinfunction "VDDCML0_40") (pintype "power_in"))
    )
    (net (code "176") (name "Net-(U9-VDDCML1)") (class "Default")
      (node (ref "C10") (pin "2") (pinfunction "2_2") (pintype "passive"))
      (node (ref "C14") (pin "2") (pinfunction "2_2") (pintype "passive"))
      (node (ref "C18") (pin "2") (pinfunction "2_2") (pintype "passive"))
      (node (ref "L4") (pin "1") (pinfunction "1_1") (pintype "passive"))
      (node (ref "U9") (pin "31") (pinfunction "VDDCML1_31") (pintype "power_in"))
    )
    (net (code "177") (name "Net-(U9-VDDPLL)") (class "Default")
      (node (ref "C22") (pin "2") (pinfunction "2_2") (pintype "passive"))
      (node (ref "C23") (pin "2") (pinfunction "2_2") (pintype "passive"))
      (node (ref "C26") (pin "2") (pinfunction "2_2") (pintype "passive"))
      (node (ref "L6") (pin "2") (pinfunction "2_2") (pintype "passive"))
      (node (ref "U9") (pin "45") (pinfunction "VDDPLL_45") (pintype "power_in"))
    )
    (net (code "178") (name "Net-(U9-VSYNC)") (class "Default")
      (node (ref "R41") (pin "2") (pinfunction "2_2") (pintype "passive"))
      (node (ref "U9") (pin "9") (pinfunction "VSYNC_9") (pintype "output"))
    )
    (net (code "179") (name "Net-(U10-FB1)") (class "Default")
      (node (ref "R55") (pin "1") (pinfunction "1_1") (pintype "passive"))
      (node (ref "U10") (pin "E4") (pinfunction "FB1_E4") (pintype "input"))
    )
    (net (code "180") (name "Net-(U10-FB2)") (class "Default")
      (node (ref "R59") (pin "1") (pinfunction "1_1") (pintype "passive"))
      (node (ref "U10") (pin "A4") (pinfunction "FB2_A4") (pintype "input"))
    )
    (net (code "181") (name "Net-(U10-FREQ)") (class "Default")
      (node (ref "R64") (pin "1") (pinfunction "1_1") (pintype "passive"))
      (node (ref "U10") (pin "C4") (pinfunction "FREQ_C4") (pintype "input"))
    )
    (net (code "182") (name "Net-(U10-TRACK{slash}SS1)") (class "Default")
      (node (ref "C40") (pin "2") (pinfunction "2_2") (pintype "passive"))
      (node (ref "U10") (pin "E3") (pinfunction "TRACK/SS1_E3") (pintype "input"))
    )
    (net (code "183") (name "Net-(U10-TRACK{slash}SS2)") (class "Default")
      (node (ref "C39") (pin "2") (pinfunction "2_2") (pintype "passive"))
      (node (ref "U10") (pin "A3") (pinfunction "TRACK/SS2_A3") (pintype "input"))
    )
    (net (code "184") (name "Net-(U12-EN)") (class "Default")
      (node (ref "L7/0R") (pin "2") (pinfunction "2_2") (pintype "passive"))
      (node (ref "U12") (pin "1") (pinfunction "VIN_1") (pintype "power_in"))
      (node (ref "U12") (pin "6") (pinfunction "EN_6") (pintype "input"))
    )
    (net (code "185") (name "Net-(U12-TRIM)") (class "Default")
      (node (ref "R68") (pin "1") (pinfunction "1_1") (pintype "passive"))
      (node (ref "U12") (pin "4") (pinfunction "TRIM_4") (pintype "passive"))
    )
    (net (code "186") (name "Net-(U17-VOD)") (class "Default")
      (node (ref "R39") (pin "1") (pinfunction "1_1") (pintype "passive"))
      (node (ref "U17") (pin "P6") (pinfunction "VOD_P6") (pintype "output"))
    )
    (net (code "187") (name "PASS") (class "Default")
      (node (ref "R39") (pin "2") (pinfunction "2_2") (pintype "passive"))
      (node (ref "TP5") (pin "TP") (pinfunction "TP_TP") (pintype "bidirectional"))
      (node (ref "U9") (pin "47") (pinfunction "PASS_47") (pintype "input"))
    )
    (net (code "188") (name "PCLK_ISO") (class "Default")
      (node (ref "R49") (pin "1") (pinfunction "1_1") (pintype "passive"))
      (node (ref "U16") (pin "P5") (pinfunction "VIC_P5") (pintype "input"))
    )
    (net (code "189") (name "PCLK_N") (class "Default")
      (node (ref "FMC_LPC") (pin "P$43") (pinfunction "CLK1_M2C_N_P$43") (pintype "bidirectional"))
      (node (ref "U20") (pin "35") (pinfunction "D3Z_35") (pintype "output"))
    )
    (net (code "190") (name "PCLK_P") (class "Default")
      (node (ref "FMC_LPC") (pin "P$42") (pinfunction "CLK1_M2C_P_P$42") (pintype "bidirectional"))
      (node (ref "U20") (pin "36") (pinfunction "D3Y_36") (pintype "output"))
    )
    (net (code "191") (name "SCL") (class "Default")
      (node (ref "FMC_LPC") (pin "P$150") (pinfunction "SCL_P$150") (pintype "bidirectional"))
      (node (ref "R72") (pin "1") (pinfunction "1_1") (pintype "passive"))
      (node (ref "TP25") (pin "1") (pinfunction "TP_1") (pintype "bidirectional"))
      (node (ref "U11") (pin "3") (pinfunction "SCL1_3") (pintype "input"))
      (node (ref "U8") (pin "7") (pinfunction "SCL_7") (pintype "input"))
    )
    (net (code "192") (name "SCL_ISO") (class "Default")
      (node (ref "R65") (pin "1") (pinfunction "1_1") (pintype "passive"))
      (node (ref "TP26") (pin "1") (pinfunction "TP_1") (pintype "bidirectional"))
      (node (ref "U11") (pin "6") (pinfunction "SCL2_6") (pintype "output"))
      (node (ref "U9") (pin "2") (pinfunction "SCL_2") (pintype "input"))
    )
    (net (code "193") (name "SDA") (class "Default")
      (node (ref "FMC_LPC") (pin "P$151") (pinfunction "SDA_P$151") (pintype "bidirectional"))
      (node (ref "R71") (pin "1") (pinfunction "1_1") (pintype "passive"))
      (node (ref "TP24") (pin "1") (pinfunction "TP_1") (pintype "bidirectional"))
      (node (ref "U11") (pin "2") (pinfunction "SDA1_2") (pintype "input"))
      (node (ref "U8") (pin "8") (pinfunction "SDA_8") (pintype "input"))
    )
    (net (code "194") (name "SDA_ISO") (class "Default")
      (node (ref "R66") (pin "1") (pinfunction "1_1") (pintype "passive"))
      (node (ref "TP27") (pin "1") (pinfunction "TP_1") (pintype "bidirectional"))
      (node (ref "U11") (pin "7") (pinfunction "SDA2_7") (pintype "output"))
      (node (ref "U9") (pin "1") (pinfunction "SDA_1") (pintype "bidirectional"))
    )
    (net (code "195") (name "TDI-TDO") (class "Default")
      (node (ref "FMC_LPC") (pin "P$110") (pinfunction "TDI_P$110") (pintype "bidirectional"))
      (node (ref "FMC_LPC") (pin "P$111") (pinfunction "TDO_P$111") (pintype "bidirectional"))
    )
    (net (code "196") (name "VSYNC_ISO") (class "Default")
      (node (ref "R41") (pin "1") (pinfunction "1_1") (pintype "passive"))
      (node (ref "U16") (pin "P4") (pinfunction "VIB_P4") (pintype "input"))
    )
    (net (code "197") (name "VSYNC_N") (class "Default")
      (node (ref "FMC_LPC") (pin "P$5") (pinfunction "CLK0_M2C_N_P$5") (pintype "bidirectional"))
      (node (ref "U20") (pin "37") (pinfunction "D2Z_37") (pintype "output"))
    )
    (net (code "198") (name "VSYNC_P") (class "Default")
      (node (ref "FMC_LPC") (pin "P$4") (pinfunction "CLK0_M2C_P_P$4") (pintype "bidirectional"))
      (node (ref "U20") (pin "38") (pinfunction "D2Y_38") (pintype "output"))
    )
    (net (code "199") (name "V_PROTECT") (class "Default")
      (node (ref "C55") (pin "2") (pinfunction "2_2") (pintype "passive"))
      (node (ref "D1") (pin "2") (pinfunction "C_2") (pintype "passive"))
      (node (ref "D2") (pin "2") (pinfunction "C_2") (pintype "passive"))
      (node (ref "D3") (pin "2") (pinfunction "C_2") (pintype "passive"))
      (node (ref "D4") (pin "2") (pinfunction "C_2") (pintype "passive"))
      (node (ref "D6") (pin "C") (pinfunction "C_C") (pintype "passive"))
      (node (ref "R69") (pin "1") (pinfunction "1_1") (pintype "passive"))
      (node (ref "R70") (pin "1") (pinfunction "1_1") (pintype "passive"))
      (node (ref "TP9") (pin "1") (pinfunction "TP_1") (pintype "bidirectional"))
    )
    (net (code "200") (name "unconnected-(FMC_LPCA-3P3VAUX-PadP$112)") (class "Default")
      (node (ref "FMC_LPC") (pin "P$112") (pinfunction "3P3VAUX_P$112") (pintype "bidirectional"))
    )
    (net (code "201") (name "unconnected-(FMC_LPCA-DP0_C2M_N-PadP$123)") (class "Default")
      (node (ref "FMC_LPC") (pin "P$123") (pinfunction "DP0_C2M_N_P$123") (pintype "bidirectional"))
    )
    (net (code "202") (name "unconnected-(FMC_LPCA-DP0_C2M_P-PadP$122)") (class "Default")
      (node (ref "FMC_LPC") (pin "P$122") (pinfunction "DP0_C2M_P_P$122") (pintype "bidirectional"))
    )
    (net (code "203") (name "unconnected-(FMC_LPCA-DP0_M2C_N-PadP$127)") (class "Default")
      (node (ref "FMC_LPC") (pin "P$127") (pinfunction "DP0_M2C_N_P$127") (pintype "bidirectional"))
    )
    (net (code "204") (name "unconnected-(FMC_LPCA-DP0_M2C_P-PadP$126)") (class "Default")
      (node (ref "FMC_LPC") (pin "P$126") (pinfunction "DP0_M2C_P_P$126") (pintype "bidirectional"))
    )
    (net (code "205") (name "unconnected-(FMC_LPCA-GA0-PadP$154)") (class "Default")
      (node (ref "FMC_LPC") (pin "P$154") (pinfunction "GA0_P$154") (pintype "bidirectional"))
    )
    (net (code "206") (name "unconnected-(FMC_LPCA-GA1-PadP$115)") (class "Default")
      (node (ref "FMC_LPC") (pin "P$115") (pinfunction "GA1_P$115") (pintype "bidirectional"))
    )
    (net (code "207") (name "unconnected-(FMC_LPCA-LA00_N_CC-PadP$47)") (class "Default")
      (node (ref "FMC_LPC") (pin "P$47") (pinfunction "LA00_N_CC_P$47") (pintype "bidirectional"))
    )
    (net (code "208") (name "unconnected-(FMC_LPCA-LA00_P_CC-PadP$46)") (class "Default")
      (node (ref "FMC_LPC") (pin "P$46") (pinfunction "LA00_P_CC_P$46") (pintype "bidirectional"))
    )
    (net (code "209") (name "unconnected-(FMC_LPCA-LA26_N-PadP$107)") (class "Default")
      (node (ref "FMC_LPC") (pin "P$107") (pinfunction "LA26_N_P$107") (pintype "bidirectional"))
    )
    (net (code "210") (name "unconnected-(FMC_LPCA-LA26_P-PadP$106)") (class "Default")
      (node (ref "FMC_LPC") (pin "P$106") (pinfunction "LA26_P_P$106") (pintype "bidirectional"))
    )
    (net (code "211") (name "unconnected-(FMC_LPCA-LA27_N-PadP$147)") (class "Default")
      (node (ref "FMC_LPC") (pin "P$147") (pinfunction "LA27_N_P$147") (pintype "bidirectional"))
    )
    (net (code "212") (name "unconnected-(FMC_LPCA-LA27_P-PadP$146)") (class "Default")
      (node (ref "FMC_LPC") (pin "P$146") (pinfunction "LA27_P_P$146") (pintype "bidirectional"))
    )
    (net (code "213") (name "unconnected-(FMC_LPCA-LA28_N-PadP$32)") (class "Default")
      (node (ref "FMC_LPC") (pin "P$32") (pinfunction "LA28_N_P$32") (pintype "bidirectional"))
    )
    (net (code "214") (name "unconnected-(FMC_LPCA-LA28_P-PadP$31)") (class "Default")
      (node (ref "FMC_LPC") (pin "P$31") (pinfunction "LA28_P_P$31") (pintype "bidirectional"))
    )
    (net (code "215") (name "unconnected-(FMC_LPCA-LA29_N-PadP$71)") (class "Default")
      (node (ref "FMC_LPC") (pin "P$71") (pinfunction "LA29_N_P$71") (pintype "bidirectional"))
    )
    (net (code "216") (name "unconnected-(FMC_LPCA-LA29_P-PadP$70)") (class "Default")
      (node (ref "FMC_LPC") (pin "P$70") (pinfunction "LA29_P_P$70") (pintype "bidirectional"))
    )
    (net (code "217") (name "unconnected-(FMC_LPCA-LA30_N-PadP$35)") (class "Default")
      (node (ref "FMC_LPC") (pin "P$35") (pinfunction "LA30_N_P$35") (pintype "bidirectional"))
    )
    (net (code "218") (name "unconnected-(FMC_LPCA-LA30_P-PadP$34)") (class "Default")
      (node (ref "FMC_LPC") (pin "P$34") (pinfunction "LA30_P_P$34") (pintype "bidirectional"))
    )
    (net (code "219") (name "unconnected-(FMC_LPCA-LA31_N-PadP$74)") (class "Default")
      (node (ref "FMC_LPC") (pin "P$74") (pinfunction "LA31_N_P$74") (pintype "bidirectional"))
    )
    (net (code "220") (name "unconnected-(FMC_LPCA-LA31_P-PadP$73)") (class "Default")
      (node (ref "FMC_LPC") (pin "P$73") (pinfunction "LA31_P_P$73") (pintype "bidirectional"))
    )
    (net (code "221") (name "unconnected-(FMC_LPCA-LA32_N-PadP$38)") (class "Default")
      (node (ref "FMC_LPC") (pin "P$38") (pinfunction "LA32_N_P$38") (pintype "bidirectional"))
    )
    (net (code "222") (name "unconnected-(FMC_LPCA-LA32_P-PadP$37)") (class "Default")
      (node (ref "FMC_LPC") (pin "P$37") (pinfunction "LA32_P_P$37") (pintype "bidirectional"))
    )
    (net (code "223") (name "unconnected-(FMC_LPCA-LA33_N-PadP$77)") (class "Default")
      (node (ref "FMC_LPC") (pin "P$77") (pinfunction "LA33_N_P$77") (pintype "bidirectional"))
    )
    (net (code "224") (name "unconnected-(FMC_LPCA-LA33_P-PadP$76)") (class "Default")
      (node (ref "FMC_LPC") (pin "P$76") (pinfunction "LA33_P_P$76") (pintype "bidirectional"))
    )
    (net (code "225") (name "unconnected-(FMC_LPCA-PG_C2M-PadP$81)") (class "Default")
      (node (ref "FMC_LPC") (pin "P$81") (pinfunction "PG_C2M_P$81") (pintype "bidirectional"))
    )
    (net (code "226") (name "unconnected-(FMC_LPCA-PRSNT_M2C_L-PadP$2)") (class "Default")
      (node (ref "FMC_LPC") (pin "P$2") (pinfunction "PRSNT_M2C_L_P$2") (pintype "bidirectional"))
    )
    (net (code "227") (name "unconnected-(FMC_LPCA-TCK-PadP$109)") (class "Default")
      (node (ref "FMC_LPC") (pin "P$109") (pinfunction "TCK_P$109") (pintype "bidirectional"))
    )
    (net (code "228") (name "unconnected-(FMC_LPCA-TMS-PadP$113)") (class "Default")
      (node (ref "FMC_LPC") (pin "P$113") (pinfunction "TMS_P$113") (pintype "bidirectional"))
    )
    (net (code "229") (name "unconnected-(FMC_LPCA-TRST_L-PadP$114)") (class "Default")
      (node (ref "FMC_LPC") (pin "P$114") (pinfunction "TRST_L_P$114") (pintype "bidirectional"))
    )
    (net (code "230") (name "unconnected-(FMC_LPCA-VADJ1-PadP$79)") (class "Default")
      (node (ref "FMC_LPC") (pin "P$79") (pinfunction "VADJ1_P$79") (pintype "bidirectional"))
    )
    (net (code "231") (name "unconnected-(FMC_LPCA-VADJ2-PadP$40)") (class "Default")
      (node (ref "FMC_LPC") (pin "P$40") (pinfunction "VADJ2_P$40") (pintype "bidirectional"))
    )
    (net (code "232") (name "unconnected-(FMC_LPCA-VREF_A_M2C-PadP$1)") (class "Default")
      (node (ref "FMC_LPC") (pin "P$1") (pinfunction "VREF_A_M2C_P$1") (pintype "bidirectional"))
    )
    (net (code "233") (name "unconnected-(U$2-PadP$1)") (class "Default")
      (node (ref "U$2") (pin "P$1") (pinfunction "P$1_P$1") (pintype "bidirectional"))
    )
    (net (code "234") (name "unconnected-(U$2-PadP$2)") (class "Default")
      (node (ref "U$2") (pin "P$2") (pinfunction "P$2_P$2") (pintype "bidirectional"))
    )
    (net (code "235") (name "unconnected-(U$2-PadP$3)") (class "Default")
      (node (ref "U$2") (pin "P$3") (pinfunction "P$3_P$3") (pintype "bidirectional"))
    )
    (net (code "236") (name "unconnected-(U$2-PadP$4)") (class "Default")
      (node (ref "U$2") (pin "P$4") (pinfunction "P$4_P$4") (pintype "bidirectional"))
    )
    (net (code "237") (name "unconnected-(U$2-PadP$5)") (class "Default")
      (node (ref "U$2") (pin "P$5") (pinfunction "P$5_P$5") (pintype "bidirectional"))
    )
    (net (code "238") (name "unconnected-(U$2-PadP$6)") (class "Default")
      (node (ref "U$2") (pin "P$6") (pinfunction "P$6_P$6") (pintype "bidirectional"))
    )
    (net (code "239") (name "unconnected-(U$2-PadP$7)") (class "Default")
      (node (ref "U$2") (pin "P$7") (pinfunction "P$7_P$7") (pintype "bidirectional"))
    )
    (net (code "240") (name "unconnected-(U$2-PadP$8)") (class "Default")
      (node (ref "U$2") (pin "P$8") (pinfunction "P$8_P$8") (pintype "bidirectional"))
    )
    (net (code "241") (name "unconnected-(U$2-PadP$9)") (class "Default")
      (node (ref "U$2") (pin "P$9") (pinfunction "P$9_P$9") (pintype "bidirectional"))
    )
    (net (code "242") (name "unconnected-(U$2-PadP$10)") (class "Default")
      (node (ref "U$2") (pin "P$10") (pinfunction "P$10_P$10") (pintype "bidirectional"))
    )
    (net (code "243") (name "unconnected-(U$2-PadP$11)") (class "Default")
      (node (ref "U$2") (pin "P$11") (pinfunction "P$11_P$11") (pintype "bidirectional"))
    )
    (net (code "244") (name "unconnected-(U$2-PadP$12)") (class "Default")
      (node (ref "U$2") (pin "P$12") (pinfunction "P$12_P$12") (pintype "bidirectional"))
    )
    (net (code "245") (name "unconnected-(U$2-PadP$13)") (class "Default")
      (node (ref "U$2") (pin "P$13") (pinfunction "P$13_P$13") (pintype "bidirectional"))
    )
    (net (code "246") (name "unconnected-(U$2-PadP$14)") (class "Default")
      (node (ref "U$2") (pin "P$14") (pinfunction "P$14_P$14") (pintype "bidirectional"))
    )
    (net (code "247") (name "unconnected-(U$2-PadP$15)") (class "Default")
      (node (ref "U$2") (pin "P$15") (pinfunction "P$15_P$15") (pintype "bidirectional"))
    )
    (net (code "248") (name "unconnected-(U$2-PadP$16)") (class "Default")
      (node (ref "U$2") (pin "P$16") (pinfunction "P$16_P$16") (pintype "bidirectional"))
    )
    (net (code "249") (name "unconnected-(U$2-PadP$17)") (class "Default")
      (node (ref "U$2") (pin "P$17") (pinfunction "P$17_P$17") (pintype "bidirectional"))
    )
    (net (code "250") (name "unconnected-(U$2-PadP$18)") (class "Default")
      (node (ref "U$2") (pin "P$18") (pinfunction "P$18_P$18") (pintype "bidirectional"))
    )
    (net (code "251") (name "unconnected-(U$2-PadP$19)") (class "Default")
      (node (ref "U$2") (pin "P$19") (pinfunction "P$19_P$19") (pintype "bidirectional"))
    )
    (net (code "252") (name "unconnected-(U$2-PadP$20)") (class "Default")
      (node (ref "U$2") (pin "P$20") (pinfunction "P$20_P$20") (pintype "bidirectional"))
    )
    (net (code "253") (name "unconnected-(U$2-PadP$21)") (class "Default")
      (node (ref "U$2") (pin "P$21") (pinfunction "P$21_P$21") (pintype "bidirectional"))
    )
    (net (code "254") (name "unconnected-(U$2-PadP$22)") (class "Default")
      (node (ref "U$2") (pin "P$22") (pinfunction "P$22_P$22") (pintype "bidirectional"))
    )
    (net (code "255") (name "unconnected-(U$2-PadP$23)") (class "Default")
      (node (ref "U$2") (pin "P$23") (pinfunction "P$23_P$23") (pintype "bidirectional"))
    )
    (net (code "256") (name "unconnected-(U$2-PadP$24)") (class "Default")
      (node (ref "U$2") (pin "P$24") (pinfunction "P$24_P$24") (pintype "bidirectional"))
    )
    (net (code "257") (name "unconnected-(U$2-PadP$25)") (class "Default")
      (node (ref "U$2") (pin "P$25") (pinfunction "P$25_P$25") (pintype "bidirectional"))
    )
    (net (code "258") (name "unconnected-(U$2-PadP$26)") (class "Default")
      (node (ref "U$2") (pin "P$26") (pinfunction "P$26_P$26") (pintype "bidirectional"))
    )
    (net (code "259") (name "unconnected-(U$2-PadP$27)") (class "Default")
      (node (ref "U$2") (pin "P$27") (pinfunction "P$27_P$27") (pintype "bidirectional"))
    )
    (net (code "260") (name "unconnected-(U$2-PadP$28)") (class "Default")
      (node (ref "U$2") (pin "P$28") (pinfunction "P$28_P$28") (pintype "bidirectional"))
    )
    (net (code "261") (name "unconnected-(U$2-PadP$29)") (class "Default")
      (node (ref "U$2") (pin "P$29") (pinfunction "P$29_P$29") (pintype "bidirectional"))
    )
    (net (code "262") (name "unconnected-(U$2-PadP$30)") (class "Default")
      (node (ref "U$2") (pin "P$30") (pinfunction "P$30_P$30") (pintype "bidirectional"))
    )
    (net (code "263") (name "unconnected-(U$2-PadP$31)") (class "Default")
      (node (ref "U$2") (pin "P$31") (pinfunction "P$31_P$31") (pintype "bidirectional"))
    )
    (net (code "264") (name "unconnected-(U$2-PadP$32)") (class "Default")
      (node (ref "U$2") (pin "P$32") (pinfunction "P$32_P$32") (pintype "bidirectional"))
    )
    (net (code "265") (name "unconnected-(U$2-PadP$33)") (class "Default")
      (node (ref "U$2") (pin "P$33") (pinfunction "P$33_P$33") (pintype "bidirectional"))
    )
    (net (code "266") (name "unconnected-(U$2-PadP$34)") (class "Default")
      (node (ref "U$2") (pin "P$34") (pinfunction "P$34_P$34") (pintype "bidirectional"))
    )
    (net (code "267") (name "unconnected-(U$2-PadP$35)") (class "Default")
      (node (ref "U$2") (pin "P$35") (pinfunction "P$35_P$35") (pintype "bidirectional"))
    )
    (net (code "268") (name "unconnected-(U$2-PadP$36)") (class "Default")
      (node (ref "U$2") (pin "P$36") (pinfunction "P$36_P$36") (pintype "bidirectional"))
    )
    (net (code "269") (name "unconnected-(U$2-PadP$37)") (class "Default")
      (node (ref "U$2") (pin "P$37") (pinfunction "P$37_P$37") (pintype "bidirectional"))
    )
    (net (code "270") (name "unconnected-(U$2-PadP$38)") (class "Default")
      (node (ref "U$2") (pin "P$38") (pinfunction "P$38_P$38") (pintype "bidirectional"))
    )
    (net (code "271") (name "unconnected-(U$2-PadP$39)") (class "Default")
      (node (ref "U$2") (pin "P$39") (pinfunction "P$39_P$39") (pintype "bidirectional"))
    )
    (net (code "272") (name "unconnected-(U$2-PadP$40)") (class "Default")
      (node (ref "U$2") (pin "P$40") (pinfunction "P$40_P$40") (pintype "bidirectional"))
    )
    (net (code "273") (name "unconnected-(U$2-PadP$41)") (class "Default")
      (node (ref "U$2") (pin "P$41") (pinfunction "P$41_P$41") (pintype "bidirectional"))
    )
    (net (code "274") (name "unconnected-(U$2-PadP$42)") (class "Default")
      (node (ref "U$2") (pin "P$42") (pinfunction "P$42_P$42") (pintype "bidirectional"))
    )
    (net (code "275") (name "unconnected-(U$2-PadP$43)") (class "Default")
      (node (ref "U$2") (pin "P$43") (pinfunction "P$43_P$43") (pintype "bidirectional"))
    )
    (net (code "276") (name "unconnected-(U$2-PadP$44)") (class "Default")
      (node (ref "U$2") (pin "P$44") (pinfunction "P$44_P$44") (pintype "bidirectional"))
    )
    (net (code "277") (name "unconnected-(U$2-PadP$45)") (class "Default")
      (node (ref "U$2") (pin "P$45") (pinfunction "P$45_P$45") (pintype "bidirectional"))
    )
    (net (code "278") (name "unconnected-(U$2-PadP$46)") (class "Default")
      (node (ref "U$2") (pin "P$46") (pinfunction "P$46_P$46") (pintype "bidirectional"))
    )
    (net (code "279") (name "unconnected-(U$2-PadP$47)") (class "Default")
      (node (ref "U$2") (pin "P$47") (pinfunction "P$47_P$47") (pintype "bidirectional"))
    )
    (net (code "280") (name "unconnected-(U$2-PadP$48)") (class "Default")
      (node (ref "U$2") (pin "P$48") (pinfunction "P$48_P$48") (pintype "bidirectional"))
    )
    (net (code "281") (name "unconnected-(U$2-PadP$49)") (class "Default")
      (node (ref "U$2") (pin "P$49") (pinfunction "P$49_P$49") (pintype "bidirectional"))
    )
    (net (code "282") (name "unconnected-(U$2-PadP$50)") (class "Default")
      (node (ref "U$2") (pin "P$50") (pinfunction "P$50_P$50") (pintype "bidirectional"))
    )
    (net (code "283") (name "unconnected-(U$2-PadP$51)") (class "Default")
      (node (ref "U$2") (pin "P$51") (pinfunction "P$51_P$51") (pintype "bidirectional"))
    )
    (net (code "284") (name "unconnected-(U$2-PadP$52)") (class "Default")
      (node (ref "U$2") (pin "P$52") (pinfunction "P$52_P$52") (pintype "bidirectional"))
    )
    (net (code "285") (name "unconnected-(U$2-PadP$53)") (class "Default")
      (node (ref "U$2") (pin "P$53") (pinfunction "P$53_P$53") (pintype "bidirectional"))
    )
    (net (code "286") (name "unconnected-(U$2-PadP$54)") (class "Default")
      (node (ref "U$2") (pin "P$54") (pinfunction "P$54_P$54") (pintype "bidirectional"))
    )
    (net (code "287") (name "unconnected-(U$2-PadP$55)") (class "Default")
      (node (ref "U$2") (pin "P$55") (pinfunction "P$55_P$55") (pintype "bidirectional"))
    )
    (net (code "288") (name "unconnected-(U$2-PadP$56)") (class "Default")
      (node (ref "U$2") (pin "P$56") (pinfunction "P$56_P$56") (pintype "bidirectional"))
    )
    (net (code "289") (name "unconnected-(U$2-PadP$57)") (class "Default")
      (node (ref "U$2") (pin "P$57") (pinfunction "P$57_P$57") (pintype "bidirectional"))
    )
    (net (code "290") (name "unconnected-(U$2-PadP$58)") (class "Default")
      (node (ref "U$2") (pin "P$58") (pinfunction "P$58_P$58") (pintype "bidirectional"))
    )
    (net (code "291") (name "unconnected-(U$2-PadP$59)") (class "Default")
      (node (ref "U$2") (pin "P$59") (pinfunction "P$59_P$59") (pintype "bidirectional"))
    )
    (net (code "292") (name "unconnected-(U$2-PadP$60)") (class "Default")
      (node (ref "U$2") (pin "P$60") (pinfunction "P$60_P$60") (pintype "bidirectional"))
    )
    (net (code "293") (name "unconnected-(U$2-PadP$61)") (class "Default")
      (node (ref "U$2") (pin "P$61") (pinfunction "P$61_P$61") (pintype "bidirectional"))
    )
    (net (code "294") (name "unconnected-(U$2-PadP$62)") (class "Default")
      (node (ref "U$2") (pin "P$62") (pinfunction "P$62_P$62") (pintype "bidirectional"))
    )
    (net (code "295") (name "unconnected-(U$2-PadP$63)") (class "Default")
      (node (ref "U$2") (pin "P$63") (pinfunction "P$63_P$63") (pintype "bidirectional"))
    )
    (net (code "296") (name "unconnected-(U$2-PadP$64)") (class "Default")
      (node (ref "U$2") (pin "P$64") (pinfunction "P$64_P$64") (pintype "bidirectional"))
    )
    (net (code "297") (name "unconnected-(U$2-PadP$65)") (class "Default")
      (node (ref "U$2") (pin "P$65") (pinfunction "P$65_P$65") (pintype "bidirectional"))
    )
    (net (code "298") (name "unconnected-(U$2-PadP$66)") (class "Default")
      (node (ref "U$2") (pin "P$66") (pinfunction "P$66_P$66") (pintype "bidirectional"))
    )
    (net (code "299") (name "unconnected-(U$2-PadP$67)") (class "Default")
      (node (ref "U$2") (pin "P$67") (pinfunction "P$67_P$67") (pintype "bidirectional"))
    )
    (net (code "300") (name "unconnected-(U$2-PadP$68)") (class "Default")
      (node (ref "U$2") (pin "P$68") (pinfunction "P$68_P$68") (pintype "bidirectional"))
    )
    (net (code "301") (name "unconnected-(U$2B-P$1-PadQ$1)") (class "Default")
      (node (ref "U$2") (pin "Q$1") (pinfunction "P$1_Q$1") (pintype "bidirectional"))
    )
    (net (code "302") (name "unconnected-(U$2B-P$2-PadQ$2)") (class "Default")
      (node (ref "U$2") (pin "Q$2") (pinfunction "P$2_Q$2") (pintype "bidirectional"))
    )
    (net (code "303") (name "unconnected-(U$2B-P$3-PadQ$3)") (class "Default")
      (node (ref "U$2") (pin "Q$3") (pinfunction "P$3_Q$3") (pintype "bidirectional"))
    )
    (net (code "304") (name "unconnected-(U$2B-P$4-PadQ$4)") (class "Default")
      (node (ref "U$2") (pin "Q$4") (pinfunction "P$4_Q$4") (pintype "bidirectional"))
    )
    (net (code "305") (name "unconnected-(U$2B-P$5-PadQ$5)") (class "Default")
      (node (ref "U$2") (pin "Q$5") (pinfunction "P$5_Q$5") (pintype "bidirectional"))
    )
    (net (code "306") (name "unconnected-(U$2B-P$6-PadQ$6)") (class "Default")
      (node (ref "U$2") (pin "Q$6") (pinfunction "P$6_Q$6") (pintype "bidirectional"))
    )
    (net (code "307") (name "unconnected-(U$2B-P$7-PadQ$7)") (class "Default")
      (node (ref "U$2") (pin "Q$7") (pinfunction "P$7_Q$7") (pintype "bidirectional"))
    )
    (net (code "308") (name "unconnected-(U$2B-P$8-PadQ$8)") (class "Default")
      (node (ref "U$2") (pin "Q$8") (pinfunction "P$8_Q$8") (pintype "bidirectional"))
    )
    (net (code "309") (name "unconnected-(U$2B-P$9-PadQ$9)") (class "Default")
      (node (ref "U$2") (pin "Q$9") (pinfunction "P$9_Q$9") (pintype "bidirectional"))
    )
    (net (code "310") (name "unconnected-(U$2B-P$10-PadQ$10)") (class "Default")
      (node (ref "U$2") (pin "Q$10") (pinfunction "P$10_Q$10") (pintype "bidirectional"))
    )
    (net (code "311") (name "unconnected-(U$2B-P$11-PadQ$11)") (class "Default")
      (node (ref "U$2") (pin "Q$11") (pinfunction "P$11_Q$11") (pintype "bidirectional"))
    )
    (net (code "312") (name "unconnected-(U$2B-P$12-PadQ$12)") (class "Default")
      (node (ref "U$2") (pin "Q$12") (pinfunction "P$12_Q$12") (pintype "bidirectional"))
    )
    (net (code "313") (name "unconnected-(U$2B-P$13-PadQ$13)") (class "Default")
      (node (ref "U$2") (pin "Q$13") (pinfunction "P$13_Q$13") (pintype "bidirectional"))
    )
    (net (code "314") (name "unconnected-(U$2B-P$14-PadQ$14)") (class "Default")
      (node (ref "U$2") (pin "Q$14") (pinfunction "P$14_Q$14") (pintype "bidirectional"))
    )
    (net (code "315") (name "unconnected-(U$2B-P$15-PadQ$15)") (class "Default")
      (node (ref "U$2") (pin "Q$15") (pinfunction "P$15_Q$15") (pintype "bidirectional"))
    )
    (net (code "316") (name "unconnected-(U$2B-P$16-PadQ$16)") (class "Default")
      (node (ref "U$2") (pin "Q$16") (pinfunction "P$16_Q$16") (pintype "bidirectional"))
    )
    (net (code "317") (name "unconnected-(U$2B-P$17-PadQ$17)") (class "Default")
      (node (ref "U$2") (pin "Q$17") (pinfunction "P$17_Q$17") (pintype "bidirectional"))
    )
    (net (code "318") (name "unconnected-(U$2B-P$18-PadQ$18)") (class "Default")
      (node (ref "U$2") (pin "Q$18") (pinfunction "P$18_Q$18") (pintype "bidirectional"))
    )
    (net (code "319") (name "unconnected-(U$2B-P$19-PadQ$19)") (class "Default")
      (node (ref "U$2") (pin "Q$19") (pinfunction "P$19_Q$19") (pintype "bidirectional"))
    )
    (net (code "320") (name "unconnected-(U$2B-P$20-PadQ$20)") (class "Default")
      (node (ref "U$2") (pin "Q$20") (pinfunction "P$20_Q$20") (pintype "bidirectional"))
    )
    (net (code "321") (name "unconnected-(U$2B-P$21-PadQ$21)") (class "Default")
      (node (ref "U$2") (pin "Q$21") (pinfunction "P$21_Q$21") (pintype "bidirectional"))
    )
    (net (code "322") (name "unconnected-(U$2B-P$22-PadQ$22)") (class "Default")
      (node (ref "U$2") (pin "Q$22") (pinfunction "P$22_Q$22") (pintype "bidirectional"))
    )
    (net (code "323") (name "unconnected-(U$2B-P$23-PadQ$23)") (class "Default")
      (node (ref "U$2") (pin "Q$23") (pinfunction "P$23_Q$23") (pintype "bidirectional"))
    )
    (net (code "324") (name "unconnected-(U$2B-P$24-PadQ$24)") (class "Default")
      (node (ref "U$2") (pin "Q$24") (pinfunction "P$24_Q$24") (pintype "bidirectional"))
    )
    (net (code "325") (name "unconnected-(U$2B-P$25-PadQ$25)") (class "Default")
      (node (ref "U$2") (pin "Q$25") (pinfunction "P$25_Q$25") (pintype "bidirectional"))
    )
    (net (code "326") (name "unconnected-(U$2B-P$26-PadQ$26)") (class "Default")
      (node (ref "U$2") (pin "Q$26") (pinfunction "P$26_Q$26") (pintype "bidirectional"))
    )
    (net (code "327") (name "unconnected-(U$2B-P$27-PadQ$27)") (class "Default")
      (node (ref "U$2") (pin "Q$27") (pinfunction "P$27_Q$27") (pintype "bidirectional"))
    )
    (net (code "328") (name "unconnected-(U$2B-P$28-PadQ$28)") (class "Default")
      (node (ref "U$2") (pin "Q$28") (pinfunction "P$28_Q$28") (pintype "bidirectional"))
    )
    (net (code "329") (name "unconnected-(U$2B-P$29-PadQ$29)") (class "Default")
      (node (ref "U$2") (pin "Q$29") (pinfunction "P$29_Q$29") (pintype "bidirectional"))
    )
    (net (code "330") (name "unconnected-(U$2B-P$30-PadQ$30)") (class "Default")
      (node (ref "U$2") (pin "Q$30") (pinfunction "P$30_Q$30") (pintype "bidirectional"))
    )
    (net (code "331") (name "unconnected-(U$2B-P$31-PadQ$31)") (class "Default")
      (node (ref "U$2") (pin "Q$31") (pinfunction "P$31_Q$31") (pintype "bidirectional"))
    )
    (net (code "332") (name "unconnected-(U$2B-P$32-PadQ$32)") (class "Default")
      (node (ref "U$2") (pin "Q$32") (pinfunction "P$32_Q$32") (pintype "bidirectional"))
    )
    (net (code "333") (name "unconnected-(U$2B-P$33-PadQ$33)") (class "Default")
      (node (ref "U$2") (pin "Q$33") (pinfunction "P$33_Q$33") (pintype "bidirectional"))
    )
    (net (code "334") (name "unconnected-(U$2B-P$34-PadQ$34)") (class "Default")
      (node (ref "U$2") (pin "Q$34") (pinfunction "P$34_Q$34") (pintype "bidirectional"))
    )
    (net (code "335") (name "unconnected-(U$2B-P$35-PadQ$35)") (class "Default")
      (node (ref "U$2") (pin "Q$35") (pinfunction "P$35_Q$35") (pintype "bidirectional"))
    )
    (net (code "336") (name "unconnected-(U$2B-P$36-PadQ$36)") (class "Default")
      (node (ref "U$2") (pin "Q$36") (pinfunction "P$36_Q$36") (pintype "bidirectional"))
    )
    (net (code "337") (name "unconnected-(U$2B-P$37-PadQ$37)") (class "Default")
      (node (ref "U$2") (pin "Q$37") (pinfunction "P$37_Q$37") (pintype "bidirectional"))
    )
    (net (code "338") (name "unconnected-(U$2B-P$38-PadQ$38)") (class "Default")
      (node (ref "U$2") (pin "Q$38") (pinfunction "P$38_Q$38") (pintype "bidirectional"))
    )
    (net (code "339") (name "unconnected-(U$2B-P$39-PadQ$39)") (class "Default")
      (node (ref "U$2") (pin "Q$39") (pinfunction "P$39_Q$39") (pintype "bidirectional"))
    )
    (net (code "340") (name "unconnected-(U$2B-P$40-PadQ$40)") (class "Default")
      (node (ref "U$2") (pin "Q$40") (pinfunction "P$40_Q$40") (pintype "bidirectional"))
    )
    (net (code "341") (name "unconnected-(U$2B-P$41-PadQ$41)") (class "Default")
      (node (ref "U$2") (pin "Q$41") (pinfunction "P$41_Q$41") (pintype "bidirectional"))
    )
    (net (code "342") (name "unconnected-(U$2B-P$42-PadQ$42)") (class "Default")
      (node (ref "U$2") (pin "Q$42") (pinfunction "P$42_Q$42") (pintype "bidirectional"))
    )
    (net (code "343") (name "unconnected-(U$2B-P$43-PadQ$43)") (class "Default")
      (node (ref "U$2") (pin "Q$43") (pinfunction "P$43_Q$43") (pintype "bidirectional"))
    )
    (net (code "344") (name "unconnected-(U$2B-P$44-PadQ$44)") (class "Default")
      (node (ref "U$2") (pin "Q$44") (pinfunction "P$44_Q$44") (pintype "bidirectional"))
    )
    (net (code "345") (name "unconnected-(U$2B-P$45-PadQ$45)") (class "Default")
      (node (ref "U$2") (pin "Q$45") (pinfunction "P$45_Q$45") (pintype "bidirectional"))
    )
    (net (code "346") (name "unconnected-(U$2B-P$46-PadQ$46)") (class "Default")
      (node (ref "U$2") (pin "Q$46") (pinfunction "P$46_Q$46") (pintype "bidirectional"))
    )
    (net (code "347") (name "unconnected-(U$2B-P$47-PadQ$47)") (class "Default")
      (node (ref "U$2") (pin "Q$47") (pinfunction "P$47_Q$47") (pintype "bidirectional"))
    )
    (net (code "348") (name "unconnected-(U$2B-P$48-PadQ$48)") (class "Default")
      (node (ref "U$2") (pin "Q$48") (pinfunction "P$48_Q$48") (pintype "bidirectional"))
    )
    (net (code "349") (name "unconnected-(U$2B-P$49-PadQ$49)") (class "Default")
      (node (ref "U$2") (pin "Q$49") (pinfunction "P$49_Q$49") (pintype "bidirectional"))
    )
    (net (code "350") (name "unconnected-(U$2B-P$50-PadQ$50)") (class "Default")
      (node (ref "U$2") (pin "Q$50") (pinfunction "P$50_Q$50") (pintype "bidirectional"))
    )
    (net (code "351") (name "unconnected-(U$2B-P$51-PadQ$51)") (class "Default")
      (node (ref "U$2") (pin "Q$51") (pinfunction "P$51_Q$51") (pintype "bidirectional"))
    )
    (net (code "352") (name "unconnected-(U$2B-P$52-PadQ$52)") (class "Default")
      (node (ref "U$2") (pin "Q$52") (pinfunction "P$52_Q$52") (pintype "bidirectional"))
    )
    (net (code "353") (name "unconnected-(U$2B-P$53-PadQ$53)") (class "Default")
      (node (ref "U$2") (pin "Q$53") (pinfunction "P$53_Q$53") (pintype "bidirectional"))
    )
    (net (code "354") (name "unconnected-(U$2B-P$54-PadQ$54)") (class "Default")
      (node (ref "U$2") (pin "Q$54") (pinfunction "P$54_Q$54") (pintype "bidirectional"))
    )
    (net (code "355") (name "unconnected-(U$2B-P$55-PadQ$55)") (class "Default")
      (node (ref "U$2") (pin "Q$55") (pinfunction "P$55_Q$55") (pintype "bidirectional"))
    )
    (net (code "356") (name "unconnected-(U$2B-P$56-PadQ$56)") (class "Default")
      (node (ref "U$2") (pin "Q$56") (pinfunction "P$56_Q$56") (pintype "bidirectional"))
    )
    (net (code "357") (name "unconnected-(U$2B-P$57-PadQ$57)") (class "Default")
      (node (ref "U$2") (pin "Q$57") (pinfunction "P$57_Q$57") (pintype "bidirectional"))
    )
    (net (code "358") (name "unconnected-(U$2B-P$58-PadQ$58)") (class "Default")
      (node (ref "U$2") (pin "Q$58") (pinfunction "P$58_Q$58") (pintype "bidirectional"))
    )
    (net (code "359") (name "unconnected-(U$2B-P$59-PadQ$59)") (class "Default")
      (node (ref "U$2") (pin "Q$59") (pinfunction "P$59_Q$59") (pintype "bidirectional"))
    )
    (net (code "360") (name "unconnected-(U$2B-P$60-PadQ$60)") (class "Default")
      (node (ref "U$2") (pin "Q$60") (pinfunction "P$60_Q$60") (pintype "bidirectional"))
    )
    (net (code "361") (name "unconnected-(U$2B-P$61-PadQ$61)") (class "Default")
      (node (ref "U$2") (pin "Q$61") (pinfunction "P$61_Q$61") (pintype "bidirectional"))
    )
    (net (code "362") (name "unconnected-(U$2B-P$62-PadQ$62)") (class "Default")
      (node (ref "U$2") (pin "Q$62") (pinfunction "P$62_Q$62") (pintype "bidirectional"))
    )
    (net (code "363") (name "unconnected-(U$2B-P$63-PadQ$63)") (class "Default")
      (node (ref "U$2") (pin "Q$63") (pinfunction "P$63_Q$63") (pintype "bidirectional"))
    )
    (net (code "364") (name "unconnected-(U$2B-P$64-PadQ$64)") (class "Default")
      (node (ref "U$2") (pin "Q$64") (pinfunction "P$64_Q$64") (pintype "bidirectional"))
    )
    (net (code "365") (name "unconnected-(U$2B-P$65-PadQ$65)") (class "Default")
      (node (ref "U$2") (pin "Q$65") (pinfunction "P$65_Q$65") (pintype "bidirectional"))
    )
    (net (code "366") (name "unconnected-(U$2B-P$66-PadQ$66)") (class "Default")
      (node (ref "U$2") (pin "Q$66") (pinfunction "P$66_Q$66") (pintype "bidirectional"))
    )
    (net (code "367") (name "unconnected-(U$2B-P$67-PadQ$67)") (class "Default")
      (node (ref "U$2") (pin "Q$67") (pinfunction "P$67_Q$67") (pintype "bidirectional"))
    )
    (net (code "368") (name "unconnected-(U$2B-P$68-PadQ$68)") (class "Default")
      (node (ref "U$2") (pin "Q$68") (pinfunction "P$68_Q$68") (pintype "bidirectional"))
    )
    (net (code "369") (name "unconnected-(U9-RIN1+-Pad32)") (class "Default")
      (node (ref "U9") (pin "32") (pinfunction "RIN1+_32") (pintype "input"))
    )
    (net (code "370") (name "unconnected-(U9-RIN1--Pad33)") (class "Default")
      (node (ref "U9") (pin "33") (pinfunction "RIN1-_33") (pintype "input"))
    )
    (net (code "371") (name "unconnected-(U9-TEST+-Pad38)") (class "Default")
      (node (ref "U9") (pin "38") (pinfunction "TEST+_38") (pintype "output"))
    )
    (net (code "372") (name "unconnected-(U9-TEST--Pad39)") (class "Default")
      (node (ref "U9") (pin "39") (pinfunction "TEST-_39") (pintype "output"))
    )
    (net (code "373") (name "unconnected-(U10-COMP1-PadE5)") (class "Default")
      (node (ref "U10") (pin "E5") (pinfunction "COMP1_E5") (pintype "bidirectional"))
    )
    (net (code "374") (name "unconnected-(U10-COMP2-PadA5)") (class "Default")
      (node (ref "U10") (pin "A5") (pinfunction "COMP2_A5") (pintype "bidirectional"))
    )
    (net (code "375") (name "unconnected-(U10-PGOOD2-PadB4)") (class "Default")
      (node (ref "U10") (pin "B4") (pinfunction "PGOOD2_B4") (pintype "open_collector"))
    )
    (net (code "376") (name "unconnected-(U17-EN1-PadP7)") (class "Default")
      (node (ref "U17") (pin "P7") (pinfunction "EN1_P7") (pintype "bidirectional"))
    )
  )
)
